# tex.net
KiCad netlist of a schematic drawn in EAGLE
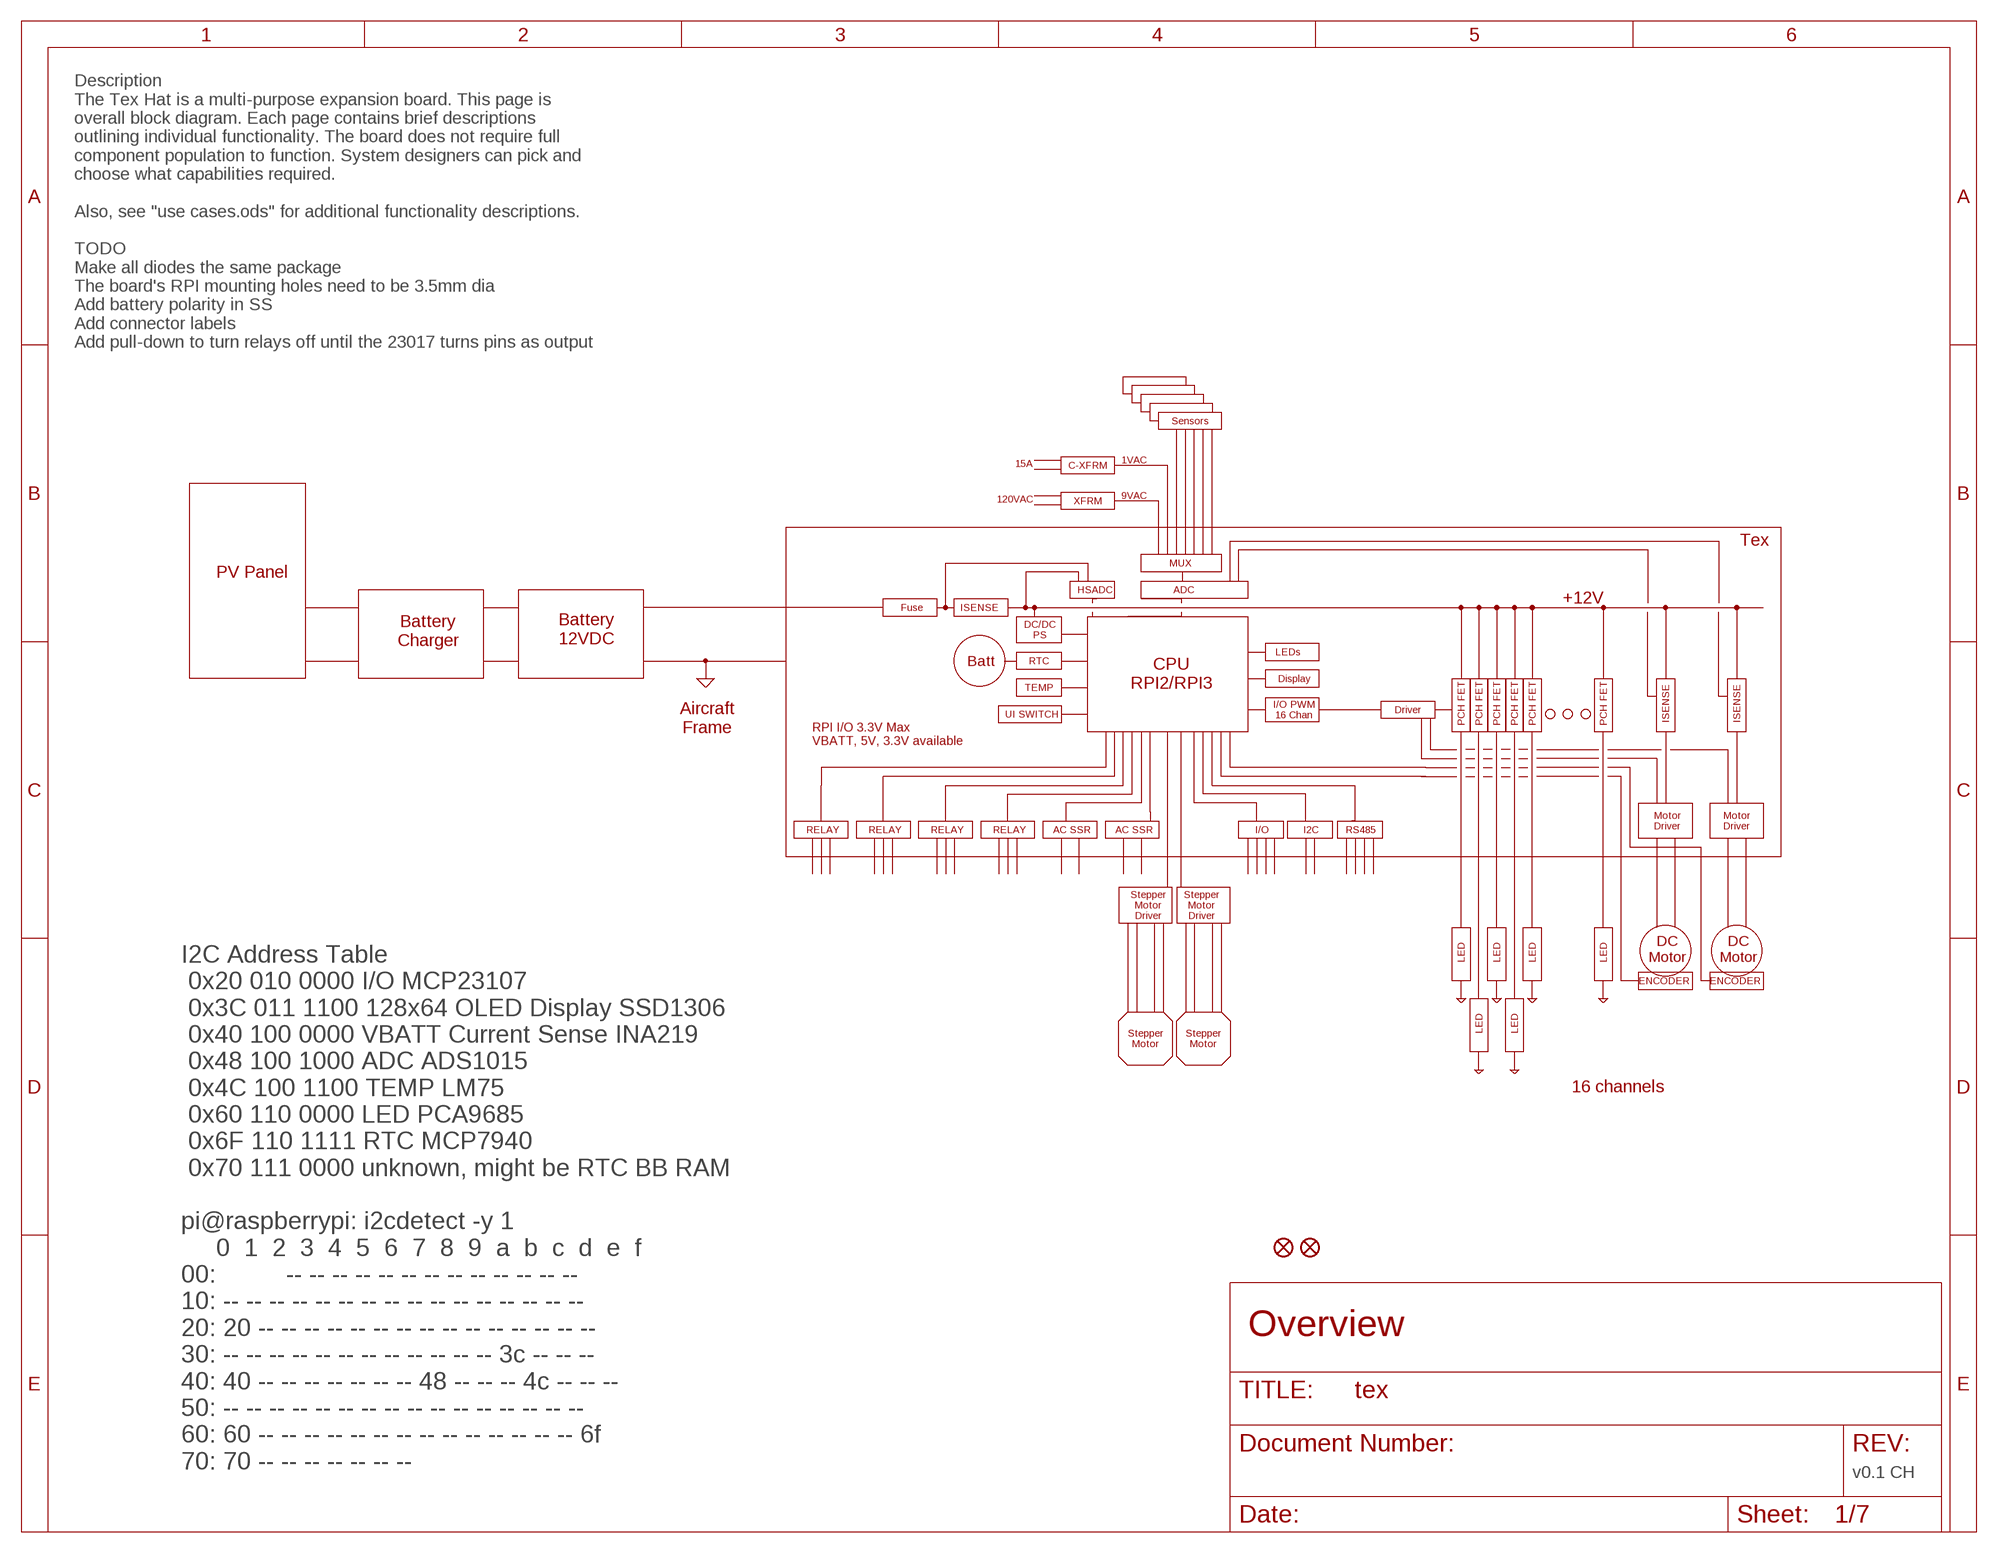
[diagram p0: schematic, sheet 1]
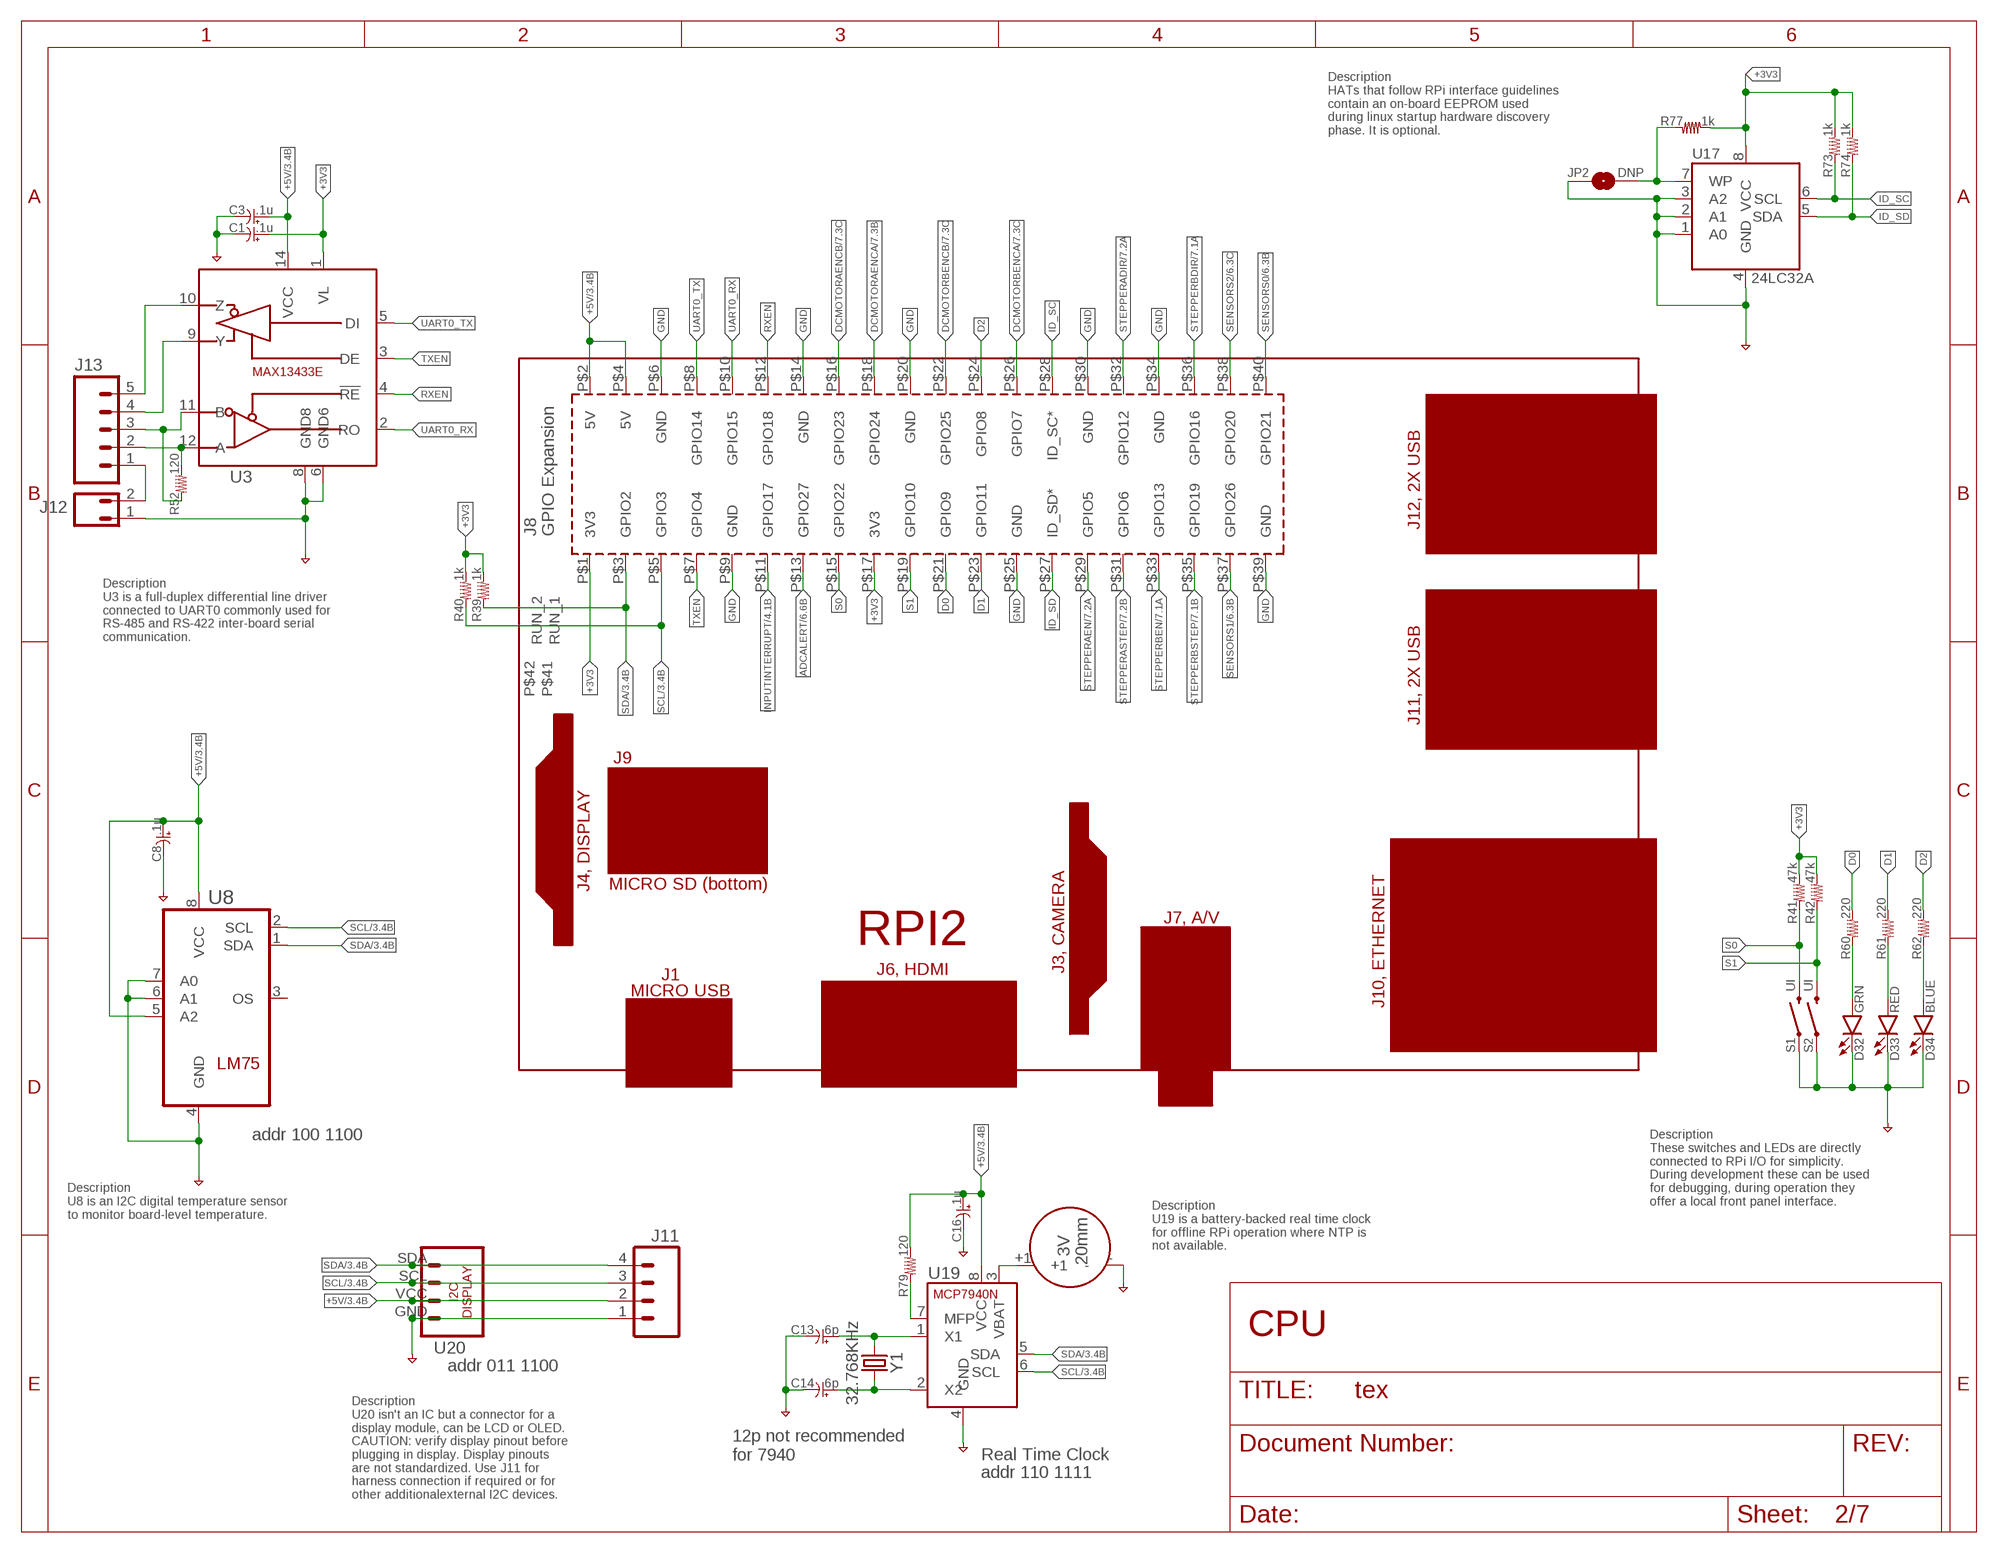
[diagram p1: schematic, sheet 2]
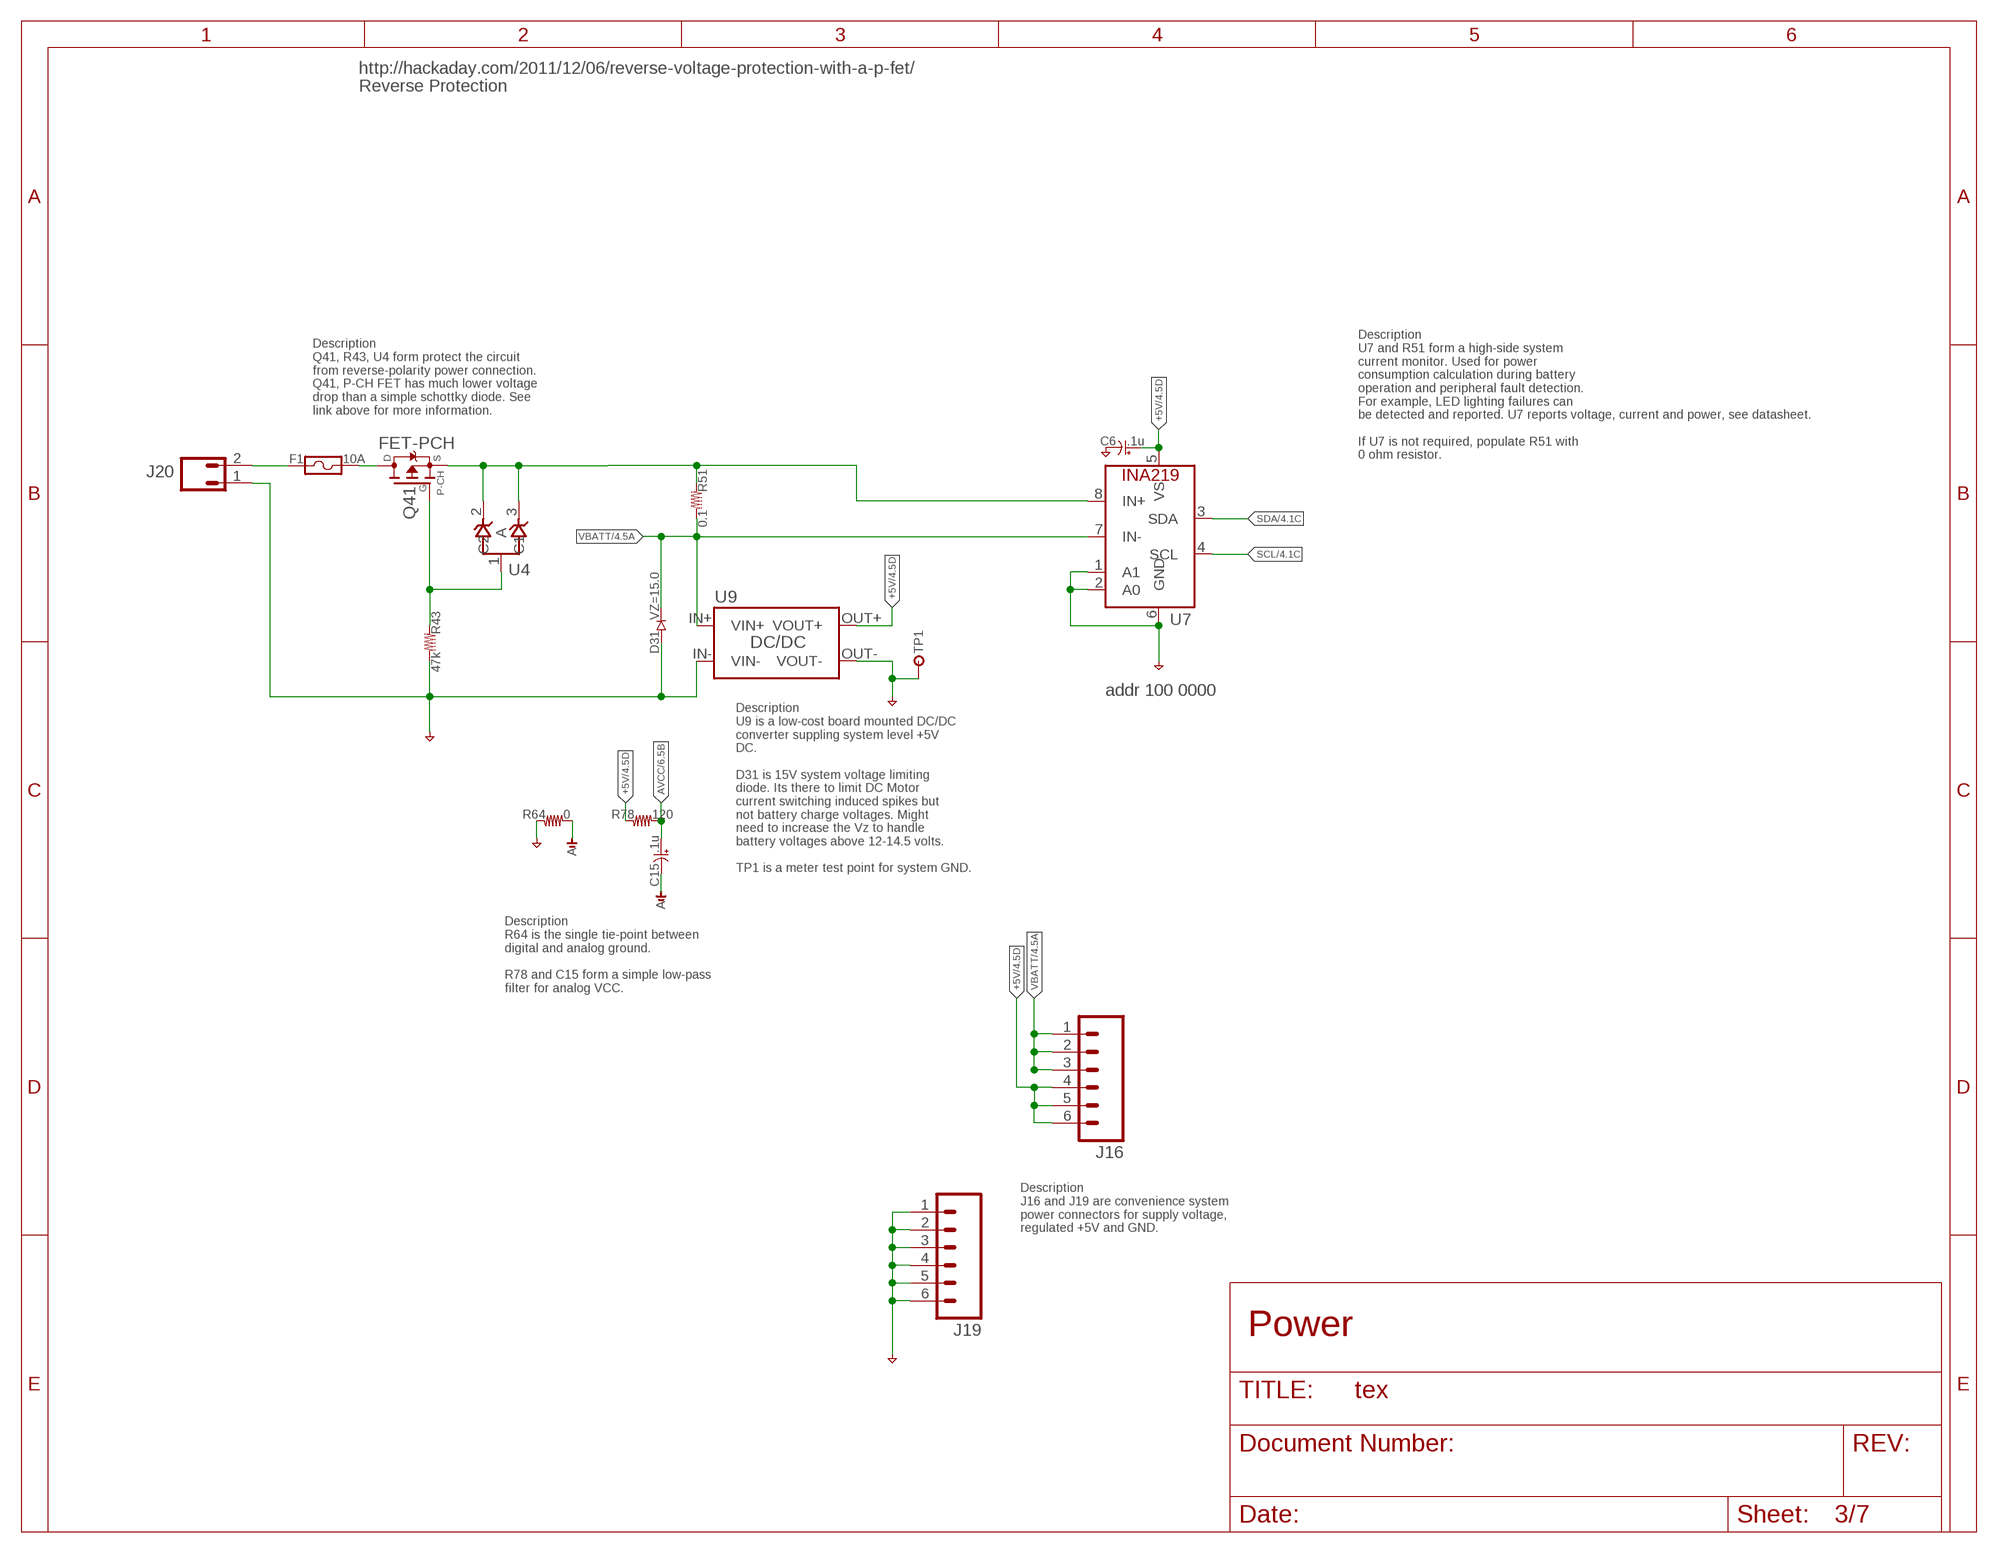
[diagram p2: schematic, sheet 3]
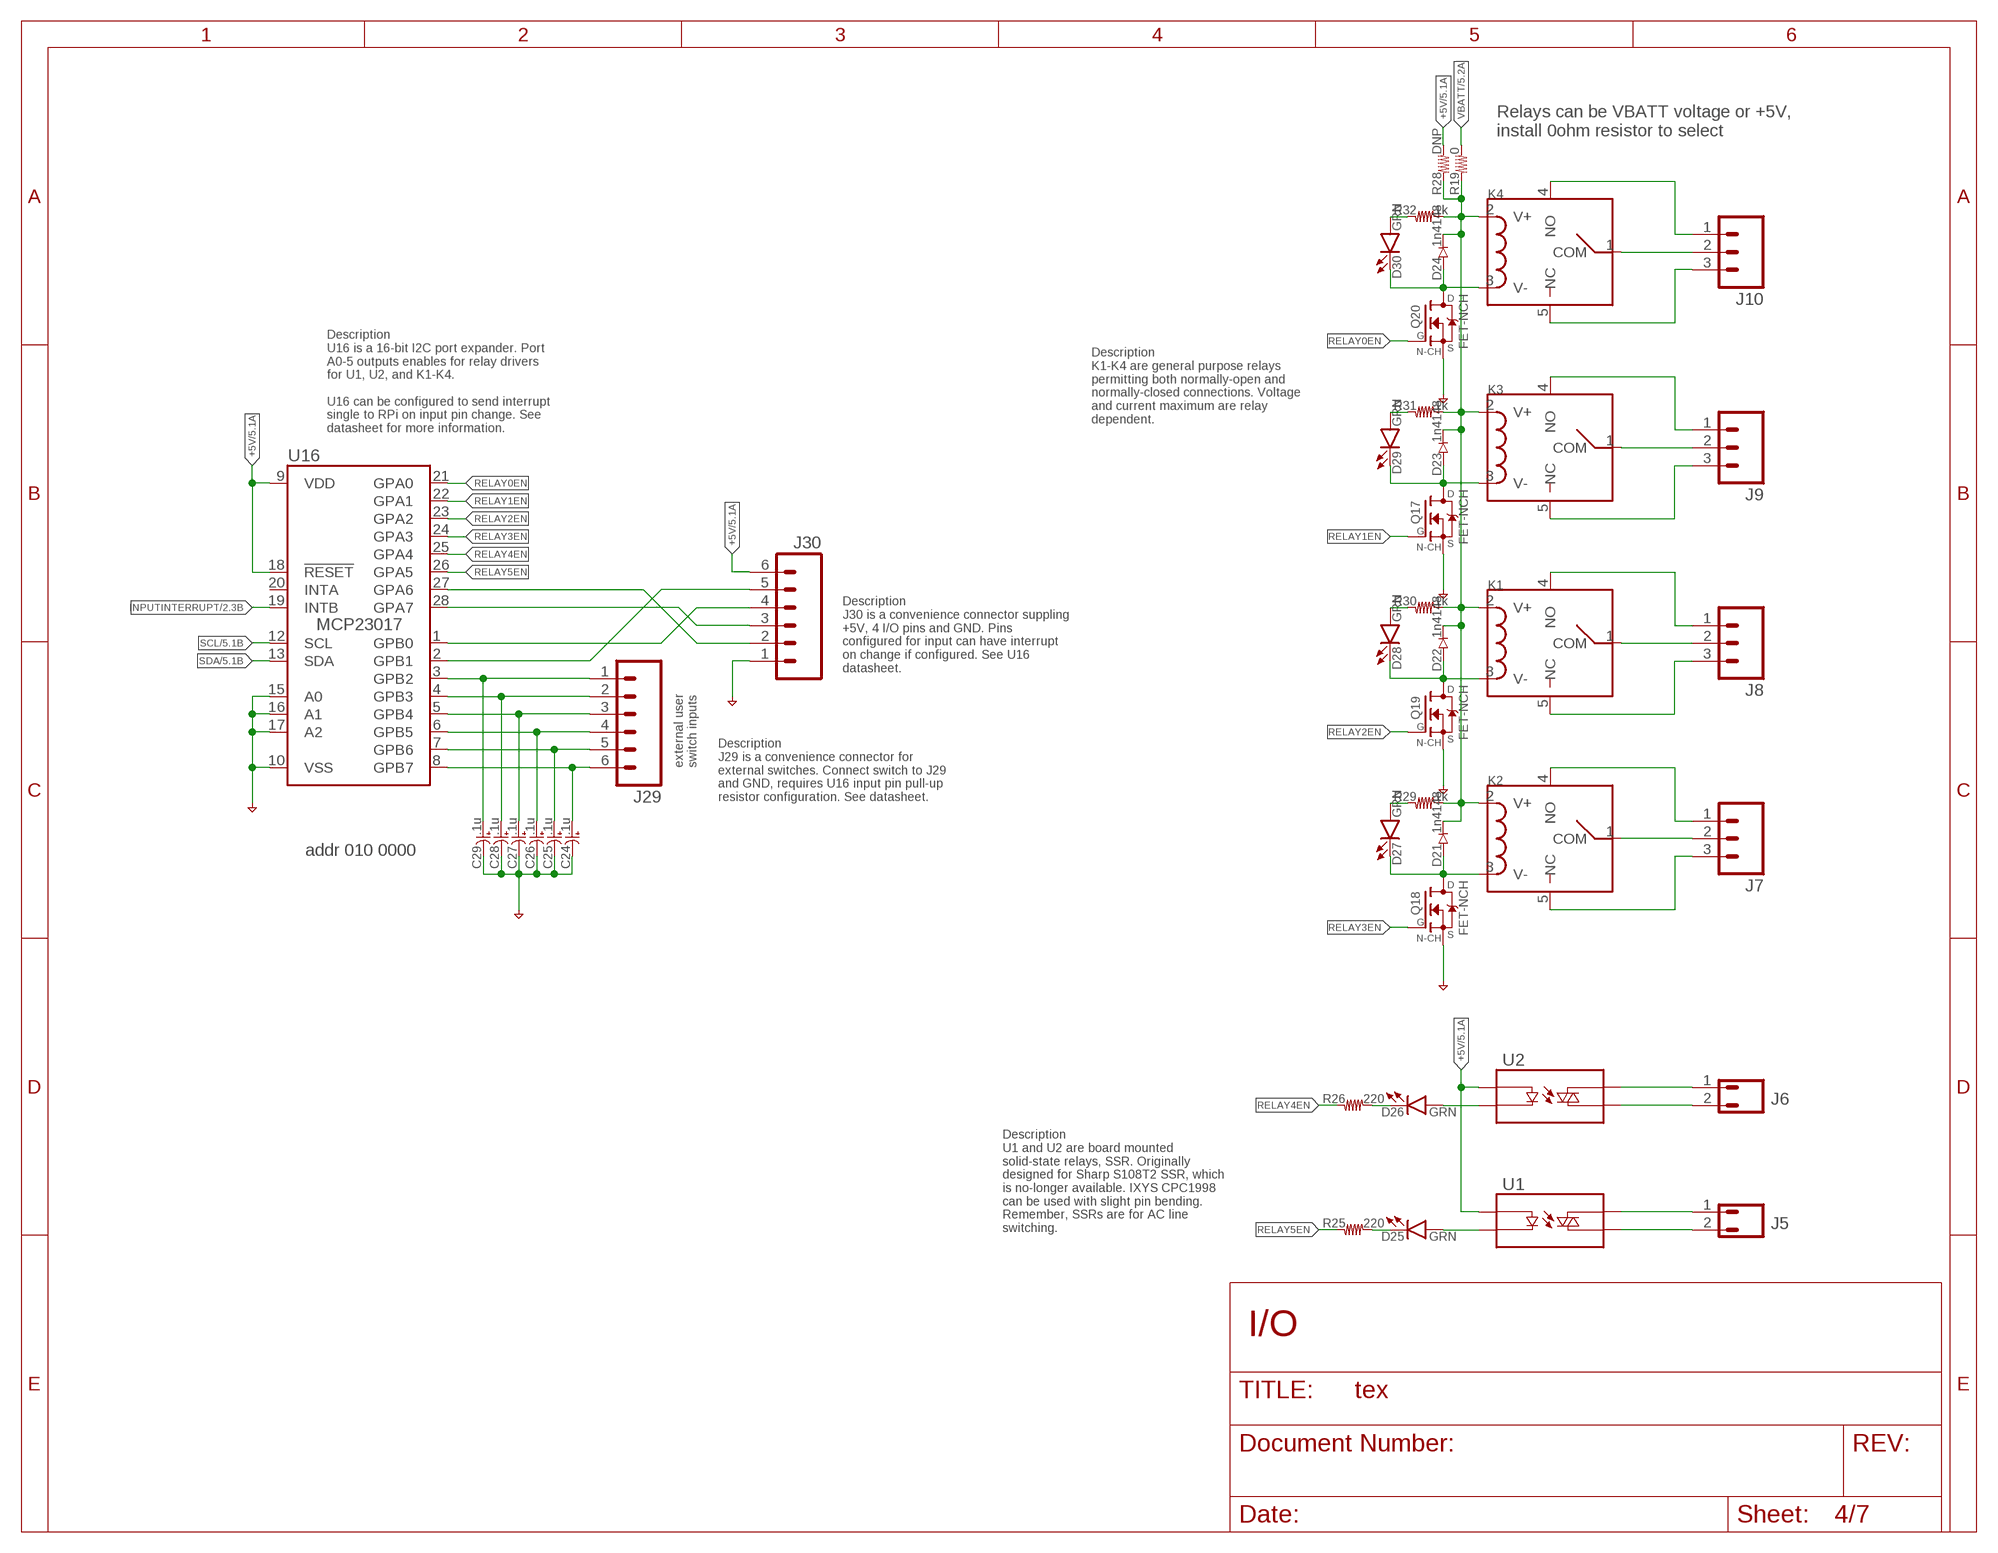
[diagram p3: schematic, sheet 4]
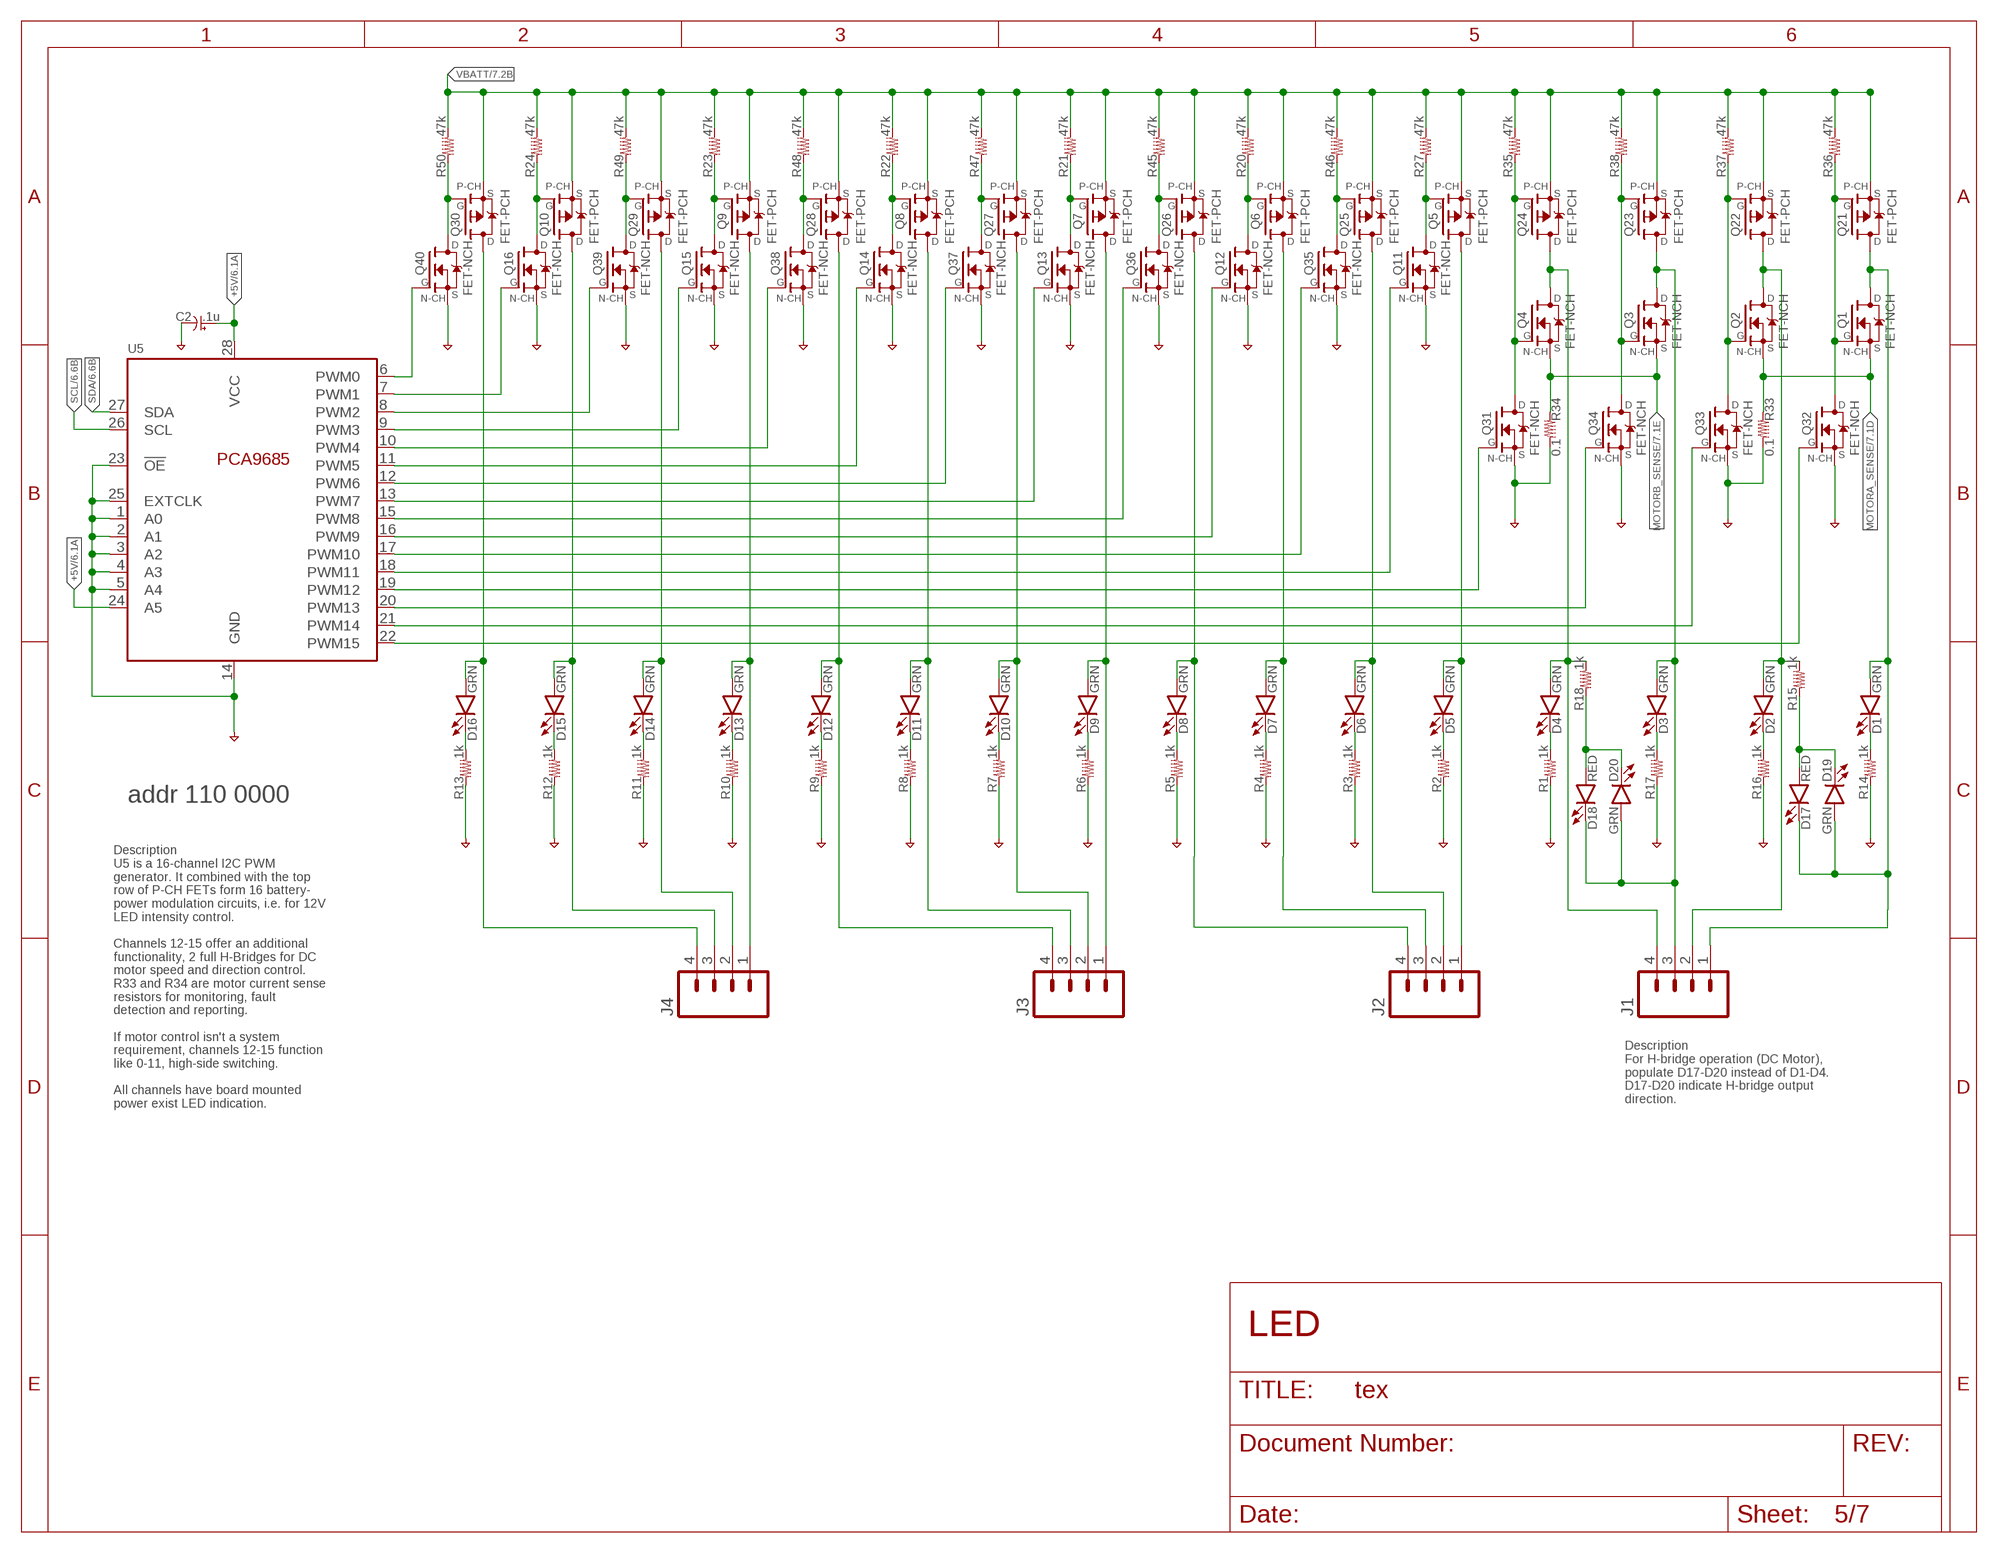
[diagram p4: schematic, sheet 5]
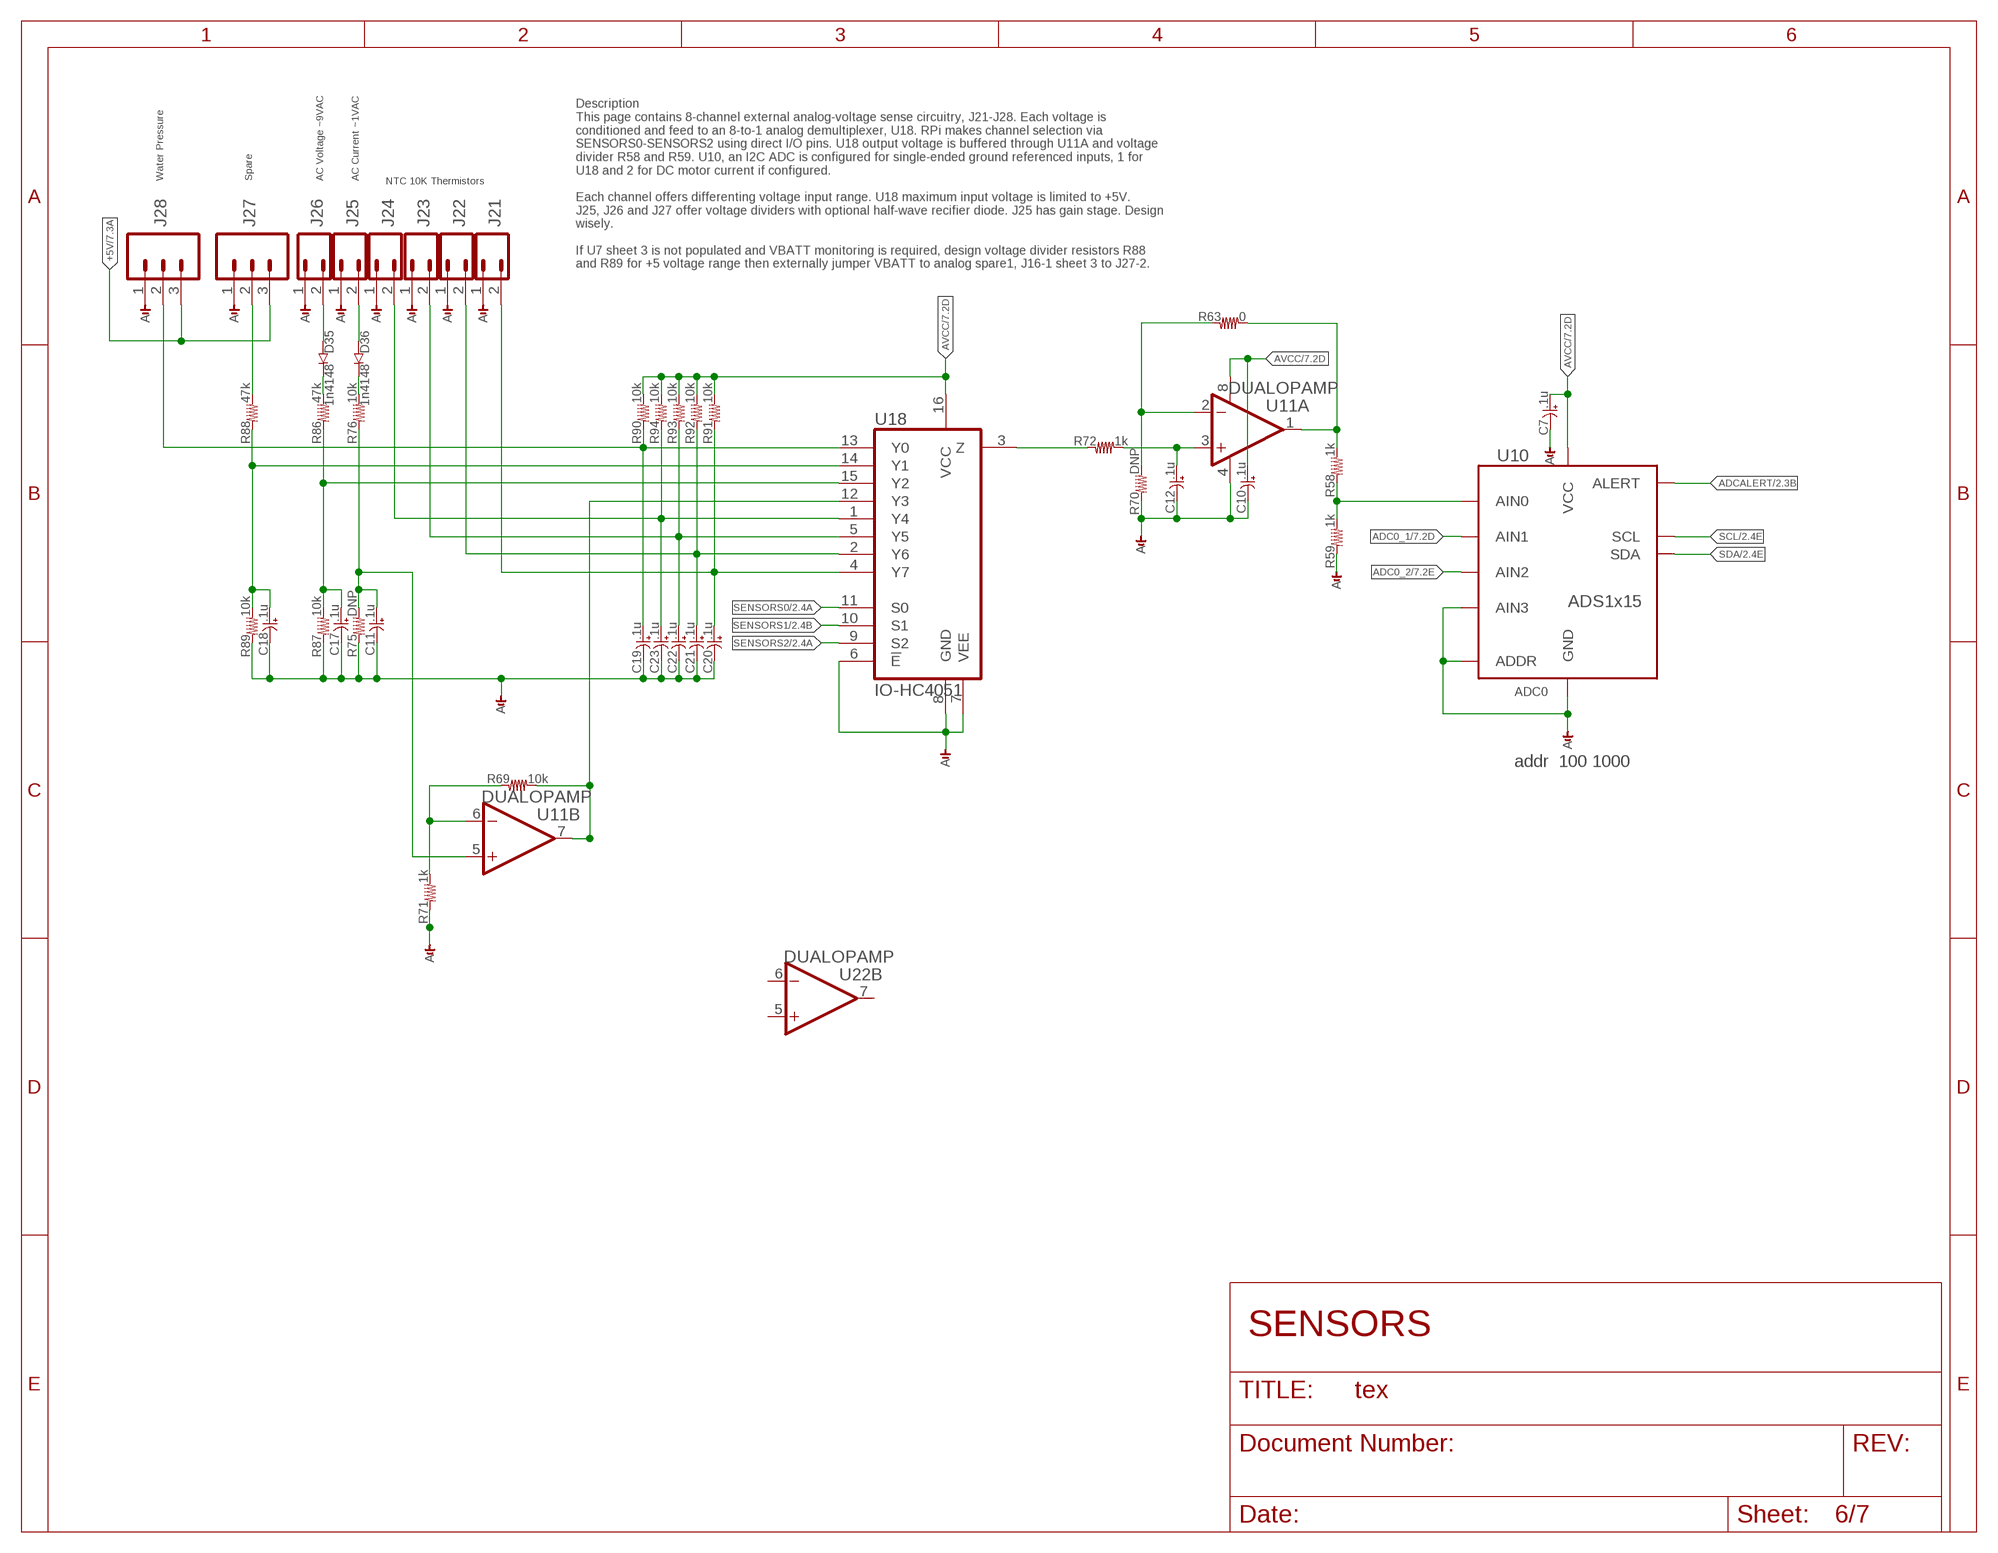
[diagram p5: schematic, sheet 6]
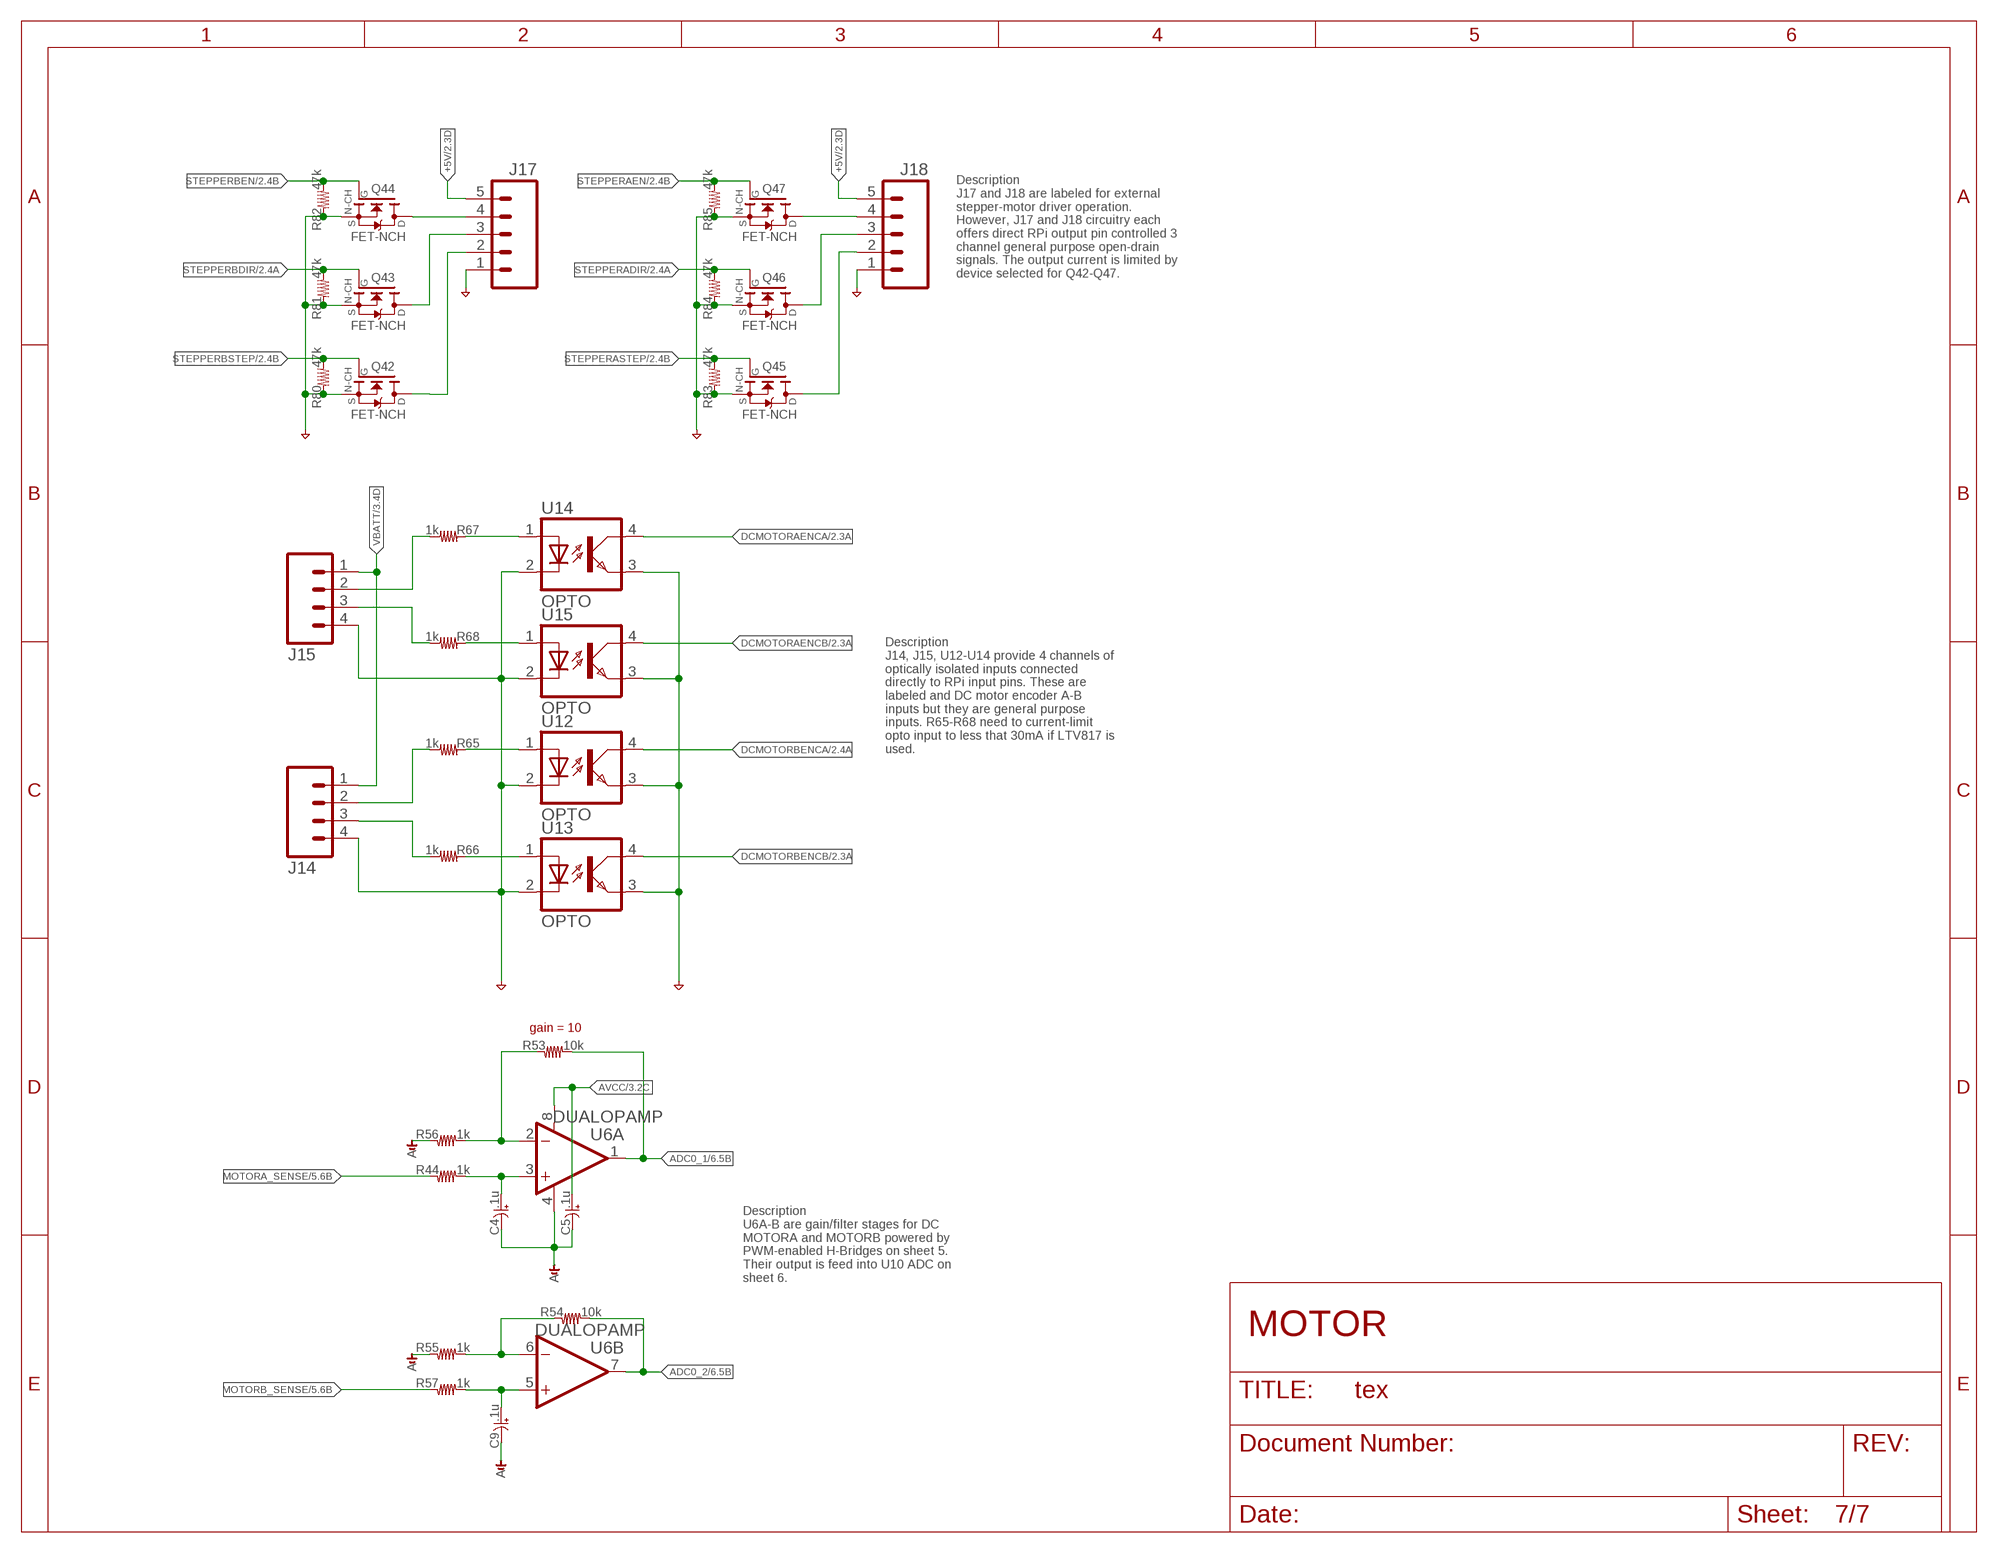
[diagram p6: schematic, sheet 7]

(export (version "E")
  (design (tool "Eeschema 10.0.6"))
  (components
    (comp (ref "C24")
      (value ".1u")
      (footprint "eagle-import:C0603")
      (libsource (lib "eagle-import") (part "C-0603"))
    )
    (comp (ref "C25")
      (value ".1u")
      (footprint "eagle-import:C0603")
      (libsource (lib "eagle-import") (part "C-0603"))
    )
    (comp (ref "C26")
      (value ".1u")
      (footprint "eagle-import:C0603")
      (libsource (lib "eagle-import") (part "C-0603"))
    )
    (comp (ref "C27")
      (value ".1u")
      (footprint "eagle-import:C0603")
      (libsource (lib "eagle-import") (part "C-0603"))
    )
    (comp (ref "C28")
      (value ".1u")
      (footprint "eagle-import:C0603")
      (libsource (lib "eagle-import") (part "C-0603"))
    )
    (comp (ref "C29")
      (value ".1u")
      (footprint "eagle-import:C0603")
      (libsource (lib "eagle-import") (part "C-0603"))
    )
    (comp (ref "D21")
      (value "1n4148")
      (footprint "eagle-import:SOD-523")
      (libsource (lib "eagle-import") (part "DIODE-0603"))
    )
    (comp (ref "D22")
      (value "1n4148")
      (footprint "eagle-import:SOD-523")
      (libsource (lib "eagle-import") (part "DIODE-0603"))
    )
    (comp (ref "D23")
      (value "1n4148")
      (footprint "eagle-import:SOD-523")
      (libsource (lib "eagle-import") (part "DIODE-0603"))
    )
    (comp (ref "D24")
      (value "1n4148")
      (footprint "eagle-import:SOD-523")
      (libsource (lib "eagle-import") (part "DIODE-0603"))
    )
    (comp (ref "D25")
      (value "GRN")
      (footprint "eagle-import:LED0603")
      (libsource (lib "eagle-import") (part "LED-0603"))
    )
    (comp (ref "D26")
      (value "GRN")
      (footprint "eagle-import:LED0603")
      (libsource (lib "eagle-import") (part "LED-0603"))
    )
    (comp (ref "D27")
      (value "GRN")
      (footprint "eagle-import:LED0603")
      (libsource (lib "eagle-import") (part "LED-0603"))
    )
    (comp (ref "D28")
      (value "GRN")
      (footprint "eagle-import:LED0603")
      (libsource (lib "eagle-import") (part "LED-0603"))
    )
    (comp (ref "D29")
      (value "GRN")
      (footprint "eagle-import:LED0603")
      (libsource (lib "eagle-import") (part "LED-0603"))
    )
    (comp (ref "D30")
      (value "GRN")
      (footprint "eagle-import:LED0603")
      (libsource (lib "eagle-import") (part "LED-0603"))
    )
    (comp (ref "J5")
      (value "CONN-02-PLUGIN-SCREW")
      (footprint "eagle-import:CONN-3.81MM-KF2EDG-2")
      (libsource (lib "eagle-import") (part "CONN-02-PLUGIN-SCREW"))
    )
    (comp (ref "J6")
      (value "CONN-02-PLUGIN-SCREW")
      (footprint "eagle-import:CONN-3.81MM-KF2EDG-2")
      (libsource (lib "eagle-import") (part "CONN-02-PLUGIN-SCREW"))
    )
    (comp (ref "J7")
      (value "CONN-03-PLUGIN-SCREW")
      (footprint "eagle-import:CONN-3.81MM-KF2EDG-3")
      (libsource (lib "eagle-import") (part "CONN-03-PLUGIN-SCREW"))
    )
    (comp (ref "J8")
      (value "CONN-03-PLUGIN-SCREW")
      (footprint "eagle-import:CONN-3.81MM-KF2EDG-3")
      (libsource (lib "eagle-import") (part "CONN-03-PLUGIN-SCREW"))
    )
    (comp (ref "J9")
      (value "CONN-03-PLUGIN-SCREW")
      (footprint "eagle-import:CONN-3.81MM-KF2EDG-3")
      (libsource (lib "eagle-import") (part "CONN-03-PLUGIN-SCREW"))
    )
    (comp (ref "J10")
      (value "CONN-03-PLUGIN-SCREW")
      (footprint "eagle-import:CONN-3.81MM-KF2EDG-3")
      (libsource (lib "eagle-import") (part "CONN-03-PLUGIN-SCREW"))
    )
    (comp (ref "J29")
      (value "CONN-06-PLUGIN-SCREW")
      (footprint "eagle-import:CONN-3.81MM-KF2EDG-6")
      (libsource (lib "eagle-import") (part "CONN-06-PLUGIN-SCREW"))
    )
    (comp (ref "J30")
      (value "CONN-06-PLUGIN-SCREW")
      (footprint "eagle-import:CONN-3.81MM-KF2EDG-6")
      (libsource (lib "eagle-import") (part "CONN-06-PLUGIN-SCREW"))
    )
    (comp (ref "K1")
      (value "RELAY-SPST-19X15X15MM")
      (footprint "eagle-import:RELAY-SPST-19.0X15.0X15.0MM")
      (libsource (lib "eagle-import") (part "RELAY-SPST-19X15X15MM"))
    )
    (comp (ref "K2")
      (value "RELAY-SPST-19X15X15MM")
      (footprint "eagle-import:RELAY-SPST-19.0X15.0X15.0MM")
      (libsource (lib "eagle-import") (part "RELAY-SPST-19X15X15MM"))
    )
    (comp (ref "K3")
      (value "RELAY-SPST-19X15X15MM")
      (footprint "eagle-import:RELAY-SPST-19.0X15.0X15.0MM")
      (libsource (lib "eagle-import") (part "RELAY-SPST-19X15X15MM"))
    )
    (comp (ref "K4")
      (value "RELAY-SPST-19X15X15MM")
      (footprint "eagle-import:RELAY-SPST-19.0X15.0X15.0MM")
      (libsource (lib "eagle-import") (part "RELAY-SPST-19X15X15MM"))
    )
    (comp (ref "Q17")
      (value "FET-NCH")
      (footprint "eagle-import:SOT23-3")
      (libsource (lib "eagle-import") (part "FET-NCHANNEL-SOT23"))
    )
    (comp (ref "Q18")
      (value "FET-NCH")
      (footprint "eagle-import:SOT23-3")
      (libsource (lib "eagle-import") (part "FET-NCHANNEL-SOT23"))
    )
    (comp (ref "Q19")
      (value "FET-NCH")
      (footprint "eagle-import:SOT23-3")
      (libsource (lib "eagle-import") (part "FET-NCHANNEL-SOT23"))
    )
    (comp (ref "Q20")
      (value "FET-NCH")
      (footprint "eagle-import:SOT23-3")
      (libsource (lib "eagle-import") (part "FET-NCHANNEL-SOT23"))
    )
    (comp (ref "R19")
      (value "0")
      (footprint "eagle-import:R0603")
      (libsource (lib "eagle-import") (part "R-0603"))
    )
    (comp (ref "R25")
      (value "220")
      (footprint "eagle-import:R0603")
      (libsource (lib "eagle-import") (part "R-0603"))
    )
    (comp (ref "R26")
      (value "220")
      (footprint "eagle-import:R0603")
      (libsource (lib "eagle-import") (part "R-0603"))
    )
    (comp (ref "R28")
      (value "DNP")
      (footprint "eagle-import:R0603")
      (libsource (lib "eagle-import") (part "R-0603"))
    )
    (comp (ref "R29")
      (value "1k")
      (footprint "eagle-import:R0603")
      (libsource (lib "eagle-import") (part "R-0603"))
    )
    (comp (ref "R30")
      (value "1k")
      (footprint "eagle-import:R0603")
      (libsource (lib "eagle-import") (part "R-0603"))
    )
    (comp (ref "R31")
      (value "1k")
      (footprint "eagle-import:R0603")
      (libsource (lib "eagle-import") (part "R-0603"))
    )
    (comp (ref "R32")
      (value "1k")
      (footprint "eagle-import:R0603")
      (libsource (lib "eagle-import") (part "R-0603"))
    )
    (comp (ref "U1")
      (value "RELAY-S108T02PTH")
      (footprint "eagle-import:RELAY-S108T02")
      (libsource (lib "eagle-import") (part "RELAY-S108T02PTH"))
    )
    (comp (ref "U2")
      (value "RELAY-S108T02PTH")
      (footprint "eagle-import:RELAY-S108T02")
      (libsource (lib "eagle-import") (part "RELAY-S108T02PTH"))
    )
    (comp (ref "U16")
      (value "MCP23017")
      (footprint "eagle-import:SO28W")
      (fields (field (name "MF") "MICROCHIP") (field (name "MPN") "MCP23017-E/SO"))
      (libsource (lib "eagle-import") (part "IO-MCP23017SO"))
    )
    (comp (ref "C6")
      (value ".1u")
      (footprint "eagle-import:C0603")
      (libsource (lib "eagle-import") (part "C-0603"))
    )
    (comp (ref "C15")
      (value ".1u")
      (footprint "eagle-import:C0603")
      (libsource (lib "eagle-import") (part "C-0603"))
    )
    (comp (ref "D31")
      (value "VZ=15.0")
      (footprint "eagle-import:DO-214AC(SMA)")
      (libsource (lib "eagle-import") (part "DIODE-SMA"))
    )
    (comp (ref "F1")
      (value "10A")
      (footprint "eagle-import:3557-2")
      (libsource (lib "eagle-import") (part "FUSE-HOLDER-3557-2"))
    )
    (comp (ref "J16")
      (value "CONN-06-PLUGIN-SCREW")
      (footprint "eagle-import:CONN-3.81MM-KF2EDG-6")
      (libsource (lib "eagle-import") (part "CONN-06-PLUGIN-SCREW"))
    )
    (comp (ref "J19")
      (value "CONN-06-PLUGIN-SCREW")
      (footprint "eagle-import:CONN-3.81MM-KF2EDG-6")
      (libsource (lib "eagle-import") (part "CONN-06-PLUGIN-SCREW"))
    )
    (comp (ref "J20")
      (value "CONN-02-6.35MM")
      (footprint "eagle-import:CONN-OSTT702")
      (libsource (lib "eagle-import") (part "CONN-02-6.35MM"))
    )
    (comp (ref "Q41")
      (value "FET-PCH")
      (footprint "eagle-import:TO252")
      (libsource (lib "eagle-import") (part "FET-PCHTO252"))
    )
    (comp (ref "R43")
      (value "47k")
      (footprint "eagle-import:R0603")
      (libsource (lib "eagle-import") (part "R-0603"))
    )
    (comp (ref "R51")
      (value "0.1")
      (footprint "eagle-import:R1210")
      (libsource (lib "eagle-import") (part "R-1210"))
    )
    (comp (ref "R64")
      (value "0")
      (footprint "eagle-import:R0603")
      (libsource (lib "eagle-import") (part "R-0603"))
    )
    (comp (ref "R78")
      (value "120")
      (footprint "eagle-import:R0603")
      (libsource (lib "eagle-import") (part "R-0603"))
    )
    (comp (ref "TP1")
      (value "TESTPOINTTHRU")
      (footprint "eagle-import:TPTHRU")
      (libsource (lib "eagle-import") (part "TESTPOINTTHRU"))
    )
    (comp (ref "U4")
      (value "AZ23C5V1")
      (footprint "eagle-import:SOT-23")
      (libsource (lib "eagle-import") (part "AZ23CXXX"))
    )
    (comp (ref "U7")
      (value "INA219")
      (footprint "eagle-import:SOIC8")
      (libsource (lib "eagle-import") (part "ADC-INA219-SOIC8"))
    )
    (comp (ref "U9")
      (value "DCDC-CONVERTER-LM2577-BOARD")
      (footprint "eagle-import:DCDC-LM2577-BOARD")
      (libsource (lib "eagle-import") (part "DCDC-CONVERTER-LM2577-BOARD"))
    )
    (comp (ref "C4")
      (value ".1u")
      (footprint "eagle-import:C0603")
      (libsource (lib "eagle-import") (part "C-0603"))
    )
    (comp (ref "C5")
      (value ".1u")
      (footprint "eagle-import:C0603")
      (libsource (lib "eagle-import") (part "C-0603"))
    )
    (comp (ref "C9")
      (value ".1u")
      (footprint "eagle-import:C0603")
      (libsource (lib "eagle-import") (part "C-0603"))
    )
    (comp (ref "J14")
      (value "CONN-04-PLUGIN-SCREW")
      (footprint "eagle-import:CONN-3.81MM-KF2EDG-4")
      (libsource (lib "eagle-import") (part "CONN-04-PLUGIN-SCREW"))
    )
    (comp (ref "J15")
      (value "CONN-04-PLUGIN-SCREW")
      (footprint "eagle-import:CONN-3.81MM-KF2EDG-4")
      (libsource (lib "eagle-import") (part "CONN-04-PLUGIN-SCREW"))
    )
    (comp (ref "J17")
      (value "CONN-05-PLUGIN-SCREW")
      (footprint "eagle-import:CONN-3.81MM-KF2EDG-5")
      (libsource (lib "eagle-import") (part "CONN-05-PLUGIN-SCREW"))
    )
    (comp (ref "J18")
      (value "CONN-05-PLUGIN-SCREW")
      (footprint "eagle-import:CONN-3.81MM-KF2EDG-5")
      (libsource (lib "eagle-import") (part "CONN-05-PLUGIN-SCREW"))
    )
    (comp (ref "Q42")
      (value "FET-NCH")
      (footprint "eagle-import:SOT23-3")
      (libsource (lib "eagle-import") (part "FET-NCHANNEL-SOT23"))
    )
    (comp (ref "Q43")
      (value "FET-NCH")
      (footprint "eagle-import:SOT23-3")
      (libsource (lib "eagle-import") (part "FET-NCHANNEL-SOT23"))
    )
    (comp (ref "Q44")
      (value "FET-NCH")
      (footprint "eagle-import:SOT23-3")
      (libsource (lib "eagle-import") (part "FET-NCHANNEL-SOT23"))
    )
    (comp (ref "Q45")
      (value "FET-NCH")
      (footprint "eagle-import:SOT23-3")
      (libsource (lib "eagle-import") (part "FET-NCHANNEL-SOT23"))
    )
    (comp (ref "Q46")
      (value "FET-NCH")
      (footprint "eagle-import:SOT23-3")
      (libsource (lib "eagle-import") (part "FET-NCHANNEL-SOT23"))
    )
    (comp (ref "Q47")
      (value "FET-NCH")
      (footprint "eagle-import:SOT23-3")
      (libsource (lib "eagle-import") (part "FET-NCHANNEL-SOT23"))
    )
    (comp (ref "R44")
      (value "1k")
      (footprint "eagle-import:R0603")
      (libsource (lib "eagle-import") (part "R-0603"))
    )
    (comp (ref "R53")
      (value "10k")
      (footprint "eagle-import:R0603")
      (libsource (lib "eagle-import") (part "R-0603"))
    )
    (comp (ref "R54")
      (value "10k")
      (footprint "eagle-import:R0603")
      (libsource (lib "eagle-import") (part "R-0603"))
    )
    (comp (ref "R55")
      (value "1k")
      (footprint "eagle-import:R0603")
      (libsource (lib "eagle-import") (part "R-0603"))
    )
    (comp (ref "R56")
      (value "1k")
      (footprint "eagle-import:R0603")
      (libsource (lib "eagle-import") (part "R-0603"))
    )
    (comp (ref "R57")
      (value "1k")
      (footprint "eagle-import:R0603")
      (libsource (lib "eagle-import") (part "R-0603"))
    )
    (comp (ref "R65")
      (value "1k")
      (footprint "eagle-import:R0603")
      (libsource (lib "eagle-import") (part "R-0603"))
    )
    (comp (ref "R66")
      (value "1k")
      (footprint "eagle-import:R0603")
      (libsource (lib "eagle-import") (part "R-0603"))
    )
    (comp (ref "R67")
      (value "1k")
      (footprint "eagle-import:R0603")
      (libsource (lib "eagle-import") (part "R-0603"))
    )
    (comp (ref "R68")
      (value "1k")
      (footprint "eagle-import:R0603")
      (libsource (lib "eagle-import") (part "R-0603"))
    )
    (comp (ref "R80")
      (value "47k")
      (footprint "eagle-import:R0603")
      (libsource (lib "eagle-import") (part "R-0603"))
    )
    (comp (ref "R81")
      (value "47k")
      (footprint "eagle-import:R0603")
      (libsource (lib "eagle-import") (part "R-0603"))
    )
    (comp (ref "R82")
      (value "47k")
      (footprint "eagle-import:R0603")
      (libsource (lib "eagle-import") (part "R-0603"))
    )
    (comp (ref "R83")
      (value "47k")
      (footprint "eagle-import:R0603")
      (libsource (lib "eagle-import") (part "R-0603"))
    )
    (comp (ref "R84")
      (value "47k")
      (footprint "eagle-import:R0603")
      (libsource (lib "eagle-import") (part "R-0603"))
    )
    (comp (ref "R85")
      (value "47k")
      (footprint "eagle-import:R0603")
      (libsource (lib "eagle-import") (part "R-0603"))
    )
    (comp (ref "U6")
      (value "DUALOPAMP")
      (footprint "eagle-import:SO08")
      (libsource (lib "eagle-import") (part "AMP-OPAMP-DUAL-SO08"))
    )
    (comp (ref "U12")
      (value "OPTO")
      (footprint "eagle-import:LTV817")
      (libsource (lib "eagle-import") (part "OPTO-LTV817"))
    )
    (comp (ref "U13")
      (value "OPTO")
      (footprint "eagle-import:LTV817")
      (libsource (lib "eagle-import") (part "OPTO-LTV817"))
    )
    (comp (ref "U14")
      (value "OPTO")
      (footprint "eagle-import:LTV817")
      (libsource (lib "eagle-import") (part "OPTO-LTV817"))
    )
    (comp (ref "U15")
      (value "OPTO")
      (footprint "eagle-import:LTV817")
      (libsource (lib "eagle-import") (part "OPTO-LTV817"))
    )
    (comp (ref "B1")
      (value "CR2032")
      (footprint "eagle-import:BAT-HLD-001")
      (libsource (lib "eagle-import") (part "CONN-COINBATTERYHOLDER-20MM"))
    )
    (comp (ref "C1")
      (value ".1u")
      (footprint "eagle-import:C0603")
      (libsource (lib "eagle-import") (part "C-0603"))
    )
    (comp (ref "C3")
      (value ".1u")
      (footprint "eagle-import:C0603")
      (libsource (lib "eagle-import") (part "C-0603"))
    )
    (comp (ref "C8")
      (value ".1u")
      (footprint "eagle-import:C0603")
      (libsource (lib "eagle-import") (part "C-0603"))
    )
    (comp (ref "C13")
      (value "6p")
      (footprint "eagle-import:C0603")
      (libsource (lib "eagle-import") (part "C-0603"))
    )
    (comp (ref "C14")
      (value "6p")
      (footprint "eagle-import:C0603")
      (libsource (lib "eagle-import") (part "C-0603"))
    )
    (comp (ref "C16")
      (value ".1u")
      (footprint "eagle-import:C0603")
      (libsource (lib "eagle-import") (part "C-0603"))
    )
    (comp (ref "D32")
      (value "GRN")
      (footprint "eagle-import:LED0603")
      (libsource (lib "eagle-import") (part "LED-0603"))
    )
    (comp (ref "D33")
      (value "RED")
      (footprint "eagle-import:LED0603")
      (libsource (lib "eagle-import") (part "LED-0603"))
    )
    (comp (ref "D34")
      (value "BLUE")
      (footprint "eagle-import:LED0603")
      (libsource (lib "eagle-import") (part "LED-0603"))
    )
    (comp (ref "J11")
      (value "CONN-04-0.1")
      (footprint "eagle-import:1X04")
      (libsource (lib "eagle-import") (part "CONN-04-0.1"))
    )
    (comp (ref "J12")
      (value "CONN-02-0.1")
      (footprint "eagle-import:1X02")
      (libsource (lib "eagle-import") (part "CONN-02-0.1"))
    )
    (comp (ref "J13")
      (value "CONN-05-PLUGIN-SCREW")
      (footprint "eagle-import:CONN-3.81MM-KF2EDG-5")
      (libsource (lib "eagle-import") (part "CONN-05-PLUGIN-SCREW"))
    )
    (comp (ref "JP2")
      (value "DNP")
      (footprint "eagle-import:PAD-JUMPER-2-NO_NO_SILK")
      (libsource (lib "eagle-import") (part "JUMPER-PAD-2-NO"))
    )
    (comp (ref "PCB1")
      (value "BOARD-RPI2")
      (footprint "eagle-import:BOARD-RPI2")
      (libsource (lib "eagle-import") (part "BOARD-RPI2"))
    )
    (comp (ref "R39")
      (value "1k")
      (footprint "eagle-import:R0603")
      (libsource (lib "eagle-import") (part "R-0603"))
    )
    (comp (ref "R40")
      (value "1k")
      (footprint "eagle-import:R0603")
      (libsource (lib "eagle-import") (part "R-0603"))
    )
    (comp (ref "R41")
      (value "47k")
      (footprint "eagle-import:R0603")
      (libsource (lib "eagle-import") (part "R-0603"))
    )
    (comp (ref "R42")
      (value "47k")
      (footprint "eagle-import:R0603")
      (libsource (lib "eagle-import") (part "R-0603"))
    )
    (comp (ref "R52")
      (value "120")
      (footprint "eagle-import:R0603")
      (libsource (lib "eagle-import") (part "R-0603"))
    )
    (comp (ref "R60")
      (value "220")
      (footprint "eagle-import:R0603")
      (libsource (lib "eagle-import") (part "R-0603"))
    )
    (comp (ref "R61")
      (value "220")
      (footprint "eagle-import:R0603")
      (libsource (lib "eagle-import") (part "R-0603"))
    )
    (comp (ref "R62")
      (value "220")
      (footprint "eagle-import:R0603")
      (libsource (lib "eagle-import") (part "R-0603"))
    )
    (comp (ref "R73")
      (value "1k")
      (footprint "eagle-import:R0603")
      (libsource (lib "eagle-import") (part "R-0603"))
    )
    (comp (ref "R74")
      (value "1k")
      (footprint "eagle-import:R0603")
      (libsource (lib "eagle-import") (part "R-0603"))
    )
    (comp (ref "R77")
      (value "1k")
      (footprint "eagle-import:R0603")
      (libsource (lib "eagle-import") (part "R-0603"))
    )
    (comp (ref "R79")
      (value "120")
      (footprint "eagle-import:R0603")
      (libsource (lib "eagle-import") (part "R-0603"))
    )
    (comp (ref "S1")
      (value "UI")
      (footprint "eagle-import:TACTILE-SWITCH-6MMX3.5MM")
      (libsource (lib "eagle-import") (part "SWITCH-PUSHBUTTON-6MMX3.5MM"))
    )
    (comp (ref "S2")
      (value "UI")
      (footprint "eagle-import:TACTILE-SWITCH-6MMX3.5MM")
      (libsource (lib "eagle-import") (part "SWITCH-PUSHBUTTON-6MMX3.5MM"))
    )
    (comp (ref "U3")
      (value "MAX13433E")
      (footprint "eagle-import:SO14")
      (libsource (lib "eagle-import") (part "COMM-MAX13433E"))
    )
    (comp (ref "U8")
      (value "LM75")
      (footprint "eagle-import:SO08")
      (libsource (lib "eagle-import") (part "SENSOR-TEMP-LM75-SO08"))
    )
    (comp (ref "U17")
      (value "24LC32A")
      (footprint "eagle-import:SO08")
      (libsource (lib "eagle-import") (part "MEMORY-EEPROM-SO08"))
    )
    (comp (ref "U19")
      (value "MCP7940N")
      (footprint "eagle-import:SO08")
      (libsource (lib "eagle-import") (part "RTC-MCP7940N"))
    )
    (comp (ref "U20")
      (value "DISP-I2C-4PIN")
      (footprint "eagle-import:DISP-I2C-4PIN-0.96")
      (libsource (lib "eagle-import") (part "DISP-I2C-4PIN"))
    )
    (comp (ref "Y1")
      (value "32.768KHz")
      (footprint "eagle-import:ABS25")
      (libsource (lib "eagle-import") (part "CRYSTAL32-SMDABS25"))
    )
    (comp (ref "C7")
      (value ".1u")
      (footprint "eagle-import:C0603")
      (libsource (lib "eagle-import") (part "C-0603"))
    )
    (comp (ref "C10")
      (value ".1u")
      (footprint "eagle-import:C0603")
      (libsource (lib "eagle-import") (part "C-0603"))
    )
    (comp (ref "C11")
      (value ".1u")
      (footprint "eagle-import:C0603")
      (libsource (lib "eagle-import") (part "C-0603"))
    )
    (comp (ref "C12")
      (value ".1u")
      (footprint "eagle-import:C0603")
      (libsource (lib "eagle-import") (part "C-0603"))
    )
    (comp (ref "C17")
      (value ".1u")
      (footprint "eagle-import:C0603")
      (libsource (lib "eagle-import") (part "C-0603"))
    )
    (comp (ref "C18")
      (value ".1u")
      (footprint "eagle-import:C0603")
      (libsource (lib "eagle-import") (part "C-0603"))
    )
    (comp (ref "C19")
      (value ".1u")
      (footprint "eagle-import:C0603")
      (libsource (lib "eagle-import") (part "C-0603"))
    )
    (comp (ref "C20")
      (value ".1u")
      (footprint "eagle-import:C0603")
      (libsource (lib "eagle-import") (part "C-0603"))
    )
    (comp (ref "C21")
      (value ".1u")
      (footprint "eagle-import:C0603")
      (libsource (lib "eagle-import") (part "C-0603"))
    )
    (comp (ref "C22")
      (value ".1u")
      (footprint "eagle-import:C0603")
      (libsource (lib "eagle-import") (part "C-0603"))
    )
    (comp (ref "C23")
      (value ".1u")
      (footprint "eagle-import:C0603")
      (libsource (lib "eagle-import") (part "C-0603"))
    )
    (comp (ref "D35")
      (value "1n4148")
      (footprint "eagle-import:SOD-523")
      (libsource (lib "eagle-import") (part "DIODE-0603"))
    )
    (comp (ref "D36")
      (value "1n4148")
      (footprint "eagle-import:SOD-523")
      (libsource (lib "eagle-import") (part "DIODE-0603"))
    )
    (comp (ref "J21")
      (value "CONN-02-PLUGIN-SCREW")
      (footprint "eagle-import:CONN-3.81MM-KF2EDG-2")
      (libsource (lib "eagle-import") (part "CONN-02-PLUGIN-SCREW"))
    )
    (comp (ref "J22")
      (value "CONN-02-PLUGIN-SCREW")
      (footprint "eagle-import:CONN-3.81MM-KF2EDG-2")
      (libsource (lib "eagle-import") (part "CONN-02-PLUGIN-SCREW"))
    )
    (comp (ref "J23")
      (value "CONN-02-PLUGIN-SCREW")
      (footprint "eagle-import:CONN-3.81MM-KF2EDG-2")
      (libsource (lib "eagle-import") (part "CONN-02-PLUGIN-SCREW"))
    )
    (comp (ref "J24")
      (value "CONN-02-PLUGIN-SCREW")
      (footprint "eagle-import:CONN-3.81MM-KF2EDG-2")
      (libsource (lib "eagle-import") (part "CONN-02-PLUGIN-SCREW"))
    )
    (comp (ref "J25")
      (value "CONN-02-PLUGIN-SCREW")
      (footprint "eagle-import:CONN-3.81MM-KF2EDG-2")
      (libsource (lib "eagle-import") (part "CONN-02-PLUGIN-SCREW"))
    )
    (comp (ref "J26")
      (value "CONN-02-PLUGIN-SCREW")
      (footprint "eagle-import:CONN-3.81MM-KF2EDG-2")
      (libsource (lib "eagle-import") (part "CONN-02-PLUGIN-SCREW"))
    )
    (comp (ref "J27")
      (value "CONN-03-PLUGIN-SCREW")
      (footprint "eagle-import:CONN-3.81MM-KF2EDG-3")
      (libsource (lib "eagle-import") (part "CONN-03-PLUGIN-SCREW"))
    )
    (comp (ref "J28")
      (value "CONN-03-PLUGIN-SCREW")
      (footprint "eagle-import:CONN-3.81MM-KF2EDG-3")
      (libsource (lib "eagle-import") (part "CONN-03-PLUGIN-SCREW"))
    )
    (comp (ref "R58")
      (value "1k")
      (footprint "eagle-import:R0603")
      (libsource (lib "eagle-import") (part "R-0603"))
    )
    (comp (ref "R59")
      (value "1k")
      (footprint "eagle-import:R0603")
      (libsource (lib "eagle-import") (part "R-0603"))
    )
    (comp (ref "R63")
      (value "0")
      (footprint "eagle-import:R0603")
      (libsource (lib "eagle-import") (part "R-0603"))
    )
    (comp (ref "R69")
      (value "10k")
      (footprint "eagle-import:R0603")
      (libsource (lib "eagle-import") (part "R-0603"))
    )
    (comp (ref "R70")
      (value "DNP")
      (footprint "eagle-import:R0603")
      (libsource (lib "eagle-import") (part "R-0603"))
    )
    (comp (ref "R71")
      (value "1k")
      (footprint "eagle-import:R0603")
      (libsource (lib "eagle-import") (part "R-0603"))
    )
    (comp (ref "R72")
      (value "1k")
      (footprint "eagle-import:R0603")
      (libsource (lib "eagle-import") (part "R-0603"))
    )
    (comp (ref "R75")
      (value "DNP")
      (footprint "eagle-import:R0603")
      (libsource (lib "eagle-import") (part "R-0603"))
    )
    (comp (ref "R76")
      (value "10k")
      (footprint "eagle-import:R0603")
      (libsource (lib "eagle-import") (part "R-0603"))
    )
    (comp (ref "R86")
      (value "47k")
      (footprint "eagle-import:R0603")
      (libsource (lib "eagle-import") (part "R-0603"))
    )
    (comp (ref "R87")
      (value "10k")
      (footprint "eagle-import:R0603")
      (libsource (lib "eagle-import") (part "R-0603"))
    )
    (comp (ref "R88")
      (value "47k")
      (footprint "eagle-import:R0603")
      (libsource (lib "eagle-import") (part "R-0603"))
    )
    (comp (ref "R89")
      (value "10k")
      (footprint "eagle-import:R0603")
      (libsource (lib "eagle-import") (part "R-0603"))
    )
    (comp (ref "R90")
      (value "10k")
      (footprint "eagle-import:R0603")
      (libsource (lib "eagle-import") (part "R-0603"))
    )
    (comp (ref "R91")
      (value "10k")
      (footprint "eagle-import:R0603")
      (libsource (lib "eagle-import") (part "R-0603"))
    )
    (comp (ref "R92")
      (value "10k")
      (footprint "eagle-import:R0603")
      (libsource (lib "eagle-import") (part "R-0603"))
    )
    (comp (ref "R93")
      (value "10k")
      (footprint "eagle-import:R0603")
      (libsource (lib "eagle-import") (part "R-0603"))
    )
    (comp (ref "R94")
      (value "10k")
      (footprint "eagle-import:R0603")
      (libsource (lib "eagle-import") (part "R-0603"))
    )
    (comp (ref "U10")
      (value "ADS1x15")
      (footprint "eagle-import:MSOP10_0.5")
      (libsource (lib "eagle-import") (part "ADC-ADS1015-MSOP10"))
    )
    (comp (ref "U11")
      (value "DUALOPAMP")
      (footprint "eagle-import:SO08")
      (libsource (lib "eagle-import") (part "AMP-OPAMP-DUAL-SO08"))
    )
    (comp (ref "U18")
      (value "IO-HC4051")
      (footprint "eagle-import:SO16")
      (libsource (lib "eagle-import") (part "IO-HC4051"))
    )
    (comp (ref "U22")
      (value "DUALOPAMP")
      (footprint "eagle-import:SO08")
      (libsource (lib "eagle-import") (part "AMP-OPAMP-DUAL-SO08"))
    )
    (comp (ref "JP1")
      (value "FIDUCIALUFIDUCIAL")
      (footprint "eagle-import:MICRO-FIDUCIAL")
      (libsource (lib "eagle-import") (part "FIDUCIALUFIDUCIAL"))
    )
    (comp (ref "JP3")
      (value "FIDUCIALUFIDUCIAL")
      (footprint "eagle-import:MICRO-FIDUCIAL")
      (libsource (lib "eagle-import") (part "FIDUCIALUFIDUCIAL"))
    )
    (comp (ref "C2")
      (value ".1u")
      (footprint "eagle-import:C0603")
      (libsource (lib "eagle-import") (part "C-0603"))
    )
    (comp (ref "D1")
      (value "GRN")
      (footprint "eagle-import:LED0603")
      (libsource (lib "eagle-import") (part "LED-0603"))
    )
    (comp (ref "D2")
      (value "GRN")
      (footprint "eagle-import:LED0603")
      (libsource (lib "eagle-import") (part "LED-0603"))
    )
    (comp (ref "D3")
      (value "GRN")
      (footprint "eagle-import:LED0603")
      (libsource (lib "eagle-import") (part "LED-0603"))
    )
    (comp (ref "D4")
      (value "GRN")
      (footprint "eagle-import:LED0603")
      (libsource (lib "eagle-import") (part "LED-0603"))
    )
    (comp (ref "D5")
      (value "GRN")
      (footprint "eagle-import:LED0603")
      (libsource (lib "eagle-import") (part "LED-0603"))
    )
    (comp (ref "D6")
      (value "GRN")
      (footprint "eagle-import:LED0603")
      (libsource (lib "eagle-import") (part "LED-0603"))
    )
    (comp (ref "D7")
      (value "GRN")
      (footprint "eagle-import:LED0603")
      (libsource (lib "eagle-import") (part "LED-0603"))
    )
    (comp (ref "D8")
      (value "GRN")
      (footprint "eagle-import:LED0603")
      (libsource (lib "eagle-import") (part "LED-0603"))
    )
    (comp (ref "D9")
      (value "GRN")
      (footprint "eagle-import:LED0603")
      (libsource (lib "eagle-import") (part "LED-0603"))
    )
    (comp (ref "D10")
      (value "GRN")
      (footprint "eagle-import:LED0603")
      (libsource (lib "eagle-import") (part "LED-0603"))
    )
    (comp (ref "D11")
      (value "GRN")
      (footprint "eagle-import:LED0603")
      (libsource (lib "eagle-import") (part "LED-0603"))
    )
    (comp (ref "D12")
      (value "GRN")
      (footprint "eagle-import:LED0603")
      (libsource (lib "eagle-import") (part "LED-0603"))
    )
    (comp (ref "D13")
      (value "GRN")
      (footprint "eagle-import:LED0603")
      (libsource (lib "eagle-import") (part "LED-0603"))
    )
    (comp (ref "D14")
      (value "GRN")
      (footprint "eagle-import:LED0603")
      (libsource (lib "eagle-import") (part "LED-0603"))
    )
    (comp (ref "D15")
      (value "GRN")
      (footprint "eagle-import:LED0603")
      (libsource (lib "eagle-import") (part "LED-0603"))
    )
    (comp (ref "D16")
      (value "GRN")
      (footprint "eagle-import:LED0603")
      (libsource (lib "eagle-import") (part "LED-0603"))
    )
    (comp (ref "D17")
      (value "RED")
      (footprint "eagle-import:LED0603")
      (libsource (lib "eagle-import") (part "LED-0603"))
    )
    (comp (ref "D18")
      (value "RED")
      (footprint "eagle-import:LED0603")
      (libsource (lib "eagle-import") (part "LED-0603"))
    )
    (comp (ref "D19")
      (value "GRN")
      (footprint "eagle-import:LED0603")
      (libsource (lib "eagle-import") (part "LED-0603"))
    )
    (comp (ref "D20")
      (value "GRN")
      (footprint "eagle-import:LED0603")
      (libsource (lib "eagle-import") (part "LED-0603"))
    )
    (comp (ref "J1")
      (value "CONN-04-PLUGIN-SCREW")
      (footprint "eagle-import:CONN-3.81MM-KF2EDG-4")
      (libsource (lib "eagle-import") (part "CONN-04-PLUGIN-SCREW"))
    )
    (comp (ref "J2")
      (value "CONN-04-PLUGIN-SCREW")
      (footprint "eagle-import:CONN-3.81MM-KF2EDG-4")
      (libsource (lib "eagle-import") (part "CONN-04-PLUGIN-SCREW"))
    )
    (comp (ref "J3")
      (value "CONN-04-PLUGIN-SCREW")
      (footprint "eagle-import:CONN-3.81MM-KF2EDG-4")
      (libsource (lib "eagle-import") (part "CONN-04-PLUGIN-SCREW"))
    )
    (comp (ref "J4")
      (value "CONN-04-PLUGIN-SCREW")
      (footprint "eagle-import:CONN-3.81MM-KF2EDG-4")
      (libsource (lib "eagle-import") (part "CONN-04-PLUGIN-SCREW"))
    )
    (comp (ref "Q1")
      (value "FET-NCH")
      (footprint "eagle-import:TO252")
      (libsource (lib "eagle-import") (part "FET-NCHANNEL-TO252"))
    )
    (comp (ref "Q2")
      (value "FET-NCH")
      (footprint "eagle-import:TO252")
      (libsource (lib "eagle-import") (part "FET-NCHANNEL-TO252"))
    )
    (comp (ref "Q3")
      (value "FET-NCH")
      (footprint "eagle-import:TO252")
      (libsource (lib "eagle-import") (part "FET-NCHANNEL-TO252"))
    )
    (comp (ref "Q4")
      (value "FET-NCH")
      (footprint "eagle-import:TO252")
      (libsource (lib "eagle-import") (part "FET-NCHANNEL-TO252"))
    )
    (comp (ref "Q5")
      (value "FET-PCH")
      (footprint "eagle-import:TO252")
      (libsource (lib "eagle-import") (part "FET-PCHANNEL-TO252"))
    )
    (comp (ref "Q6")
      (value "FET-PCH")
      (footprint "eagle-import:TO252")
      (libsource (lib "eagle-import") (part "FET-PCHANNEL-TO252"))
    )
    (comp (ref "Q7")
      (value "FET-PCH")
      (footprint "eagle-import:TO252")
      (libsource (lib "eagle-import") (part "FET-PCHANNEL-TO252"))
    )
    (comp (ref "Q8")
      (value "FET-PCH")
      (footprint "eagle-import:TO252")
      (libsource (lib "eagle-import") (part "FET-PCHANNEL-TO252"))
    )
    (comp (ref "Q9")
      (value "FET-PCH")
      (footprint "eagle-import:TO252")
      (libsource (lib "eagle-import") (part "FET-PCHANNEL-TO252"))
    )
    (comp (ref "Q10")
      (value "FET-PCH")
      (footprint "eagle-import:TO252")
      (libsource (lib "eagle-import") (part "FET-PCHANNEL-TO252"))
    )
    (comp (ref "Q11")
      (value "FET-NCH")
      (footprint "eagle-import:SOT23-3")
      (libsource (lib "eagle-import") (part "FET-NCHANNEL-SOT23"))
    )
    (comp (ref "Q12")
      (value "FET-NCH")
      (footprint "eagle-import:SOT23-3")
      (libsource (lib "eagle-import") (part "FET-NCHANNEL-SOT23"))
    )
    (comp (ref "Q13")
      (value "FET-NCH")
      (footprint "eagle-import:SOT23-3")
      (libsource (lib "eagle-import") (part "FET-NCHANNEL-SOT23"))
    )
    (comp (ref "Q14")
      (value "FET-NCH")
      (footprint "eagle-import:SOT23-3")
      (libsource (lib "eagle-import") (part "FET-NCHANNEL-SOT23"))
    )
    (comp (ref "Q15")
      (value "FET-NCH")
      (footprint "eagle-import:SOT23-3")
      (libsource (lib "eagle-import") (part "FET-NCHANNEL-SOT23"))
    )
    (comp (ref "Q16")
      (value "FET-NCH")
      (footprint "eagle-import:SOT23-3")
      (libsource (lib "eagle-import") (part "FET-NCHANNEL-SOT23"))
    )
    (comp (ref "Q21")
      (value "FET-PCH")
      (footprint "eagle-import:TO252")
      (libsource (lib "eagle-import") (part "FET-PCHANNEL-TO252"))
    )
    (comp (ref "Q22")
      (value "FET-PCH")
      (footprint "eagle-import:TO252")
      (libsource (lib "eagle-import") (part "FET-PCHANNEL-TO252"))
    )
    (comp (ref "Q23")
      (value "FET-PCH")
      (footprint "eagle-import:TO252")
      (libsource (lib "eagle-import") (part "FET-PCHANNEL-TO252"))
    )
    (comp (ref "Q24")
      (value "FET-PCH")
      (footprint "eagle-import:TO252")
      (libsource (lib "eagle-import") (part "FET-PCHANNEL-TO252"))
    )
    (comp (ref "Q25")
      (value "FET-PCH")
      (footprint "eagle-import:TO252")
      (libsource (lib "eagle-import") (part "FET-PCHANNEL-TO252"))
    )
    (comp (ref "Q26")
      (value "FET-PCH")
      (footprint "eagle-import:TO252")
      (libsource (lib "eagle-import") (part "FET-PCHANNEL-TO252"))
    )
    (comp (ref "Q27")
      (value "FET-PCH")
      (footprint "eagle-import:TO252")
      (libsource (lib "eagle-import") (part "FET-PCHANNEL-TO252"))
    )
    (comp (ref "Q28")
      (value "FET-PCH")
      (footprint "eagle-import:TO252")
      (libsource (lib "eagle-import") (part "FET-PCHANNEL-TO252"))
    )
    (comp (ref "Q29")
      (value "FET-PCH")
      (footprint "eagle-import:TO252")
      (libsource (lib "eagle-import") (part "FET-PCHANNEL-TO252"))
    )
    (comp (ref "Q30")
      (value "FET-PCH")
      (footprint "eagle-import:TO252")
      (libsource (lib "eagle-import") (part "FET-PCHANNEL-TO252"))
    )
    (comp (ref "Q31")
      (value "FET-NCH")
      (footprint "eagle-import:SOT23-3")
      (libsource (lib "eagle-import") (part "FET-NCHANNEL-SOT23"))
    )
    (comp (ref "Q32")
      (value "FET-NCH")
      (footprint "eagle-import:SOT23-3")
      (libsource (lib "eagle-import") (part "FET-NCHANNEL-SOT23"))
    )
    (comp (ref "Q33")
      (value "FET-NCH")
      (footprint "eagle-import:SOT23-3")
      (libsource (lib "eagle-import") (part "FET-NCHANNEL-SOT23"))
    )
    (comp (ref "Q34")
      (value "FET-NCH")
      (footprint "eagle-import:SOT23-3")
      (libsource (lib "eagle-import") (part "FET-NCHANNEL-SOT23"))
    )
    (comp (ref "Q35")
      (value "FET-NCH")
      (footprint "eagle-import:SOT23-3")
      (libsource (lib "eagle-import") (part "FET-NCHANNEL-SOT23"))
    )
    (comp (ref "Q36")
      (value "FET-NCH")
      (footprint "eagle-import:SOT23-3")
      (libsource (lib "eagle-import") (part "FET-NCHANNEL-SOT23"))
    )
    (comp (ref "Q37")
      (value "FET-NCH")
      (footprint "eagle-import:SOT23-3")
      (libsource (lib "eagle-import") (part "FET-NCHANNEL-SOT23"))
    )
    (comp (ref "Q38")
      (value "FET-NCH")
      (footprint "eagle-import:SOT23-3")
      (libsource (lib "eagle-import") (part "FET-NCHANNEL-SOT23"))
    )
    (comp (ref "Q39")
      (value "FET-NCH")
      (footprint "eagle-import:SOT23-3")
      (libsource (lib "eagle-import") (part "FET-NCHANNEL-SOT23"))
    )
    (comp (ref "Q40")
      (value "FET-NCH")
      (footprint "eagle-import:SOT23-3")
      (libsource (lib "eagle-import") (part "FET-NCHANNEL-SOT23"))
    )
    (comp (ref "R1")
      (value "1k")
      (footprint "eagle-import:R0603")
      (libsource (lib "eagle-import") (part "R-0603"))
    )
    (comp (ref "R2")
      (value "1k")
      (footprint "eagle-import:R0603")
      (libsource (lib "eagle-import") (part "R-0603"))
    )
    (comp (ref "R3")
      (value "1k")
      (footprint "eagle-import:R0603")
      (libsource (lib "eagle-import") (part "R-0603"))
    )
    (comp (ref "R4")
      (value "1k")
      (footprint "eagle-import:R0603")
      (libsource (lib "eagle-import") (part "R-0603"))
    )
    (comp (ref "R5")
      (value "1k")
      (footprint "eagle-import:R0603")
      (libsource (lib "eagle-import") (part "R-0603"))
    )
    (comp (ref "R6")
      (value "1k")
      (footprint "eagle-import:R0603")
      (libsource (lib "eagle-import") (part "R-0603"))
    )
    (comp (ref "R7")
      (value "1k")
      (footprint "eagle-import:R0603")
      (libsource (lib "eagle-import") (part "R-0603"))
    )
    (comp (ref "R8")
      (value "1k")
      (footprint "eagle-import:R0603")
      (libsource (lib "eagle-import") (part "R-0603"))
    )
    (comp (ref "R9")
      (value "1k")
      (footprint "eagle-import:R0603")
      (libsource (lib "eagle-import") (part "R-0603"))
    )
    (comp (ref "R10")
      (value "1k")
      (footprint "eagle-import:R0603")
      (libsource (lib "eagle-import") (part "R-0603"))
    )
    (comp (ref "R11")
      (value "1k")
      (footprint "eagle-import:R0603")
      (libsource (lib "eagle-import") (part "R-0603"))
    )
    (comp (ref "R12")
      (value "1k")
      (footprint "eagle-import:R0603")
      (libsource (lib "eagle-import") (part "R-0603"))
    )
    (comp (ref "R13")
      (value "1k")
      (footprint "eagle-import:R0603")
      (libsource (lib "eagle-import") (part "R-0603"))
    )
    (comp (ref "R14")
      (value "1k")
      (footprint "eagle-import:R0603")
      (libsource (lib "eagle-import") (part "R-0603"))
    )
    (comp (ref "R15")
      (value "1k")
      (footprint "eagle-import:R0603")
      (libsource (lib "eagle-import") (part "R-0603"))
    )
    (comp (ref "R16")
      (value "1k")
      (footprint "eagle-import:R0603")
      (libsource (lib "eagle-import") (part "R-0603"))
    )
    (comp (ref "R17")
      (value "1k")
      (footprint "eagle-import:R0603")
      (libsource (lib "eagle-import") (part "R-0603"))
    )
    (comp (ref "R18")
      (value "1k")
      (footprint "eagle-import:R0603")
      (libsource (lib "eagle-import") (part "R-0603"))
    )
    (comp (ref "R20")
      (value "47k")
      (footprint "eagle-import:R0603")
      (libsource (lib "eagle-import") (part "R-0603"))
    )
    (comp (ref "R21")
      (value "47k")
      (footprint "eagle-import:R0603")
      (libsource (lib "eagle-import") (part "R-0603"))
    )
    (comp (ref "R22")
      (value "47k")
      (footprint "eagle-import:R0603")
      (libsource (lib "eagle-import") (part "R-0603"))
    )
    (comp (ref "R23")
      (value "47k")
      (footprint "eagle-import:R0603")
      (libsource (lib "eagle-import") (part "R-0603"))
    )
    (comp (ref "R24")
      (value "47k")
      (footprint "eagle-import:R0603")
      (libsource (lib "eagle-import") (part "R-0603"))
    )
    (comp (ref "R27")
      (value "47k")
      (footprint "eagle-import:R0603")
      (libsource (lib "eagle-import") (part "R-0603"))
    )
    (comp (ref "R33")
      (value "0.1")
      (footprint "eagle-import:R1210")
      (libsource (lib "eagle-import") (part "R-1210"))
    )
    (comp (ref "R34")
      (value "0.1")
      (footprint "eagle-import:R1210")
      (libsource (lib "eagle-import") (part "R-1210"))
    )
    (comp (ref "R35")
      (value "47k")
      (footprint "eagle-import:R0603")
      (libsource (lib "eagle-import") (part "R-0603"))
    )
    (comp (ref "R36")
      (value "47k")
      (footprint "eagle-import:R0603")
      (libsource (lib "eagle-import") (part "R-0603"))
    )
    (comp (ref "R37")
      (value "47k")
      (footprint "eagle-import:R0603")
      (libsource (lib "eagle-import") (part "R-0603"))
    )
    (comp (ref "R38")
      (value "47k")
      (footprint "eagle-import:R0603")
      (libsource (lib "eagle-import") (part "R-0603"))
    )
    (comp (ref "R45")
      (value "47k")
      (footprint "eagle-import:R0603")
      (libsource (lib "eagle-import") (part "R-0603"))
    )
    (comp (ref "R46")
      (value "47k")
      (footprint "eagle-import:R0603")
      (libsource (lib "eagle-import") (part "R-0603"))
    )
    (comp (ref "R47")
      (value "47k")
      (footprint "eagle-import:R0603")
      (libsource (lib "eagle-import") (part "R-0603"))
    )
    (comp (ref "R48")
      (value "47k")
      (footprint "eagle-import:R0603")
      (libsource (lib "eagle-import") (part "R-0603"))
    )
    (comp (ref "R49")
      (value "47k")
      (footprint "eagle-import:R0603")
      (libsource (lib "eagle-import") (part "R-0603"))
    )
    (comp (ref "R50")
      (value "47k")
      (footprint "eagle-import:R0603")
      (libsource (lib "eagle-import") (part "R-0603"))
    )
    (comp (ref "U5")
      (value "PCA9685")
      (footprint "eagle-import:TSSOP28")
      (libsource (lib "eagle-import") (part "IO-PCA9685-TSSOP28"))
    )
  )
  (nets
    (net (code "1") (name "+3V3") (class "Default")
      (node (ref "C1") (pin "1") (pinfunction "1_1") (pintype "passive"))
      (node (ref "PCB1") (pin "P$1") (pinfunction "3V3_P$1") (pintype "bidirectional"))
      (node (ref "PCB1") (pin "P$17") (pinfunction "3V3_P$17") (pintype "bidirectional"))
      (node (ref "R39") (pin "2") (pinfunction "2_2") (pintype "passive"))
      (node (ref "R40") (pin "2") (pinfunction "2_2") (pintype "passive"))
      (node (ref "R41") (pin "2") (pinfunction "2_2") (pintype "passive"))
      (node (ref "R42") (pin "2") (pinfunction "2_2") (pintype "passive"))
      (node (ref "R73") (pin "2") (pinfunction "2_2") (pintype "passive"))
      (node (ref "R74") (pin "2") (pinfunction "2_2") (pintype "passive"))
      (node (ref "R77") (pin "2") (pinfunction "2_2") (pintype "passive"))
      (node (ref "U17") (pin "8") (pinfunction "VCC_8") (pintype "bidirectional"))
      (node (ref "U3") (pin "1") (pinfunction "VL_1") (pintype "bidirectional"))
    )
    (net (code "2") (name "+5V") (class "Default")
      (node (ref "C16") (pin "1") (pinfunction "1_1") (pintype "passive"))
      (node (ref "C2") (pin "1") (pinfunction "1_1") (pintype "passive"))
      (node (ref "C3") (pin "1") (pinfunction "1_1") (pintype "passive"))
      (node (ref "C6") (pin "1") (pinfunction "1_1") (pintype "passive"))
      (node (ref "C8") (pin "1") (pinfunction "1_1") (pintype "passive"))
      (node (ref "J11") (pin "2") (pinfunction "2_2") (pintype "passive"))
      (node (ref "J16") (pin "4") (pinfunction "4_4") (pintype "passive"))
      (node (ref "J16") (pin "5") (pinfunction "5_5") (pintype "passive"))
      (node (ref "J16") (pin "6") (pinfunction "6_6") (pintype "passive"))
      (node (ref "J17") (pin "5") (pinfunction "5_5") (pintype "passive"))
      (node (ref "J18") (pin "5") (pinfunction "5_5") (pintype "passive"))
      (node (ref "J27") (pin "3") (pinfunction "3_3") (pintype "passive"))
      (node (ref "J28") (pin "3") (pinfunction "3_3") (pintype "passive"))
      (node (ref "J30") (pin "6") (pinfunction "6_6") (pintype "passive"))
      (node (ref "PCB1") (pin "P$2") (pinfunction "5V_P$2") (pintype "bidirectional"))
      (node (ref "PCB1") (pin "P$4") (pinfunction "5V_P$4") (pintype "bidirectional"))
      (node (ref "R28") (pin "2") (pinfunction "2_2") (pintype "passive"))
      (node (ref "R78") (pin "1") (pinfunction "1_1") (pintype "passive"))
      (node (ref "R79") (pin "2") (pinfunction "2_2") (pintype "passive"))
      (node (ref "U1") (pin "3") (pinfunction "+_3") (pintype "bidirectional"))
      (node (ref "U16") (pin "18") (pinfunction "~{RESET}_18") (pintype "input"))
      (node (ref "U16") (pin "9") (pinfunction "VDD_9") (pintype "power_in"))
      (node (ref "U19") (pin "8") (pinfunction "VCC_8") (pintype "bidirectional"))
      (node (ref "U2") (pin "3") (pinfunction "+_3") (pintype "bidirectional"))
      (node (ref "U20") (pin "VCC") (pinfunction "VCC_VCC") (pintype "passive"))
      (node (ref "U3") (pin "14") (pinfunction "VCC_14") (pintype "bidirectional"))
      (node (ref "U5") (pin "24") (pinfunction "A5_24") (pintype "bidirectional"))
      (node (ref "U5") (pin "28") (pinfunction "VCC_28") (pintype "power_in"))
      (node (ref "U7") (pin "5") (pinfunction "VS_5") (pintype "bidirectional"))
      (node (ref "U8") (pin "5") (pinfunction "A2_5") (pintype "input"))
      (node (ref "U8") (pin "8") (pinfunction "VCC_8") (pintype "power_in"))
      (node (ref "U9") (pin "OUT+") (pinfunction "VOUT+_OUT+") (pintype "bidirectional"))
    )
    (net (code "3") (name "ADC0_1") (class "Default")
      (node (ref "R53") (pin "2") (pinfunction "2_2") (pintype "passive"))
      (node (ref "U10") (pin "5") (pinfunction "AIN1_5") (pintype "input"))
      (node (ref "U6") (pin "1") (pinfunction "OUT_1") (pintype "output"))
    )
    (net (code "4") (name "ADC0_2") (class "Default")
      (node (ref "R54") (pin "2") (pinfunction "2_2") (pintype "passive"))
      (node (ref "U10") (pin "6") (pinfunction "AIN2_6") (pintype "input"))
      (node (ref "U6") (pin "7") (pinfunction "OUT_7") (pintype "output"))
    )
    (net (code "5") (name "ADCALERT") (class "Default")
      (node (ref "PCB1") (pin "P$13") (pinfunction "GPIO27_P$13") (pintype "bidirectional"))
      (node (ref "U10") (pin "2") (pinfunction "ALERT_2") (pintype "output"))
    )
    (net (code "6") (name "AGND") (class "Default")
      (node (ref "C10") (pin "2") (pinfunction "2_2") (pintype "passive"))
      (node (ref "C11") (pin "2") (pinfunction "2_2") (pintype "passive"))
      (node (ref "C12") (pin "2") (pinfunction "2_2") (pintype "passive"))
      (node (ref "C15") (pin "2") (pinfunction "2_2") (pintype "passive"))
      (node (ref "C17") (pin "2") (pinfunction "2_2") (pintype "passive"))
      (node (ref "C18") (pin "2") (pinfunction "2_2") (pintype "passive"))
      (node (ref "C19") (pin "2") (pinfunction "2_2") (pintype "passive"))
      (node (ref "C20") (pin "2") (pinfunction "2_2") (pintype "passive"))
      (node (ref "C21") (pin "2") (pinfunction "2_2") (pintype "passive"))
      (node (ref "C22") (pin "2") (pinfunction "2_2") (pintype "passive"))
      (node (ref "C23") (pin "2") (pinfunction "2_2") (pintype "passive"))
      (node (ref "C4") (pin "2") (pinfunction "2_2") (pintype "passive"))
      (node (ref "C5") (pin "2") (pinfunction "2_2") (pintype "passive"))
      (node (ref "C7") (pin "2") (pinfunction "2_2") (pintype "passive"))
      (node (ref "C9") (pin "2") (pinfunction "2_2") (pintype "passive"))
      (node (ref "J21") (pin "1") (pinfunction "1_1") (pintype "passive"))
      (node (ref "J22") (pin "1") (pinfunction "1_1") (pintype "passive"))
      (node (ref "J23") (pin "1") (pinfunction "1_1") (pintype "passive"))
      (node (ref "J24") (pin "1") (pinfunction "1_1") (pintype "passive"))
      (node (ref "J25") (pin "1") (pinfunction "1_1") (pintype "passive"))
      (node (ref "J26") (pin "1") (pinfunction "1_1") (pintype "passive"))
      (node (ref "J27") (pin "1") (pinfunction "1_1") (pintype "passive"))
      (node (ref "J28") (pin "1") (pinfunction "1_1") (pintype "passive"))
      (node (ref "R55") (pin "1") (pinfunction "1_1") (pintype "passive"))
      (node (ref "R56") (pin "1") (pinfunction "1_1") (pintype "passive"))
      (node (ref "R59") (pin "1") (pinfunction "1_1") (pintype "passive"))
      (node (ref "R64") (pin "2") (pinfunction "2_2") (pintype "passive"))
      (node (ref "R70") (pin "1") (pinfunction "1_1") (pintype "passive"))
      (node (ref "R71") (pin "1") (pinfunction "1_1") (pintype "passive"))
      (node (ref "R75") (pin "1") (pinfunction "1_1") (pintype "passive"))
      (node (ref "R87") (pin "1") (pinfunction "1_1") (pintype "passive"))
      (node (ref "R89") (pin "1") (pinfunction "1_1") (pintype "passive"))
      (node (ref "U10") (pin "1") (pinfunction "ADDR_1") (pintype "input"))
      (node (ref "U10") (pin "3") (pinfunction "GND_3") (pintype "power_in"))
      (node (ref "U10") (pin "7") (pinfunction "AIN3_7") (pintype "input"))
      (node (ref "U11") (pin "4") (pinfunction "V-_4") (pintype "power_in"))
      (node (ref "U18") (pin "6") (pinfunction "~{E}_6") (pintype "input"))
      (node (ref "U18") (pin "7") (pinfunction "VEE_7") (pintype "bidirectional"))
      (node (ref "U18") (pin "8") (pinfunction "GND_8") (pintype "bidirectional"))
      (node (ref "U6") (pin "4") (pinfunction "V-_4") (pintype "power_in"))
    )
    (net (code "7") (name "AVCC") (class "Default")
      (node (ref "C10") (pin "1") (pinfunction "1_1") (pintype "passive"))
      (node (ref "C15") (pin "1") (pinfunction "1_1") (pintype "passive"))
      (node (ref "C5") (pin "1") (pinfunction "1_1") (pintype "passive"))
      (node (ref "C7") (pin "1") (pinfunction "1_1") (pintype "passive"))
      (node (ref "R78") (pin "2") (pinfunction "2_2") (pintype "passive"))
      (node (ref "R90") (pin "2") (pinfunction "2_2") (pintype "passive"))
      (node (ref "R91") (pin "2") (pinfunction "2_2") (pintype "passive"))
      (node (ref "R92") (pin "2") (pinfunction "2_2") (pintype "passive"))
      (node (ref "R93") (pin "2") (pinfunction "2_2") (pintype "passive"))
      (node (ref "R94") (pin "2") (pinfunction "2_2") (pintype "passive"))
      (node (ref "U10") (pin "8") (pinfunction "VCC_8") (pintype "power_in"))
      (node (ref "U11") (pin "8") (pinfunction "V+_8") (pintype "power_in"))
      (node (ref "U18") (pin "16") (pinfunction "VCC_16") (pintype "bidirectional"))
      (node (ref "U6") (pin "8") (pinfunction "V+_8") (pintype "power_in"))
    )
    (net (code "8") (name "D0") (class "Default")
      (node (ref "PCB1") (pin "P$21") (pinfunction "GPIO9_P$21") (pintype "bidirectional"))
      (node (ref "R60") (pin "2") (pinfunction "2_2") (pintype "passive"))
    )
    (net (code "9") (name "D1") (class "Default")
      (node (ref "PCB1") (pin "P$23") (pinfunction "GPIO11_P$23") (pintype "bidirectional"))
      (node (ref "R61") (pin "2") (pinfunction "2_2") (pintype "passive"))
    )
    (net (code "10") (name "D2") (class "Default")
      (node (ref "PCB1") (pin "P$24") (pinfunction "GPIO8_P$24") (pintype "bidirectional"))
      (node (ref "R62") (pin "2") (pinfunction "2_2") (pintype "passive"))
    )
    (net (code "11") (name "DCMOTORAENCA") (class "Default")
      (node (ref "PCB1") (pin "P$18") (pinfunction "GPIO24_P$18") (pintype "bidirectional"))
      (node (ref "U14") (pin "4") (pinfunction "4_4") (pintype "passive"))
    )
    (net (code "12") (name "DCMOTORAENCB") (class "Default")
      (node (ref "PCB1") (pin "P$16") (pinfunction "GPIO23_P$16") (pintype "bidirectional"))
      (node (ref "U15") (pin "4") (pinfunction "4_4") (pintype "passive"))
    )
    (net (code "13") (name "DCMOTORBENCA") (class "Default")
      (node (ref "PCB1") (pin "P$26") (pinfunction "GPIO7_P$26") (pintype "bidirectional"))
      (node (ref "U12") (pin "4") (pinfunction "4_4") (pintype "passive"))
    )
    (net (code "14") (name "DCMOTORBENCB") (class "Default")
      (node (ref "PCB1") (pin "P$22") (pinfunction "GPIO25_P$22") (pintype "bidirectional"))
      (node (ref "U13") (pin "4") (pinfunction "4_4") (pintype "passive"))
    )
    (net (code "15") (name "GND") (class "Default")
      (node (ref "B1") (pin "-") (pinfunction "-_-") (pintype "bidirectional"))
      (node (ref "C1") (pin "2") (pinfunction "2_2") (pintype "passive"))
      (node (ref "C13") (pin "2") (pinfunction "2_2") (pintype "passive"))
      (node (ref "C14") (pin "2") (pinfunction "2_2") (pintype "passive"))
      (node (ref "C16") (pin "2") (pinfunction "2_2") (pintype "passive"))
      (node (ref "C2") (pin "2") (pinfunction "2_2") (pintype "passive"))
      (node (ref "C24") (pin "2") (pinfunction "2_2") (pintype "passive"))
      (node (ref "C25") (pin "2") (pinfunction "2_2") (pintype "passive"))
      (node (ref "C26") (pin "2") (pinfunction "2_2") (pintype "passive"))
      (node (ref "C27") (pin "2") (pinfunction "2_2") (pintype "passive"))
      (node (ref "C28") (pin "2") (pinfunction "2_2") (pintype "passive"))
      (node (ref "C29") (pin "2") (pinfunction "2_2") (pintype "passive"))
      (node (ref "C3") (pin "2") (pinfunction "2_2") (pintype "passive"))
      (node (ref "C6") (pin "2") (pinfunction "2_2") (pintype "passive"))
      (node (ref "C8") (pin "2") (pinfunction "2_2") (pintype "passive"))
      (node (ref "D31") (pin "A") (pinfunction "A_A") (pintype "bidirectional"))
      (node (ref "D32") (pin "C") (pinfunction "C_C") (pintype "passive"))
      (node (ref "D33") (pin "C") (pinfunction "C_C") (pintype "passive"))
      (node (ref "D34") (pin "C") (pinfunction "C_C") (pintype "passive"))
      (node (ref "J11") (pin "1") (pinfunction "1_1") (pintype "passive"))
      (node (ref "J12") (pin "1") (pinfunction "1_1") (pintype "passive"))
      (node (ref "J14") (pin "4") (pinfunction "4_4") (pintype "passive"))
      (node (ref "J15") (pin "4") (pinfunction "4_4") (pintype "passive"))
      (node (ref "J17") (pin "1") (pinfunction "1_1") (pintype "passive"))
      (node (ref "J18") (pin "1") (pinfunction "1_1") (pintype "passive"))
      (node (ref "J19") (pin "1") (pinfunction "1_1") (pintype "passive"))
      (node (ref "J19") (pin "2") (pinfunction "2_2") (pintype "passive"))
      (node (ref "J19") (pin "3") (pinfunction "3_3") (pintype "passive"))
      (node (ref "J19") (pin "4") (pinfunction "4_4") (pintype "passive"))
      (node (ref "J19") (pin "5") (pinfunction "5_5") (pintype "passive"))
      (node (ref "J19") (pin "6") (pinfunction "6_6") (pintype "passive"))
      (node (ref "J20") (pin "1") (pinfunction "1_1") (pintype "passive"))
      (node (ref "J30") (pin "1") (pinfunction "1_1") (pintype "passive"))
      (node (ref "JP2") (pin "1") (pinfunction "1_1") (pintype "passive"))
      (node (ref "PCB1") (pin "P$14") (pinfunction "GND_P$14") (pintype "bidirectional"))
      (node (ref "PCB1") (pin "P$20") (pinfunction "GND_P$20") (pintype "bidirectional"))
      (node (ref "PCB1") (pin "P$25") (pinfunction "GND_P$25") (pintype "bidirectional"))
      (node (ref "PCB1") (pin "P$30") (pinfunction "GND_P$30") (pintype "bidirectional"))
      (node (ref "PCB1") (pin "P$34") (pinfunction "GND_P$34") (pintype "bidirectional"))
      (node (ref "PCB1") (pin "P$39") (pinfunction "GND_P$39") (pintype "bidirectional"))
      (node (ref "PCB1") (pin "P$6") (pinfunction "GND_P$6") (pintype "bidirectional"))
      (node (ref "PCB1") (pin "P$9") (pinfunction "GND_P$9") (pintype "bidirectional"))
      (node (ref "Q11") (pin "2") (pinfunction "S_2") (pintype "passive"))
      (node (ref "Q12") (pin "2") (pinfunction "S_2") (pintype "passive"))
      (node (ref "Q13") (pin "2") (pinfunction "S_2") (pintype "passive"))
      (node (ref "Q14") (pin "2") (pinfunction "S_2") (pintype "passive"))
      (node (ref "Q15") (pin "2") (pinfunction "S_2") (pintype "passive"))
      (node (ref "Q16") (pin "2") (pinfunction "S_2") (pintype "passive"))
      (node (ref "Q17") (pin "2") (pinfunction "S_2") (pintype "passive"))
      (node (ref "Q18") (pin "2") (pinfunction "S_2") (pintype "passive"))
      (node (ref "Q19") (pin "2") (pinfunction "S_2") (pintype "passive"))
      (node (ref "Q20") (pin "2") (pinfunction "S_2") (pintype "passive"))
      (node (ref "Q31") (pin "2") (pinfunction "S_2") (pintype "passive"))
      (node (ref "Q32") (pin "2") (pinfunction "S_2") (pintype "passive"))
      (node (ref "Q33") (pin "2") (pinfunction "S_2") (pintype "passive"))
      (node (ref "Q34") (pin "2") (pinfunction "S_2") (pintype "passive"))
      (node (ref "Q35") (pin "2") (pinfunction "S_2") (pintype "passive"))
      (node (ref "Q36") (pin "2") (pinfunction "S_2") (pintype "passive"))
      (node (ref "Q37") (pin "2") (pinfunction "S_2") (pintype "passive"))
      (node (ref "Q38") (pin "2") (pinfunction "S_2") (pintype "passive"))
      (node (ref "Q39") (pin "2") (pinfunction "S_2") (pintype "passive"))
      (node (ref "Q40") (pin "2") (pinfunction "S_2") (pintype "passive"))
      (node (ref "Q42") (pin "2") (pinfunction "S_2") (pintype "passive"))
      (node (ref "Q43") (pin "2") (pinfunction "S_2") (pintype "passive"))
      (node (ref "Q44") (pin "2") (pinfunction "S_2") (pintype "passive"))
      (node (ref "Q45") (pin "2") (pinfunction "S_2") (pintype "passive"))
      (node (ref "Q46") (pin "2") (pinfunction "S_2") (pintype "passive"))
      (node (ref "Q47") (pin "2") (pinfunction "S_2") (pintype "passive"))
      (node (ref "R1") (pin "1") (pinfunction "1_1") (pintype "passive"))
      (node (ref "R10") (pin "1") (pinfunction "1_1") (pintype "passive"))
      (node (ref "R11") (pin "1") (pinfunction "1_1") (pintype "passive"))
      (node (ref "R12") (pin "1") (pinfunction "1_1") (pintype "passive"))
      (node (ref "R13") (pin "1") (pinfunction "1_1") (pintype "passive"))
      (node (ref "R14") (pin "1") (pinfunction "1_1") (pintype "passive"))
      (node (ref "R16") (pin "1") (pinfunction "1_1") (pintype "passive"))
      (node (ref "R17") (pin "1") (pinfunction "1_1") (pintype "passive"))
      (node (ref "R2") (pin "1") (pinfunction "1_1") (pintype "passive"))
      (node (ref "R3") (pin "1") (pinfunction "1_1") (pintype "passive"))
      (node (ref "R33") (pin "2") (pinfunction "2_2") (pintype "passive"))
      (node (ref "R34") (pin "2") (pinfunction "2_2") (pintype "passive"))
      (node (ref "R4") (pin "1") (pinfunction "1_1") (pintype "passive"))
      (node (ref "R43") (pin "2") (pinfunction "2_2") (pintype "passive"))
      (node (ref "R5") (pin "1") (pinfunction "1_1") (pintype "passive"))
      (node (ref "R6") (pin "1") (pinfunction "1_1") (pintype "passive"))
      (node (ref "R64") (pin "1") (pinfunction "1_1") (pintype "passive"))
      (node (ref "R7") (pin "1") (pinfunction "1_1") (pintype "passive"))
      (node (ref "R8") (pin "1") (pinfunction "1_1") (pintype "passive"))
      (node (ref "R80") (pin "1") (pinfunction "1_1") (pintype "passive"))
      (node (ref "R81") (pin "1") (pinfunction "1_1") (pintype "passive"))
      (node (ref "R82") (pin "1") (pinfunction "1_1") (pintype "passive"))
      (node (ref "R83") (pin "1") (pinfunction "1_1") (pintype "passive"))
      (node (ref "R84") (pin "1") (pinfunction "1_1") (pintype "passive"))
      (node (ref "R85") (pin "1") (pinfunction "1_1") (pintype "passive"))
      (node (ref "R9") (pin "1") (pinfunction "1_1") (pintype "passive"))
      (node (ref "S1") (pin "P$1") (pinfunction "1_P$1") (pintype "passive"))
      (node (ref "S2") (pin "P$1") (pinfunction "1_P$1") (pintype "passive"))
      (node (ref "TP1") (pin "1") (pinfunction "P$1_1") (pintype "bidirectional"))
      (node (ref "U12") (pin "2") (pinfunction "2_2") (pintype "passive"))
      (node (ref "U12") (pin "3") (pinfunction "3_3") (pintype "passive"))
      (node (ref "U13") (pin "2") (pinfunction "2_2") (pintype "passive"))
      (node (ref "U13") (pin "3") (pinfunction "3_3") (pintype "passive"))
      (node (ref "U14") (pin "2") (pinfunction "2_2") (pintype "passive"))
      (node (ref "U14") (pin "3") (pinfunction "3_3") (pintype "passive"))
      (node (ref "U15") (pin "2") (pinfunction "2_2") (pintype "passive"))
      (node (ref "U15") (pin "3") (pinfunction "3_3") (pintype "passive"))
      (node (ref "U16") (pin "10") (pinfunction "VSS_10") (pintype "power_in"))
      (node (ref "U16") (pin "15") (pinfunction "A0_15") (pintype "input"))
      (node (ref "U16") (pin "16") (pinfunction "A1_16") (pintype "input"))
      (node (ref "U16") (pin "17") (pinfunction "A2_17") (pintype "input"))
      (node (ref "U17") (pin "1") (pinfunction "A0_1") (pintype "bidirectional"))
      (node (ref "U17") (pin "2") (pinfunction "A1_2") (pintype "bidirectional"))
      (node (ref "U17") (pin "3") (pinfunction "A2_3") (pintype "bidirectional"))
      (node (ref "U17") (pin "4") (pinfunction "GND_4") (pintype "bidirectional"))
      (node (ref "U19") (pin "4") (pinfunction "GND_4") (pintype "bidirectional"))
      (node (ref "U20") (pin "GND") (pinfunction "GND_GND") (pintype "passive"))
      (node (ref "U3") (pin "6") (pinfunction "GND6_6") (pintype "bidirectional"))
      (node (ref "U3") (pin "8") (pinfunction "GND8_8") (pintype "bidirectional"))
      (node (ref "U5") (pin "1") (pinfunction "A0_1") (pintype "bidirectional"))
      (node (ref "U5") (pin "14") (pinfunction "GND_14") (pintype "power_in"))
      (node (ref "U5") (pin "2") (pinfunction "A1_2") (pintype "bidirectional"))
      (node (ref "U5") (pin "23") (pinfunction "~{OE}_23") (pintype "input"))
      (node (ref "U5") (pin "25") (pinfunction "EXTCLK_25") (pintype "input"))
      (node (ref "U5") (pin "3") (pinfunction "A2_3") (pintype "bidirectional"))
      (node (ref "U5") (pin "4") (pinfunction "A3_4") (pintype "bidirectional"))
      (node (ref "U5") (pin "5") (pinfunction "A4_5") (pintype "bidirectional"))
      (node (ref "U7") (pin "1") (pinfunction "A1_1") (pintype "bidirectional"))
      (node (ref "U7") (pin "2") (pinfunction "A0_2") (pintype "bidirectional"))
      (node (ref "U7") (pin "6") (pinfunction "GND_6") (pintype "bidirectional"))
      (node (ref "U8") (pin "4") (pinfunction "GND_4") (pintype "passive"))
      (node (ref "U8") (pin "6") (pinfunction "A1_6") (pintype "input"))
      (node (ref "U8") (pin "7") (pinfunction "A0_7") (pintype "input"))
      (node (ref "U9") (pin "IN-") (pinfunction "VIN-_IN-") (pintype "bidirectional"))
      (node (ref "U9") (pin "OUT-") (pinfunction "VOUT-_OUT-") (pintype "bidirectional"))
    )
    (net (code "16") (name "ID_SC") (class "Default")
      (node (ref "PCB1") (pin "P$28") (pinfunction "ID_SC*_P$28") (pintype "bidirectional"))
      (node (ref "R73") (pin "1") (pinfunction "1_1") (pintype "passive"))
      (node (ref "U17") (pin "6") (pinfunction "SCL_6") (pintype "bidirectional"))
    )
    (net (code "17") (name "ID_SD") (class "Default")
      (node (ref "PCB1") (pin "P$27") (pinfunction "ID_SD*_P$27") (pintype "bidirectional"))
      (node (ref "R74") (pin "1") (pinfunction "1_1") (pintype "passive"))
      (node (ref "U17") (pin "5") (pinfunction "SDA_5") (pintype "bidirectional"))
    )
    (net (code "18") (name "INPUTINTERRUPT") (class "Default")
      (node (ref "PCB1") (pin "P$11") (pinfunction "GPIO17_P$11") (pintype "bidirectional"))
      (node (ref "U16") (pin "19") (pinfunction "INTB_19") (pintype "output"))
    )
    (net (code "19") (name "MOTORA_SENSE") (class "Default")
      (node (ref "Q1") (pin "2") (pinfunction "S_2") (pintype "passive"))
      (node (ref "Q2") (pin "2") (pinfunction "S_2") (pintype "passive"))
      (node (ref "R33") (pin "1") (pinfunction "1_1") (pintype "passive"))
      (node (ref "R44") (pin "1") (pinfunction "1_1") (pintype "passive"))
    )
    (net (code "20") (name "MOTORB_SENSE") (class "Default")
      (node (ref "Q3") (pin "2") (pinfunction "S_2") (pintype "passive"))
      (node (ref "Q4") (pin "2") (pinfunction "S_2") (pintype "passive"))
      (node (ref "R34") (pin "1") (pinfunction "1_1") (pintype "passive"))
      (node (ref "R57") (pin "1") (pinfunction "1_1") (pintype "passive"))
    )
    (net (code "21") (name "Net-(D1-PadC)") (class "Default")
      (node (ref "D1") (pin "C") (pinfunction "C_C") (pintype "passive"))
      (node (ref "R14") (pin "2") (pinfunction "2_2") (pintype "passive"))
    )
    (net (code "22") (name "Net-(D2-PadC)") (class "Default")
      (node (ref "D2") (pin "C") (pinfunction "C_C") (pintype "passive"))
      (node (ref "R16") (pin "2") (pinfunction "2_2") (pintype "passive"))
    )
    (net (code "23") (name "Net-(D3-PadC)") (class "Default")
      (node (ref "D3") (pin "C") (pinfunction "C_C") (pintype "passive"))
      (node (ref "R17") (pin "2") (pinfunction "2_2") (pintype "passive"))
    )
    (net (code "24") (name "Net-(D4-PadC)") (class "Default")
      (node (ref "D4") (pin "C") (pinfunction "C_C") (pintype "passive"))
      (node (ref "R1") (pin "2") (pinfunction "2_2") (pintype "passive"))
    )
    (net (code "25") (name "Net-(D5-PadC)") (class "Default")
      (node (ref "D5") (pin "C") (pinfunction "C_C") (pintype "passive"))
      (node (ref "R2") (pin "2") (pinfunction "2_2") (pintype "passive"))
    )
    (net (code "26") (name "Net-(D6-PadC)") (class "Default")
      (node (ref "D6") (pin "C") (pinfunction "C_C") (pintype "passive"))
      (node (ref "R3") (pin "2") (pinfunction "2_2") (pintype "passive"))
    )
    (net (code "27") (name "Net-(D7-PadC)") (class "Default")
      (node (ref "D7") (pin "C") (pinfunction "C_C") (pintype "passive"))
      (node (ref "R4") (pin "2") (pinfunction "2_2") (pintype "passive"))
    )
    (net (code "28") (name "Net-(D8-PadC)") (class "Default")
      (node (ref "D8") (pin "C") (pinfunction "C_C") (pintype "passive"))
      (node (ref "R5") (pin "2") (pinfunction "2_2") (pintype "passive"))
    )
    (net (code "29") (name "Net-(D9-PadC)") (class "Default")
      (node (ref "D9") (pin "C") (pinfunction "C_C") (pintype "passive"))
      (node (ref "R6") (pin "2") (pinfunction "2_2") (pintype "passive"))
    )
    (net (code "30") (name "Net-(D10-PadC)") (class "Default")
      (node (ref "D10") (pin "C") (pinfunction "C_C") (pintype "passive"))
      (node (ref "R7") (pin "2") (pinfunction "2_2") (pintype "passive"))
    )
    (net (code "31") (name "Net-(D11-PadC)") (class "Default")
      (node (ref "D11") (pin "C") (pinfunction "C_C") (pintype "passive"))
      (node (ref "R8") (pin "2") (pinfunction "2_2") (pintype "passive"))
    )
    (net (code "32") (name "Net-(D12-PadC)") (class "Default")
      (node (ref "D12") (pin "C") (pinfunction "C_C") (pintype "passive"))
      (node (ref "R9") (pin "2") (pinfunction "2_2") (pintype "passive"))
    )
    (net (code "33") (name "Net-(D13-PadC)") (class "Default")
      (node (ref "D13") (pin "C") (pinfunction "C_C") (pintype "passive"))
      (node (ref "R10") (pin "2") (pinfunction "2_2") (pintype "passive"))
    )
    (net (code "34") (name "Net-(D14-PadC)") (class "Default")
      (node (ref "D14") (pin "C") (pinfunction "C_C") (pintype "passive"))
      (node (ref "R11") (pin "2") (pinfunction "2_2") (pintype "passive"))
    )
    (net (code "35") (name "Net-(D15-PadC)") (class "Default")
      (node (ref "D15") (pin "C") (pinfunction "C_C") (pintype "passive"))
      (node (ref "R12") (pin "2") (pinfunction "2_2") (pintype "passive"))
    )
    (net (code "36") (name "Net-(D16-PadC)") (class "Default")
      (node (ref "D16") (pin "C") (pinfunction "C_C") (pintype "passive"))
      (node (ref "R13") (pin "2") (pinfunction "2_2") (pintype "passive"))
    )
    (net (code "37") (name "Net-(D17-PadA)") (class "Default")
      (node (ref "D17") (pin "A") (pinfunction "A_A") (pintype "passive"))
      (node (ref "D19") (pin "C") (pinfunction "C_C") (pintype "passive"))
      (node (ref "R15") (pin "1") (pinfunction "1_1") (pintype "passive"))
    )
    (net (code "38") (name "Net-(D18-PadA)") (class "Default")
      (node (ref "D18") (pin "A") (pinfunction "A_A") (pintype "passive"))
      (node (ref "D20") (pin "C") (pinfunction "C_C") (pintype "passive"))
      (node (ref "R18") (pin "1") (pinfunction "1_1") (pintype "passive"))
    )
    (net (code "39") (name "Net-(D25-PadC)") (class "Default")
      (node (ref "D25") (pin "C") (pinfunction "C_C") (pintype "passive"))
      (node (ref "R25") (pin "2") (pinfunction "2_2") (pintype "passive"))
    )
    (net (code "40") (name "Net-(D26-PadC)") (class "Default")
      (node (ref "D26") (pin "C") (pinfunction "C_C") (pintype "passive"))
      (node (ref "R26") (pin "2") (pinfunction "2_2") (pintype "passive"))
    )
    (net (code "41") (name "Net-(D27-PadA)") (class "Default")
      (node (ref "D27") (pin "A") (pinfunction "A_A") (pintype "passive"))
      (node (ref "R29") (pin "1") (pinfunction "1_1") (pintype "passive"))
    )
    (net (code "42") (name "Net-(D28-PadA)") (class "Default")
      (node (ref "D28") (pin "A") (pinfunction "A_A") (pintype "passive"))
      (node (ref "R30") (pin "1") (pinfunction "1_1") (pintype "passive"))
    )
    (net (code "43") (name "Net-(D29-PadA)") (class "Default")
      (node (ref "D29") (pin "A") (pinfunction "A_A") (pintype "passive"))
      (node (ref "R31") (pin "1") (pinfunction "1_1") (pintype "passive"))
    )
    (net (code "44") (name "Net-(D30-PadA)") (class "Default")
      (node (ref "D30") (pin "A") (pinfunction "A_A") (pintype "passive"))
      (node (ref "R32") (pin "1") (pinfunction "1_1") (pintype "passive"))
    )
    (net (code "45") (name "Net-(D32-PadA)") (class "Default")
      (node (ref "D32") (pin "A") (pinfunction "A_A") (pintype "passive"))
      (node (ref "R60") (pin "1") (pinfunction "1_1") (pintype "passive"))
    )
    (net (code "46") (name "Net-(D33-PadA)") (class "Default")
      (node (ref "D33") (pin "A") (pinfunction "A_A") (pintype "passive"))
      (node (ref "R61") (pin "1") (pinfunction "1_1") (pintype "passive"))
    )
    (net (code "47") (name "Net-(D34-PadA)") (class "Default")
      (node (ref "D34") (pin "A") (pinfunction "A_A") (pintype "passive"))
      (node (ref "R62") (pin "1") (pinfunction "1_1") (pintype "passive"))
    )
    (net (code "48") (name "Net-(D35-PadA)") (class "Default")
      (node (ref "D35") (pin "A") (pinfunction "A_A") (pintype "bidirectional"))
      (node (ref "J26") (pin "2") (pinfunction "2_2") (pintype "passive"))
    )
    (net (code "49") (name "Net-(D35-PadC)") (class "Default")
      (node (ref "D35") (pin "C") (pinfunction "C_C") (pintype "bidirectional"))
      (node (ref "R86") (pin "2") (pinfunction "2_2") (pintype "passive"))
    )
    (net (code "50") (name "Net-(D36-PadA)") (class "Default")
      (node (ref "D36") (pin "A") (pinfunction "A_A") (pintype "bidirectional"))
      (node (ref "J25") (pin "2") (pinfunction "2_2") (pintype "passive"))
    )
    (net (code "51") (name "Net-(D36-PadC)") (class "Default")
      (node (ref "D36") (pin "C") (pinfunction "C_C") (pintype "bidirectional"))
      (node (ref "R76") (pin "2") (pinfunction "2_2") (pintype "passive"))
    )
    (net (code "52") (name "Net-(F1-P$1-Pad1@1)") (class "Default")
      (node (ref "F1") (pin "1@1") (pinfunction "P$1_1@1") (pintype "bidirectional"))
      (node (ref "F1") (pin "1@2") (pinfunction "P$1_1@2") (pintype "bidirectional"))
      (node (ref "J20") (pin "2") (pinfunction "2_2") (pintype "passive"))
    )
    (net (code "53") (name "Net-(J12-Pad2)") (class "Default")
      (node (ref "J12") (pin "2") (pinfunction "2_2") (pintype "passive"))
      (node (ref "J13") (pin "1") (pinfunction "1_1") (pintype "passive"))
    )
    (net (code "54") (name "Net-(J14-Pad2)") (class "Default")
      (node (ref "J14") (pin "2") (pinfunction "2_2") (pintype "passive"))
      (node (ref "R65") (pin "2") (pinfunction "2_2") (pintype "passive"))
    )
    (net (code "55") (name "Net-(J14-Pad3)") (class "Default")
      (node (ref "J14") (pin "3") (pinfunction "3_3") (pintype "passive"))
      (node (ref "R66") (pin "2") (pinfunction "2_2") (pintype "passive"))
    )
    (net (code "56") (name "Net-(J15-Pad2)") (class "Default")
      (node (ref "J15") (pin "2") (pinfunction "2_2") (pintype "passive"))
      (node (ref "R67") (pin "2") (pinfunction "2_2") (pintype "passive"))
    )
    (net (code "57") (name "Net-(J15-Pad3)") (class "Default")
      (node (ref "J15") (pin "3") (pinfunction "3_3") (pintype "passive"))
      (node (ref "R68") (pin "2") (pinfunction "2_2") (pintype "passive"))
    )
    (net (code "58") (name "Net-(J27-Pad2)") (class "Default")
      (node (ref "J27") (pin "2") (pinfunction "2_2") (pintype "passive"))
      (node (ref "R88") (pin "2") (pinfunction "2_2") (pintype "passive"))
    )
    (net (code "59") (name "Net-(K1-COM)") (class "Default")
      (node (ref "J8") (pin "2") (pinfunction "2_2") (pintype "passive"))
      (node (ref "K1") (pin "1") (pinfunction "COM_1") (pintype "bidirectional"))
    )
    (net (code "60") (name "Net-(K1-NC)") (class "Default")
      (node (ref "J8") (pin "3") (pinfunction "3_3") (pintype "passive"))
      (node (ref "K1") (pin "5") (pinfunction "NC_5") (pintype "bidirectional"))
    )
    (net (code "61") (name "Net-(K1-NO)") (class "Default")
      (node (ref "J8") (pin "1") (pinfunction "1_1") (pintype "passive"))
      (node (ref "K1") (pin "4") (pinfunction "NO_4") (pintype "bidirectional"))
    )
    (net (code "62") (name "Net-(K1-V+)") (class "Default")
      (node (ref "D21") (pin "C") (pinfunction "C_C") (pintype "bidirectional"))
      (node (ref "D22") (pin "C") (pinfunction "C_C") (pintype "bidirectional"))
      (node (ref "D23") (pin "C") (pinfunction "C_C") (pintype "bidirectional"))
      (node (ref "D24") (pin "C") (pinfunction "C_C") (pintype "bidirectional"))
      (node (ref "K1") (pin "2") (pinfunction "V+_2") (pintype "bidirectional"))
      (node (ref "K2") (pin "2") (pinfunction "V+_2") (pintype "bidirectional"))
      (node (ref "K3") (pin "2") (pinfunction "V+_2") (pintype "bidirectional"))
      (node (ref "K4") (pin "2") (pinfunction "V+_2") (pintype "bidirectional"))
      (node (ref "R19") (pin "1") (pinfunction "1_1") (pintype "passive"))
      (node (ref "R28") (pin "1") (pinfunction "1_1") (pintype "passive"))
      (node (ref "R29") (pin "2") (pinfunction "2_2") (pintype "passive"))
      (node (ref "R30") (pin "2") (pinfunction "2_2") (pintype "passive"))
      (node (ref "R31") (pin "2") (pinfunction "2_2") (pintype "passive"))
      (node (ref "R32") (pin "2") (pinfunction "2_2") (pintype "passive"))
    )
    (net (code "63") (name "Net-(K1-V-)") (class "Default")
      (node (ref "D22") (pin "A") (pinfunction "A_A") (pintype "bidirectional"))
      (node (ref "D28") (pin "C") (pinfunction "C_C") (pintype "passive"))
      (node (ref "K1") (pin "3") (pinfunction "V-_3") (pintype "bidirectional"))
      (node (ref "Q19") (pin "3") (pinfunction "D_3") (pintype "passive"))
    )
    (net (code "64") (name "Net-(K2-COM)") (class "Default")
      (node (ref "J7") (pin "2") (pinfunction "2_2") (pintype "passive"))
      (node (ref "K2") (pin "1") (pinfunction "COM_1") (pintype "bidirectional"))
    )
    (net (code "65") (name "Net-(K2-NC)") (class "Default")
      (node (ref "J7") (pin "3") (pinfunction "3_3") (pintype "passive"))
      (node (ref "K2") (pin "5") (pinfunction "NC_5") (pintype "bidirectional"))
    )
    (net (code "66") (name "Net-(K2-NO)") (class "Default")
      (node (ref "J7") (pin "1") (pinfunction "1_1") (pintype "passive"))
      (node (ref "K2") (pin "4") (pinfunction "NO_4") (pintype "bidirectional"))
    )
    (net (code "67") (name "Net-(K2-V-)") (class "Default")
      (node (ref "D21") (pin "A") (pinfunction "A_A") (pintype "bidirectional"))
      (node (ref "D27") (pin "C") (pinfunction "C_C") (pintype "passive"))
      (node (ref "K2") (pin "3") (pinfunction "V-_3") (pintype "bidirectional"))
      (node (ref "Q18") (pin "3") (pinfunction "D_3") (pintype "passive"))
    )
    (net (code "68") (name "Net-(K3-COM)") (class "Default")
      (node (ref "J9") (pin "2") (pinfunction "2_2") (pintype "passive"))
      (node (ref "K3") (pin "1") (pinfunction "COM_1") (pintype "bidirectional"))
    )
    (net (code "69") (name "Net-(K3-NC)") (class "Default")
      (node (ref "J9") (pin "3") (pinfunction "3_3") (pintype "passive"))
      (node (ref "K3") (pin "5") (pinfunction "NC_5") (pintype "bidirectional"))
    )
    (net (code "70") (name "Net-(K3-NO)") (class "Default")
      (node (ref "J9") (pin "1") (pinfunction "1_1") (pintype "passive"))
      (node (ref "K3") (pin "4") (pinfunction "NO_4") (pintype "bidirectional"))
    )
    (net (code "71") (name "Net-(K3-V-)") (class "Default")
      (node (ref "D23") (pin "A") (pinfunction "A_A") (pintype "bidirectional"))
      (node (ref "D29") (pin "C") (pinfunction "C_C") (pintype "passive"))
      (node (ref "K3") (pin "3") (pinfunction "V-_3") (pintype "bidirectional"))
      (node (ref "Q17") (pin "3") (pinfunction "D_3") (pintype "passive"))
    )
    (net (code "72") (name "Net-(K4-COM)") (class "Default")
      (node (ref "J10") (pin "2") (pinfunction "2_2") (pintype "passive"))
      (node (ref "K4") (pin "1") (pinfunction "COM_1") (pintype "bidirectional"))
    )
    (net (code "73") (name "Net-(K4-NC)") (class "Default")
      (node (ref "J10") (pin "3") (pinfunction "3_3") (pintype "passive"))
      (node (ref "K4") (pin "5") (pinfunction "NC_5") (pintype "bidirectional"))
    )
    (net (code "74") (name "Net-(K4-NO)") (class "Default")
      (node (ref "J10") (pin "1") (pinfunction "1_1") (pintype "passive"))
      (node (ref "K4") (pin "4") (pinfunction "NO_4") (pintype "bidirectional"))
    )
    (net (code "75") (name "Net-(K4-V-)") (class "Default")
      (node (ref "D24") (pin "A") (pinfunction "A_A") (pintype "bidirectional"))
      (node (ref "D30") (pin "C") (pinfunction "C_C") (pintype "passive"))
      (node (ref "K4") (pin "3") (pinfunction "V-_3") (pintype "bidirectional"))
      (node (ref "Q20") (pin "3") (pinfunction "D_3") (pintype "passive"))
    )
    (net (code "76") (name "Net-(Q1-D)") (class "Default")
      (node (ref "D1") (pin "A") (pinfunction "A_A") (pintype "passive"))
      (node (ref "D17") (pin "C") (pinfunction "C_C") (pintype "passive"))
      (node (ref "D19") (pin "A") (pinfunction "A_A") (pintype "passive"))
      (node (ref "J1") (pin "1") (pinfunction "1_1") (pintype "passive"))
      (node (ref "Q1") (pin "3") (pinfunction "D_3") (pintype "passive"))
      (node (ref "Q21") (pin "3") (pinfunction "D_3") (pintype "passive"))
    )
    (net (code "77") (name "Net-(Q1-G)") (class "Default")
      (node (ref "Q1") (pin "1") (pinfunction "G_1") (pintype "passive"))
      (node (ref "Q21") (pin "1") (pinfunction "G_1") (pintype "passive"))
      (node (ref "Q32") (pin "3") (pinfunction "D_3") (pintype "passive"))
      (node (ref "R36") (pin "1") (pinfunction "1_1") (pintype "passive"))
    )
    (net (code "78") (name "Net-(Q2-D)") (class "Default")
      (node (ref "D2") (pin "A") (pinfunction "A_A") (pintype "passive"))
      (node (ref "J1") (pin "2") (pinfunction "2_2") (pintype "passive"))
      (node (ref "Q2") (pin "3") (pinfunction "D_3") (pintype "passive"))
      (node (ref "Q22") (pin "3") (pinfunction "D_3") (pintype "passive"))
      (node (ref "R15") (pin "2") (pinfunction "2_2") (pintype "passive"))
    )
    (net (code "79") (name "Net-(Q2-G)") (class "Default")
      (node (ref "Q2") (pin "1") (pinfunction "G_1") (pintype "passive"))
      (node (ref "Q22") (pin "1") (pinfunction "G_1") (pintype "passive"))
      (node (ref "Q33") (pin "3") (pinfunction "D_3") (pintype "passive"))
      (node (ref "R37") (pin "1") (pinfunction "1_1") (pintype "passive"))
    )
    (net (code "80") (name "Net-(Q5-D)") (class "Default")
      (node (ref "D5") (pin "A") (pinfunction "A_A") (pintype "passive"))
      (node (ref "J2") (pin "1") (pinfunction "1_1") (pintype "passive"))
      (node (ref "Q5") (pin "3") (pinfunction "D_3") (pintype "passive"))
    )
    (net (code "81") (name "Net-(Q6-D)") (class "Default")
      (node (ref "D7") (pin "A") (pinfunction "A_A") (pintype "passive"))
      (node (ref "J2") (pin "3") (pinfunction "3_3") (pintype "passive"))
      (node (ref "Q6") (pin "3") (pinfunction "D_3") (pintype "passive"))
    )
    (net (code "82") (name "Net-(Q7-D)") (class "Default")
      (node (ref "D9") (pin "A") (pinfunction "A_A") (pintype "passive"))
      (node (ref "J3") (pin "1") (pinfunction "1_1") (pintype "passive"))
      (node (ref "Q7") (pin "3") (pinfunction "D_3") (pintype "passive"))
    )
    (net (code "83") (name "Net-(Q8-D)") (class "Default")
      (node (ref "D11") (pin "A") (pinfunction "A_A") (pintype "passive"))
      (node (ref "J3") (pin "3") (pinfunction "3_3") (pintype "passive"))
      (node (ref "Q8") (pin "3") (pinfunction "D_3") (pintype "passive"))
    )
    (net (code "84") (name "Net-(Q9-D)") (class "Default")
      (node (ref "D13") (pin "A") (pinfunction "A_A") (pintype "passive"))
      (node (ref "J4") (pin "1") (pinfunction "1_1") (pintype "passive"))
      (node (ref "Q9") (pin "3") (pinfunction "D_3") (pintype "passive"))
    )
    (net (code "85") (name "Net-(Q10-D)") (class "Default")
      (node (ref "D15") (pin "A") (pinfunction "A_A") (pintype "passive"))
      (node (ref "J4") (pin "3") (pinfunction "3_3") (pintype "passive"))
      (node (ref "Q10") (pin "3") (pinfunction "D_3") (pintype "passive"))
    )
    (net (code "86") (name "Net-(Q10-G)") (class "Default")
      (node (ref "Q10") (pin "1") (pinfunction "G_1") (pintype "passive"))
      (node (ref "Q16") (pin "3") (pinfunction "D_3") (pintype "passive"))
      (node (ref "R24") (pin "1") (pinfunction "1_1") (pintype "passive"))
    )
    (net (code "87") (name "Net-(Q11-D)") (class "Default")
      (node (ref "Q11") (pin "3") (pinfunction "D_3") (pintype "passive"))
      (node (ref "Q5") (pin "1") (pinfunction "G_1") (pintype "passive"))
      (node (ref "R27") (pin "1") (pinfunction "1_1") (pintype "passive"))
    )
    (net (code "88") (name "Net-(Q11-G)") (class "Default")
      (node (ref "Q11") (pin "1") (pinfunction "G_1") (pintype "passive"))
      (node (ref "U5") (pin "18") (pinfunction "PWM11_18") (pintype "output"))
    )
    (net (code "89") (name "Net-(Q12-D)") (class "Default")
      (node (ref "Q12") (pin "3") (pinfunction "D_3") (pintype "passive"))
      (node (ref "Q6") (pin "1") (pinfunction "G_1") (pintype "passive"))
      (node (ref "R20") (pin "1") (pinfunction "1_1") (pintype "passive"))
    )
    (net (code "90") (name "Net-(Q12-G)") (class "Default")
      (node (ref "Q12") (pin "1") (pinfunction "G_1") (pintype "passive"))
      (node (ref "U5") (pin "16") (pinfunction "PWM9_16") (pintype "output"))
    )
    (net (code "91") (name "Net-(Q13-D)") (class "Default")
      (node (ref "Q13") (pin "3") (pinfunction "D_3") (pintype "passive"))
      (node (ref "Q7") (pin "1") (pinfunction "G_1") (pintype "passive"))
      (node (ref "R21") (pin "1") (pinfunction "1_1") (pintype "passive"))
    )
    (net (code "92") (name "Net-(Q13-G)") (class "Default")
      (node (ref "Q13") (pin "1") (pinfunction "G_1") (pintype "passive"))
      (node (ref "U5") (pin "13") (pinfunction "PWM7_13") (pintype "output"))
    )
    (net (code "93") (name "Net-(Q14-D)") (class "Default")
      (node (ref "Q14") (pin "3") (pinfunction "D_3") (pintype "passive"))
      (node (ref "Q8") (pin "1") (pinfunction "G_1") (pintype "passive"))
      (node (ref "R22") (pin "1") (pinfunction "1_1") (pintype "passive"))
    )
    (net (code "94") (name "Net-(Q14-G)") (class "Default")
      (node (ref "Q14") (pin "1") (pinfunction "G_1") (pintype "passive"))
      (node (ref "U5") (pin "11") (pinfunction "PWM5_11") (pintype "output"))
    )
    (net (code "95") (name "Net-(Q15-D)") (class "Default")
      (node (ref "Q15") (pin "3") (pinfunction "D_3") (pintype "passive"))
      (node (ref "Q9") (pin "1") (pinfunction "G_1") (pintype "passive"))
      (node (ref "R23") (pin "1") (pinfunction "1_1") (pintype "passive"))
    )
    (net (code "96") (name "Net-(Q15-G)") (class "Default")
      (node (ref "Q15") (pin "1") (pinfunction "G_1") (pintype "passive"))
      (node (ref "U5") (pin "9") (pinfunction "PWM3_9") (pintype "output"))
    )
    (net (code "97") (name "Net-(Q16-G)") (class "Default")
      (node (ref "Q16") (pin "1") (pinfunction "G_1") (pintype "passive"))
      (node (ref "U5") (pin "7") (pinfunction "PWM1_7") (pintype "output"))
    )
    (net (code "98") (name "Net-(Q23-D)") (class "Default")
      (node (ref "D18") (pin "C") (pinfunction "C_C") (pintype "passive"))
      (node (ref "D20") (pin "A") (pinfunction "A_A") (pintype "passive"))
      (node (ref "D3") (pin "A") (pinfunction "A_A") (pintype "passive"))
      (node (ref "J1") (pin "3") (pinfunction "3_3") (pintype "passive"))
      (node (ref "Q23") (pin "3") (pinfunction "D_3") (pintype "passive"))
      (node (ref "Q3") (pin "3") (pinfunction "D_3") (pintype "passive"))
    )
    (net (code "99") (name "Net-(Q23-G)") (class "Default")
      (node (ref "Q23") (pin "1") (pinfunction "G_1") (pintype "passive"))
      (node (ref "Q3") (pin "1") (pinfunction "G_1") (pintype "passive"))
      (node (ref "Q34") (pin "3") (pinfunction "D_3") (pintype "passive"))
      (node (ref "R38") (pin "1") (pinfunction "1_1") (pintype "passive"))
    )
    (net (code "100") (name "Net-(Q24-D)") (class "Default")
      (node (ref "D4") (pin "A") (pinfunction "A_A") (pintype "passive"))
      (node (ref "J1") (pin "4") (pinfunction "4_4") (pintype "passive"))
      (node (ref "Q24") (pin "3") (pinfunction "D_3") (pintype "passive"))
      (node (ref "Q4") (pin "3") (pinfunction "D_3") (pintype "passive"))
      (node (ref "R18") (pin "2") (pinfunction "2_2") (pintype "passive"))
    )
    (net (code "101") (name "Net-(Q24-G)") (class "Default")
      (node (ref "Q24") (pin "1") (pinfunction "G_1") (pintype "passive"))
      (node (ref "Q31") (pin "3") (pinfunction "D_3") (pintype "passive"))
      (node (ref "Q4") (pin "1") (pinfunction "G_1") (pintype "passive"))
      (node (ref "R35") (pin "1") (pinfunction "1_1") (pintype "passive"))
    )
    (net (code "102") (name "Net-(Q25-D)") (class "Default")
      (node (ref "D6") (pin "A") (pinfunction "A_A") (pintype "passive"))
      (node (ref "J2") (pin "2") (pinfunction "2_2") (pintype "passive"))
      (node (ref "Q25") (pin "3") (pinfunction "D_3") (pintype "passive"))
    )
    (net (code "103") (name "Net-(Q25-G)") (class "Default")
      (node (ref "Q25") (pin "1") (pinfunction "G_1") (pintype "passive"))
      (node (ref "Q35") (pin "3") (pinfunction "D_3") (pintype "passive"))
      (node (ref "R46") (pin "1") (pinfunction "1_1") (pintype "passive"))
    )
    (net (code "104") (name "Net-(Q26-D)") (class "Default")
      (node (ref "D8") (pin "A") (pinfunction "A_A") (pintype "passive"))
      (node (ref "J2") (pin "4") (pinfunction "4_4") (pintype "passive"))
      (node (ref "Q26") (pin "3") (pinfunction "D_3") (pintype "passive"))
    )
    (net (code "105") (name "Net-(Q26-G)") (class "Default")
      (node (ref "Q26") (pin "1") (pinfunction "G_1") (pintype "passive"))
      (node (ref "Q36") (pin "3") (pinfunction "D_3") (pintype "passive"))
      (node (ref "R45") (pin "1") (pinfunction "1_1") (pintype "passive"))
    )
    (net (code "106") (name "Net-(Q27-D)") (class "Default")
      (node (ref "D10") (pin "A") (pinfunction "A_A") (pintype "passive"))
      (node (ref "J3") (pin "2") (pinfunction "2_2") (pintype "passive"))
      (node (ref "Q27") (pin "3") (pinfunction "D_3") (pintype "passive"))
    )
    (net (code "107") (name "Net-(Q27-G)") (class "Default")
      (node (ref "Q27") (pin "1") (pinfunction "G_1") (pintype "passive"))
      (node (ref "Q37") (pin "3") (pinfunction "D_3") (pintype "passive"))
      (node (ref "R47") (pin "1") (pinfunction "1_1") (pintype "passive"))
    )
    (net (code "108") (name "Net-(Q28-D)") (class "Default")
      (node (ref "D12") (pin "A") (pinfunction "A_A") (pintype "passive"))
      (node (ref "J3") (pin "4") (pinfunction "4_4") (pintype "passive"))
      (node (ref "Q28") (pin "3") (pinfunction "D_3") (pintype "passive"))
    )
    (net (code "109") (name "Net-(Q28-G)") (class "Default")
      (node (ref "Q28") (pin "1") (pinfunction "G_1") (pintype "passive"))
      (node (ref "Q38") (pin "3") (pinfunction "D_3") (pintype "passive"))
      (node (ref "R48") (pin "1") (pinfunction "1_1") (pintype "passive"))
    )
    (net (code "110") (name "Net-(Q29-D)") (class "Default")
      (node (ref "D14") (pin "A") (pinfunction "A_A") (pintype "passive"))
      (node (ref "J4") (pin "2") (pinfunction "2_2") (pintype "passive"))
      (node (ref "Q29") (pin "3") (pinfunction "D_3") (pintype "passive"))
    )
    (net (code "111") (name "Net-(Q29-G)") (class "Default")
      (node (ref "Q29") (pin "1") (pinfunction "G_1") (pintype "passive"))
      (node (ref "Q39") (pin "3") (pinfunction "D_3") (pintype "passive"))
      (node (ref "R49") (pin "1") (pinfunction "1_1") (pintype "passive"))
    )
    (net (code "112") (name "Net-(Q30-D)") (class "Default")
      (node (ref "D16") (pin "A") (pinfunction "A_A") (pintype "passive"))
      (node (ref "J4") (pin "4") (pinfunction "4_4") (pintype "passive"))
      (node (ref "Q30") (pin "3") (pinfunction "D_3") (pintype "passive"))
    )
    (net (code "113") (name "Net-(Q30-G)") (class "Default")
      (node (ref "Q30") (pin "1") (pinfunction "G_1") (pintype "passive"))
      (node (ref "Q40") (pin "3") (pinfunction "D_3") (pintype "passive"))
      (node (ref "R50") (pin "1") (pinfunction "1_1") (pintype "passive"))
    )
    (net (code "114") (name "Net-(Q31-G)") (class "Default")
      (node (ref "Q31") (pin "1") (pinfunction "G_1") (pintype "passive"))
      (node (ref "U5") (pin "19") (pinfunction "PWM12_19") (pintype "output"))
    )
    (net (code "115") (name "Net-(Q32-G)") (class "Default")
      (node (ref "Q32") (pin "1") (pinfunction "G_1") (pintype "passive"))
      (node (ref "U5") (pin "22") (pinfunction "PWM15_22") (pintype "output"))
    )
    (net (code "116") (name "Net-(Q33-G)") (class "Default")
      (node (ref "Q33") (pin "1") (pinfunction "G_1") (pintype "passive"))
      (node (ref "U5") (pin "21") (pinfunction "PWM14_21") (pintype "output"))
    )
    (net (code "117") (name "Net-(Q34-G)") (class "Default")
      (node (ref "Q34") (pin "1") (pinfunction "G_1") (pintype "passive"))
      (node (ref "U5") (pin "20") (pinfunction "PWM13_20") (pintype "output"))
    )
    (net (code "118") (name "Net-(Q35-G)") (class "Default")
      (node (ref "Q35") (pin "1") (pinfunction "G_1") (pintype "passive"))
      (node (ref "U5") (pin "17") (pinfunction "PWM10_17") (pintype "output"))
    )
    (net (code "119") (name "Net-(Q36-G)") (class "Default")
      (node (ref "Q36") (pin "1") (pinfunction "G_1") (pintype "passive"))
      (node (ref "U5") (pin "15") (pinfunction "PWM8_15") (pintype "output"))
    )
    (net (code "120") (name "Net-(Q37-G)") (class "Default")
      (node (ref "Q37") (pin "1") (pinfunction "G_1") (pintype "passive"))
      (node (ref "U5") (pin "12") (pinfunction "PWM6_12") (pintype "output"))
    )
    (net (code "121") (name "Net-(Q38-G)") (class "Default")
      (node (ref "Q38") (pin "1") (pinfunction "G_1") (pintype "passive"))
      (node (ref "U5") (pin "10") (pinfunction "PWM4_10") (pintype "output"))
    )
    (net (code "122") (name "Net-(Q39-G)") (class "Default")
      (node (ref "Q39") (pin "1") (pinfunction "G_1") (pintype "passive"))
      (node (ref "U5") (pin "8") (pinfunction "PWM2_8") (pintype "output"))
    )
    (net (code "123") (name "Net-(Q40-G)") (class "Default")
      (node (ref "Q40") (pin "1") (pinfunction "G_1") (pintype "passive"))
      (node (ref "U5") (pin "6") (pinfunction "PWM0_6") (pintype "output"))
    )
    (net (code "124") (name "Net-(Q41-D)") (class "Default")
      (node (ref "F1") (pin "2@1") (pinfunction "P$2_2@1") (pintype "bidirectional"))
      (node (ref "F1") (pin "2@2") (pinfunction "P$2_2@2") (pintype "bidirectional"))
      (node (ref "Q41") (pin "3") (pinfunction "D_3") (pintype "passive"))
    )
    (net (code "125") (name "Net-(Q41-G)") (class "Default")
      (node (ref "Q41") (pin "1") (pinfunction "G_1") (pintype "passive"))
      (node (ref "R43") (pin "1") (pinfunction "1_1") (pintype "passive"))
      (node (ref "U4") (pin "1") (pinfunction "A_1") (pintype "bidirectional"))
    )
    (net (code "126") (name "Net-(Q41-S)") (class "Default")
      (node (ref "Q41") (pin "2") (pinfunction "S_2") (pintype "passive"))
      (node (ref "R51") (pin "1") (pinfunction "1_1") (pintype "passive"))
      (node (ref "U4") (pin "2") (pinfunction "C2_2") (pintype "bidirectional"))
      (node (ref "U4") (pin "3") (pinfunction "C1_3") (pintype "bidirectional"))
      (node (ref "U7") (pin "8") (pinfunction "IN+_8") (pintype "bidirectional"))
    )
    (net (code "127") (name "Net-(Q42-D)") (class "Default")
      (node (ref "J17") (pin "2") (pinfunction "2_2") (pintype "passive"))
      (node (ref "Q42") (pin "3") (pinfunction "D_3") (pintype "passive"))
    )
    (net (code "128") (name "Net-(Q43-D)") (class "Default")
      (node (ref "J17") (pin "3") (pinfunction "3_3") (pintype "passive"))
      (node (ref "Q43") (pin "3") (pinfunction "D_3") (pintype "passive"))
    )
    (net (code "129") (name "Net-(Q44-D)") (class "Default")
      (node (ref "J17") (pin "4") (pinfunction "4_4") (pintype "passive"))
      (node (ref "Q44") (pin "3") (pinfunction "D_3") (pintype "passive"))
    )
    (net (code "130") (name "Net-(Q45-D)") (class "Default")
      (node (ref "J18") (pin "2") (pinfunction "2_2") (pintype "passive"))
      (node (ref "Q45") (pin "3") (pinfunction "D_3") (pintype "passive"))
    )
    (net (code "131") (name "Net-(Q46-D)") (class "Default")
      (node (ref "J18") (pin "3") (pinfunction "3_3") (pintype "passive"))
      (node (ref "Q46") (pin "3") (pinfunction "D_3") (pintype "passive"))
    )
    (net (code "132") (name "Net-(Q47-D)") (class "Default")
      (node (ref "J18") (pin "4") (pinfunction "4_4") (pintype "passive"))
      (node (ref "Q47") (pin "3") (pinfunction "D_3") (pintype "passive"))
    )
    (net (code "133") (name "Net-(R65-Pad1)") (class "Default")
      (node (ref "R65") (pin "1") (pinfunction "1_1") (pintype "passive"))
      (node (ref "U12") (pin "1") (pinfunction "1_1") (pintype "passive"))
    )
    (net (code "134") (name "Net-(R66-Pad1)") (class "Default")
      (node (ref "R66") (pin "1") (pinfunction "1_1") (pintype "passive"))
      (node (ref "U13") (pin "1") (pinfunction "1_1") (pintype "passive"))
    )
    (net (code "135") (name "Net-(R67-Pad1)") (class "Default")
      (node (ref "R67") (pin "1") (pinfunction "1_1") (pintype "passive"))
      (node (ref "U14") (pin "1") (pinfunction "1_1") (pintype "passive"))
    )
    (net (code "136") (name "Net-(R68-Pad1)") (class "Default")
      (node (ref "R68") (pin "1") (pinfunction "1_1") (pintype "passive"))
      (node (ref "U15") (pin "1") (pinfunction "1_1") (pintype "passive"))
    )
    (net (code "137") (name "Net-(U1--)") (class "Default")
      (node (ref "D25") (pin "A") (pinfunction "A_A") (pintype "passive"))
      (node (ref "U1") (pin "4") (pinfunction "-_4") (pintype "bidirectional"))
    )
    (net (code "138") (name "Net-(U1-T1)") (class "Default")
      (node (ref "J5") (pin "1") (pinfunction "1_1") (pintype "passive"))
      (node (ref "U1") (pin "1") (pinfunction "T1_1") (pintype "bidirectional"))
    )
    (net (code "139") (name "Net-(U1-T2)") (class "Default")
      (node (ref "J5") (pin "2") (pinfunction "2_2") (pintype "passive"))
      (node (ref "U1") (pin "2") (pinfunction "T2_2") (pintype "bidirectional"))
    )
    (net (code "140") (name "Net-(U2--)") (class "Default")
      (node (ref "D26") (pin "A") (pinfunction "A_A") (pintype "passive"))
      (node (ref "U2") (pin "4") (pinfunction "-_4") (pintype "bidirectional"))
    )
    (net (code "141") (name "Net-(U2-T1)") (class "Default")
      (node (ref "J6") (pin "1") (pinfunction "1_1") (pintype "passive"))
      (node (ref "U2") (pin "1") (pinfunction "T1_1") (pintype "bidirectional"))
    )
    (net (code "142") (name "Net-(U2-T2)") (class "Default")
      (node (ref "J6") (pin "2") (pinfunction "2_2") (pintype "passive"))
      (node (ref "U2") (pin "2") (pinfunction "T2_2") (pintype "bidirectional"))
    )
    (net (code "143") (name "Net-(U3-A)") (class "Default")
      (node (ref "J13") (pin "2") (pinfunction "2_2") (pintype "passive"))
      (node (ref "R52") (pin "2") (pinfunction "2_2") (pintype "passive"))
      (node (ref "U3") (pin "12") (pinfunction "A_12") (pintype "bidirectional"))
    )
    (net (code "144") (name "Net-(U3-B)") (class "Default")
      (node (ref "J13") (pin "3") (pinfunction "3_3") (pintype "passive"))
      (node (ref "R52") (pin "1") (pinfunction "1_1") (pintype "passive"))
      (node (ref "U3") (pin "11") (pinfunction "B_11") (pintype "bidirectional"))
    )
    (net (code "145") (name "Net-(U3-Y)") (class "Default")
      (node (ref "J13") (pin "4") (pinfunction "4_4") (pintype "passive"))
      (node (ref "U3") (pin "9") (pinfunction "Y_9") (pintype "bidirectional"))
    )
    (net (code "146") (name "Net-(U3-Z)") (class "Default")
      (node (ref "J13") (pin "5") (pinfunction "5_5") (pintype "passive"))
      (node (ref "U3") (pin "10") (pinfunction "Z_10") (pintype "bidirectional"))
    )
    (net (code "147") (name "Net-(U6A-+IN)") (class "Default")
      (node (ref "C4") (pin "1") (pinfunction "1_1") (pintype "passive"))
      (node (ref "R44") (pin "2") (pinfunction "2_2") (pintype "passive"))
      (node (ref "U6") (pin "3") (pinfunction "+IN_3") (pintype "input"))
    )
    (net (code "148") (name "Net-(U6A--IN)") (class "Default")
      (node (ref "R53") (pin "1") (pinfunction "1_1") (pintype "passive"))
      (node (ref "R56") (pin "2") (pinfunction "2_2") (pintype "passive"))
      (node (ref "U6") (pin "2") (pinfunction "-IN_2") (pintype "input"))
    )
    (net (code "149") (name "Net-(U6B-+IN)") (class "Default")
      (node (ref "C9") (pin "1") (pinfunction "1_1") (pintype "passive"))
      (node (ref "R57") (pin "2") (pinfunction "2_2") (pintype "passive"))
      (node (ref "U6") (pin "5") (pinfunction "+IN_5") (pintype "input"))
    )
    (net (code "150") (name "Net-(U6B--IN)") (class "Default")
      (node (ref "R54") (pin "1") (pinfunction "1_1") (pintype "passive"))
      (node (ref "R55") (pin "2") (pinfunction "2_2") (pintype "passive"))
      (node (ref "U6") (pin "6") (pinfunction "-IN_6") (pintype "input"))
    )
    (net (code "151") (name "Net-(U10-AIN0)") (class "Default")
      (node (ref "R58") (pin "1") (pinfunction "1_1") (pintype "passive"))
      (node (ref "R59") (pin "2") (pinfunction "2_2") (pintype "passive"))
      (node (ref "U10") (pin "4") (pinfunction "AIN0_4") (pintype "input"))
    )
    (net (code "152") (name "Net-(U11A-+IN)") (class "Default")
      (node (ref "C12") (pin "1") (pinfunction "1_1") (pintype "passive"))
      (node (ref "R72") (pin "2") (pinfunction "2_2") (pintype "passive"))
      (node (ref "U11") (pin "3") (pinfunction "+IN_3") (pintype "input"))
    )
    (net (code "153") (name "Net-(U11A--IN)") (class "Default")
      (node (ref "R63") (pin "1") (pinfunction "1_1") (pintype "passive"))
      (node (ref "R70") (pin "2") (pinfunction "2_2") (pintype "passive"))
      (node (ref "U11") (pin "2") (pinfunction "-IN_2") (pintype "input"))
    )
    (net (code "154") (name "Net-(U11A-OUT)") (class "Default")
      (node (ref "R58") (pin "2") (pinfunction "2_2") (pintype "passive"))
      (node (ref "R63") (pin "2") (pinfunction "2_2") (pintype "passive"))
      (node (ref "U11") (pin "1") (pinfunction "OUT_1") (pintype "output"))
    )
    (net (code "155") (name "Net-(U11B-+IN)") (class "Default")
      (node (ref "C11") (pin "1") (pinfunction "1_1") (pintype "passive"))
      (node (ref "R75") (pin "2") (pinfunction "2_2") (pintype "passive"))
      (node (ref "R76") (pin "1") (pinfunction "1_1") (pintype "passive"))
      (node (ref "U11") (pin "5") (pinfunction "+IN_5") (pintype "input"))
    )
    (net (code "156") (name "Net-(U11B--IN)") (class "Default")
      (node (ref "R69") (pin "1") (pinfunction "1_1") (pintype "passive"))
      (node (ref "R71") (pin "2") (pinfunction "2_2") (pintype "passive"))
      (node (ref "U11") (pin "6") (pinfunction "-IN_6") (pintype "input"))
    )
    (net (code "157") (name "Net-(U11B-OUT)") (class "Default")
      (node (ref "R69") (pin "2") (pinfunction "2_2") (pintype "passive"))
      (node (ref "U11") (pin "7") (pinfunction "OUT_7") (pintype "output"))
      (node (ref "U18") (pin "12") (pinfunction "Y3_12") (pintype "bidirectional"))
    )
    (net (code "158") (name "Net-(U16-GPA6)") (class "Default")
      (node (ref "J30") (pin "2") (pinfunction "2_2") (pintype "passive"))
      (node (ref "U16") (pin "27") (pinfunction "GPA6_27") (pintype "bidirectional"))
    )
    (net (code "159") (name "Net-(U16-GPA7)") (class "Default")
      (node (ref "J30") (pin "3") (pinfunction "3_3") (pintype "passive"))
      (node (ref "U16") (pin "28") (pinfunction "GPA7_28") (pintype "bidirectional"))
    )
    (net (code "160") (name "Net-(U16-GPB0)") (class "Default")
      (node (ref "J30") (pin "4") (pinfunction "4_4") (pintype "passive"))
      (node (ref "U16") (pin "1") (pinfunction "GPB0_1") (pintype "bidirectional"))
    )
    (net (code "161") (name "Net-(U16-GPB1)") (class "Default")
      (node (ref "J30") (pin "5") (pinfunction "5_5") (pintype "passive"))
      (node (ref "U16") (pin "2") (pinfunction "GPB1_2") (pintype "bidirectional"))
    )
    (net (code "162") (name "Net-(U16-GPB2)") (class "Default")
      (node (ref "C29") (pin "1") (pinfunction "1_1") (pintype "passive"))
      (node (ref "J29") (pin "1") (pinfunction "1_1") (pintype "passive"))
      (node (ref "U16") (pin "3") (pinfunction "GPB2_3") (pintype "bidirectional"))
    )
    (net (code "163") (name "Net-(U16-GPB3)") (class "Default")
      (node (ref "C28") (pin "1") (pinfunction "1_1") (pintype "passive"))
      (node (ref "J29") (pin "2") (pinfunction "2_2") (pintype "passive"))
      (node (ref "U16") (pin "4") (pinfunction "GPB3_4") (pintype "bidirectional"))
    )
    (net (code "164") (name "Net-(U16-GPB4)") (class "Default")
      (node (ref "C27") (pin "1") (pinfunction "1_1") (pintype "passive"))
      (node (ref "J29") (pin "3") (pinfunction "3_3") (pintype "passive"))
      (node (ref "U16") (pin "5") (pinfunction "GPB4_5") (pintype "bidirectional"))
    )
    (net (code "165") (name "Net-(U16-GPB5)") (class "Default")
      (node (ref "C26") (pin "1") (pinfunction "1_1") (pintype "passive"))
      (node (ref "J29") (pin "4") (pinfunction "4_4") (pintype "passive"))
      (node (ref "U16") (pin "6") (pinfunction "GPB5_6") (pintype "bidirectional"))
    )
    (net (code "166") (name "Net-(U16-GPB6)") (class "Default")
      (node (ref "C25") (pin "1") (pinfunction "1_1") (pintype "passive"))
      (node (ref "J29") (pin "5") (pinfunction "5_5") (pintype "passive"))
      (node (ref "U16") (pin "7") (pinfunction "GPB6_7") (pintype "bidirectional"))
    )
    (net (code "167") (name "Net-(U16-GPB7)") (class "Default")
      (node (ref "C24") (pin "1") (pinfunction "1_1") (pintype "passive"))
      (node (ref "J29") (pin "6") (pinfunction "6_6") (pintype "passive"))
      (node (ref "U16") (pin "8") (pinfunction "GPB7_8") (pintype "bidirectional"))
    )
    (net (code "168") (name "Net-(U17-WP)") (class "Default")
      (node (ref "JP2") (pin "2") (pinfunction "2_2") (pintype "passive"))
      (node (ref "R77") (pin "1") (pinfunction "1_1") (pintype "passive"))
      (node (ref "U17") (pin "7") (pinfunction "WP_7") (pintype "bidirectional"))
    )
    (net (code "169") (name "Net-(U18-Y0)") (class "Default")
      (node (ref "C19") (pin "1") (pinfunction "1_1") (pintype "passive"))
      (node (ref "J28") (pin "2") (pinfunction "2_2") (pintype "passive"))
      (node (ref "R90") (pin "1") (pinfunction "1_1") (pintype "passive"))
      (node (ref "U18") (pin "13") (pinfunction "Y0_13") (pintype "bidirectional"))
    )
    (net (code "170") (name "Net-(U18-Y1)") (class "Default")
      (node (ref "C18") (pin "1") (pinfunction "1_1") (pintype "passive"))
      (node (ref "R88") (pin "1") (pinfunction "1_1") (pintype "passive"))
      (node (ref "R89") (pin "2") (pinfunction "2_2") (pintype "passive"))
      (node (ref "U18") (pin "14") (pinfunction "Y1_14") (pintype "bidirectional"))
    )
    (net (code "171") (name "Net-(U18-Y2)") (class "Default")
      (node (ref "C17") (pin "1") (pinfunction "1_1") (pintype "passive"))
      (node (ref "R86") (pin "1") (pinfunction "1_1") (pintype "passive"))
      (node (ref "R87") (pin "2") (pinfunction "2_2") (pintype "passive"))
      (node (ref "U18") (pin "15") (pinfunction "Y2_15") (pintype "bidirectional"))
    )
    (net (code "172") (name "Net-(U18-Y4)") (class "Default")
      (node (ref "C23") (pin "1") (pinfunction "1_1") (pintype "passive"))
      (node (ref "J24") (pin "2") (pinfunction "2_2") (pintype "passive"))
      (node (ref "R94") (pin "1") (pinfunction "1_1") (pintype "passive"))
      (node (ref "U18") (pin "1") (pinfunction "Y4_1") (pintype "bidirectional"))
    )
    (net (code "173") (name "Net-(U18-Y5)") (class "Default")
      (node (ref "C22") (pin "1") (pinfunction "1_1") (pintype "passive"))
      (node (ref "J23") (pin "2") (pinfunction "2_2") (pintype "passive"))
      (node (ref "R93") (pin "1") (pinfunction "1_1") (pintype "passive"))
      (node (ref "U18") (pin "5") (pinfunction "Y5_5") (pintype "bidirectional"))
    )
    (net (code "174") (name "Net-(U18-Y6)") (class "Default")
      (node (ref "C21") (pin "1") (pinfunction "1_1") (pintype "passive"))
      (node (ref "J22") (pin "2") (pinfunction "2_2") (pintype "passive"))
      (node (ref "R92") (pin "1") (pinfunction "1_1") (pintype "passive"))
      (node (ref "U18") (pin "2") (pinfunction "Y6_2") (pintype "bidirectional"))
    )
    (net (code "175") (name "Net-(U18-Y7)") (class "Default")
      (node (ref "C20") (pin "1") (pinfunction "1_1") (pintype "passive"))
      (node (ref "J21") (pin "2") (pinfunction "2_2") (pintype "passive"))
      (node (ref "R91") (pin "1") (pinfunction "1_1") (pintype "passive"))
      (node (ref "U18") (pin "4") (pinfunction "Y7_4") (pintype "bidirectional"))
    )
    (net (code "176") (name "Net-(U18-Z)") (class "Default")
      (node (ref "R72") (pin "1") (pinfunction "1_1") (pintype "passive"))
      (node (ref "U18") (pin "3") (pinfunction "Z_3") (pintype "bidirectional"))
    )
    (net (code "177") (name "Net-(U19-MFP)") (class "Default")
      (node (ref "R79") (pin "1") (pinfunction "1_1") (pintype "passive"))
      (node (ref "U19") (pin "7") (pinfunction "MFP_7") (pintype "bidirectional"))
    )
    (net (code "178") (name "Net-(U19-VBAT)") (class "Default")
      (node (ref "B1") (pin "+1") (pinfunction "+1_+1") (pintype "bidirectional"))
      (node (ref "U19") (pin "3") (pinfunction "VBAT_3") (pintype "bidirectional"))
    )
    (net (code "179") (name "Net-(U19-X1)") (class "Default")
      (node (ref "C13") (pin "1") (pinfunction "1_1") (pintype "passive"))
      (node (ref "U19") (pin "1") (pinfunction "X1_1") (pintype "bidirectional"))
      (node (ref "Y1") (pin "1") (pinfunction "1_1") (pintype "passive"))
    )
    (net (code "180") (name "Net-(U19-X2)") (class "Default")
      (node (ref "C14") (pin "1") (pinfunction "1_1") (pintype "passive"))
      (node (ref "U19") (pin "2") (pinfunction "X2_2") (pintype "bidirectional"))
      (node (ref "Y1") (pin "4") (pinfunction "2_4") (pintype "passive"))
    )
    (net (code "181") (name "RELAY0EN") (class "Default")
      (node (ref "Q20") (pin "1") (pinfunction "G_1") (pintype "passive"))
      (node (ref "U16") (pin "21") (pinfunction "GPA0_21") (pintype "bidirectional"))
    )
    (net (code "182") (name "RELAY1EN") (class "Default")
      (node (ref "Q17") (pin "1") (pinfunction "G_1") (pintype "passive"))
      (node (ref "U16") (pin "22") (pinfunction "GPA1_22") (pintype "bidirectional"))
    )
    (net (code "183") (name "RELAY2EN") (class "Default")
      (node (ref "Q19") (pin "1") (pinfunction "G_1") (pintype "passive"))
      (node (ref "U16") (pin "23") (pinfunction "GPA2_23") (pintype "bidirectional"))
    )
    (net (code "184") (name "RELAY3EN") (class "Default")
      (node (ref "Q18") (pin "1") (pinfunction "G_1") (pintype "passive"))
      (node (ref "U16") (pin "24") (pinfunction "GPA3_24") (pintype "bidirectional"))
    )
    (net (code "185") (name "RELAY4EN") (class "Default")
      (node (ref "R26") (pin "1") (pinfunction "1_1") (pintype "passive"))
      (node (ref "U16") (pin "25") (pinfunction "GPA4_25") (pintype "bidirectional"))
    )
    (net (code "186") (name "RELAY5EN") (class "Default")
      (node (ref "R25") (pin "1") (pinfunction "1_1") (pintype "passive"))
      (node (ref "U16") (pin "26") (pinfunction "GPA5_26") (pintype "bidirectional"))
    )
    (net (code "187") (name "RXEN") (class "Default")
      (node (ref "PCB1") (pin "P$12") (pinfunction "GPIO18_P$12") (pintype "bidirectional"))
      (node (ref "U3") (pin "4") (pinfunction "~{RE}_4") (pintype "bidirectional"))
    )
    (net (code "188") (name "S0") (class "Default")
      (node (ref "PCB1") (pin "P$15") (pinfunction "GPIO22_P$15") (pintype "bidirectional"))
      (node (ref "R41") (pin "1") (pinfunction "1_1") (pintype "passive"))
      (node (ref "S1") (pin "P$2") (pinfunction "2_P$2") (pintype "passive"))
    )
    (net (code "189") (name "S1") (class "Default")
      (node (ref "PCB1") (pin "P$19") (pinfunction "GPIO10_P$19") (pintype "bidirectional"))
      (node (ref "R42") (pin "1") (pinfunction "1_1") (pintype "passive"))
      (node (ref "S2") (pin "P$2") (pinfunction "2_P$2") (pintype "passive"))
    )
    (net (code "190") (name "SCL") (class "Default")
      (node (ref "J11") (pin "3") (pinfunction "3_3") (pintype "passive"))
      (node (ref "PCB1") (pin "P$5") (pinfunction "GPIO3_P$5") (pintype "bidirectional"))
      (node (ref "R40") (pin "1") (pinfunction "1_1") (pintype "passive"))
      (node (ref "U10") (pin "10") (pinfunction "SCL_10") (pintype "bidirectional"))
      (node (ref "U16") (pin "12") (pinfunction "SCL_12") (pintype "input"))
      (node (ref "U19") (pin "6") (pinfunction "SCL_6") (pintype "bidirectional"))
      (node (ref "U20") (pin "SCL") (pinfunction "SCL_SCL") (pintype "passive"))
      (node (ref "U5") (pin "26") (pinfunction "SCL_26") (pintype "bidirectional"))
      (node (ref "U7") (pin "4") (pinfunction "SCL_4") (pintype "bidirectional"))
      (node (ref "U8") (pin "2") (pinfunction "SCL_2") (pintype "input"))
    )
    (net (code "191") (name "SDA") (class "Default")
      (node (ref "J11") (pin "4") (pinfunction "4_4") (pintype "passive"))
      (node (ref "PCB1") (pin "P$3") (pinfunction "GPIO2_P$3") (pintype "bidirectional"))
      (node (ref "R39") (pin "1") (pinfunction "1_1") (pintype "passive"))
      (node (ref "U10") (pin "9") (pinfunction "SDA_9") (pintype "bidirectional"))
      (node (ref "U16") (pin "13") (pinfunction "SDA_13") (pintype "bidirectional"))
      (node (ref "U19") (pin "5") (pinfunction "SDA_5") (pintype "bidirectional"))
      (node (ref "U20") (pin "SDA") (pinfunction "SDA_SDA") (pintype "passive"))
      (node (ref "U5") (pin "27") (pinfunction "SDA_27") (pintype "bidirectional"))
      (node (ref "U7") (pin "3") (pinfunction "SDA_3") (pintype "bidirectional"))
      (node (ref "U8") (pin "1") (pinfunction "SDA_1") (pintype "bidirectional"))
    )
    (net (code "192") (name "SENSORS0") (class "Default")
      (node (ref "PCB1") (pin "P$40") (pinfunction "GPIO21_P$40") (pintype "bidirectional"))
      (node (ref "U18") (pin "11") (pinfunction "S0_11") (pintype "input"))
    )
    (net (code "193") (name "SENSORS1") (class "Default")
      (node (ref "PCB1") (pin "P$37") (pinfunction "GPIO26_P$37") (pintype "bidirectional"))
      (node (ref "U18") (pin "10") (pinfunction "S1_10") (pintype "input"))
    )
    (net (code "194") (name "SENSORS2") (class "Default")
      (node (ref "PCB1") (pin "P$38") (pinfunction "GPIO20_P$38") (pintype "bidirectional"))
      (node (ref "U18") (pin "9") (pinfunction "S2_9") (pintype "input"))
    )
    (net (code "195") (name "STEPPERADIR") (class "Default")
      (node (ref "PCB1") (pin "P$32") (pinfunction "GPIO12_P$32") (pintype "bidirectional"))
      (node (ref "Q46") (pin "1") (pinfunction "G_1") (pintype "passive"))
      (node (ref "R84") (pin "2") (pinfunction "2_2") (pintype "passive"))
    )
    (net (code "196") (name "STEPPERAEN") (class "Default")
      (node (ref "PCB1") (pin "P$29") (pinfunction "GPIO5_P$29") (pintype "bidirectional"))
      (node (ref "Q47") (pin "1") (pinfunction "G_1") (pintype "passive"))
      (node (ref "R85") (pin "2") (pinfunction "2_2") (pintype "passive"))
    )
    (net (code "197") (name "STEPPERASTEP") (class "Default")
      (node (ref "PCB1") (pin "P$31") (pinfunction "GPIO6_P$31") (pintype "bidirectional"))
      (node (ref "Q45") (pin "1") (pinfunction "G_1") (pintype "passive"))
      (node (ref "R83") (pin "2") (pinfunction "2_2") (pintype "passive"))
    )
    (net (code "198") (name "STEPPERBDIR") (class "Default")
      (node (ref "PCB1") (pin "P$36") (pinfunction "GPIO16_P$36") (pintype "bidirectional"))
      (node (ref "Q43") (pin "1") (pinfunction "G_1") (pintype "passive"))
      (node (ref "R81") (pin "2") (pinfunction "2_2") (pintype "passive"))
    )
    (net (code "199") (name "STEPPERBEN") (class "Default")
      (node (ref "PCB1") (pin "P$33") (pinfunction "GPIO13_P$33") (pintype "bidirectional"))
      (node (ref "Q44") (pin "1") (pinfunction "G_1") (pintype "passive"))
      (node (ref "R82") (pin "2") (pinfunction "2_2") (pintype "passive"))
    )
    (net (code "200") (name "STEPPERBSTEP") (class "Default")
      (node (ref "PCB1") (pin "P$35") (pinfunction "GPIO19_P$35") (pintype "bidirectional"))
      (node (ref "Q42") (pin "1") (pinfunction "G_1") (pintype "passive"))
      (node (ref "R80") (pin "2") (pinfunction "2_2") (pintype "passive"))
    )
    (net (code "201") (name "TXEN") (class "Default")
      (node (ref "PCB1") (pin "P$7") (pinfunction "GPIO4_P$7") (pintype "bidirectional"))
      (node (ref "U3") (pin "3") (pinfunction "DE_3") (pintype "bidirectional"))
    )
    (net (code "202") (name "UART0_RX") (class "Default")
      (node (ref "PCB1") (pin "P$10") (pinfunction "GPIO15_P$10") (pintype "bidirectional"))
      (node (ref "U3") (pin "2") (pinfunction "RO_2") (pintype "bidirectional"))
    )
    (net (code "203") (name "UART0_TX") (class "Default")
      (node (ref "PCB1") (pin "P$8") (pinfunction "GPIO14_P$8") (pintype "bidirectional"))
      (node (ref "U3") (pin "5") (pinfunction "DI_5") (pintype "bidirectional"))
    )
    (net (code "204") (name "VBATT") (class "Default")
      (node (ref "D31") (pin "C") (pinfunction "C_C") (pintype "bidirectional"))
      (node (ref "J14") (pin "1") (pinfunction "1_1") (pintype "passive"))
      (node (ref "J15") (pin "1") (pinfunction "1_1") (pintype "passive"))
      (node (ref "J16") (pin "1") (pinfunction "1_1") (pintype "passive"))
      (node (ref "J16") (pin "2") (pinfunction "2_2") (pintype "passive"))
      (node (ref "J16") (pin "3") (pinfunction "3_3") (pintype "passive"))
      (node (ref "Q10") (pin "2") (pinfunction "S_2") (pintype "passive"))
      (node (ref "Q21") (pin "2") (pinfunction "S_2") (pintype "passive"))
      (node (ref "Q22") (pin "2") (pinfunction "S_2") (pintype "passive"))
      (node (ref "Q23") (pin "2") (pinfunction "S_2") (pintype "passive"))
      (node (ref "Q24") (pin "2") (pinfunction "S_2") (pintype "passive"))
      (node (ref "Q25") (pin "2") (pinfunction "S_2") (pintype "passive"))
      (node (ref "Q26") (pin "2") (pinfunction "S_2") (pintype "passive"))
      (node (ref "Q27") (pin "2") (pinfunction "S_2") (pintype "passive"))
      (node (ref "Q28") (pin "2") (pinfunction "S_2") (pintype "passive"))
      (node (ref "Q29") (pin "2") (pinfunction "S_2") (pintype "passive"))
      (node (ref "Q30") (pin "2") (pinfunction "S_2") (pintype "passive"))
      (node (ref "Q5") (pin "2") (pinfunction "S_2") (pintype "passive"))
      (node (ref "Q6") (pin "2") (pinfunction "S_2") (pintype "passive"))
      (node (ref "Q7") (pin "2") (pinfunction "S_2") (pintype "passive"))
      (node (ref "Q8") (pin "2") (pinfunction "S_2") (pintype "passive"))
      (node (ref "Q9") (pin "2") (pinfunction "S_2") (pintype "passive"))
      (node (ref "R19") (pin "2") (pinfunction "2_2") (pintype "passive"))
      (node (ref "R20") (pin "2") (pinfunction "2_2") (pintype "passive"))
      (node (ref "R21") (pin "2") (pinfunction "2_2") (pintype "passive"))
      (node (ref "R22") (pin "2") (pinfunction "2_2") (pintype "passive"))
      (node (ref "R23") (pin "2") (pinfunction "2_2") (pintype "passive"))
      (node (ref "R24") (pin "2") (pinfunction "2_2") (pintype "passive"))
      (node (ref "R27") (pin "2") (pinfunction "2_2") (pintype "passive"))
      (node (ref "R35") (pin "2") (pinfunction "2_2") (pintype "passive"))
      (node (ref "R36") (pin "2") (pinfunction "2_2") (pintype "passive"))
      (node (ref "R37") (pin "2") (pinfunction "2_2") (pintype "passive"))
      (node (ref "R38") (pin "2") (pinfunction "2_2") (pintype "passive"))
      (node (ref "R45") (pin "2") (pinfunction "2_2") (pintype "passive"))
      (node (ref "R46") (pin "2") (pinfunction "2_2") (pintype "passive"))
      (node (ref "R47") (pin "2") (pinfunction "2_2") (pintype "passive"))
      (node (ref "R48") (pin "2") (pinfunction "2_2") (pintype "passive"))
      (node (ref "R49") (pin "2") (pinfunction "2_2") (pintype "passive"))
      (node (ref "R50") (pin "2") (pinfunction "2_2") (pintype "passive"))
      (node (ref "R51") (pin "2") (pinfunction "2_2") (pintype "passive"))
      (node (ref "U7") (pin "7") (pinfunction "IN-_7") (pintype "bidirectional"))
      (node (ref "U9") (pin "IN+") (pinfunction "VIN+_IN+") (pintype "bidirectional"))
    )
    (net (code "205") (name "unconnected-(PCB1-RUN_1-PadP$41)") (class "Default")
      (node (ref "PCB1") (pin "P$41") (pinfunction "RUN_1_P$41") (pintype "bidirectional"))
    )
    (net (code "206") (name "unconnected-(PCB1-RUN_2-PadP$42)") (class "Default")
      (node (ref "PCB1") (pin "P$42") (pinfunction "RUN_2_P$42") (pintype "bidirectional"))
    )
    (net (code "207") (name "unconnected-(U8-OS-Pad3)") (class "Default")
      (node (ref "U8") (pin "3") (pinfunction "OS_3") (pintype "output"))
    )
    (net (code "208") (name "unconnected-(U16-INTA-Pad20)") (class "Default")
      (node (ref "U16") (pin "20") (pinfunction "INTA_20") (pintype "output"))
    )
    (net (code "209") (name "unconnected-(U22B-+IN-Pad5)") (class "Default")
      (node (ref "U22") (pin "5") (pinfunction "+IN_5") (pintype "input"))
    )
    (net (code "210") (name "unconnected-(U22B--IN-Pad6)") (class "Default")
      (node (ref "U22") (pin "6") (pinfunction "-IN_6") (pintype "input"))
    )
    (net (code "211") (name "unconnected-(U22B-OUT-Pad7)") (class "Default")
      (node (ref "U22") (pin "7") (pinfunction "OUT_7") (pintype "output"))
    )
  )
)
